# dt-rev-b.net
KiCad netlist of a schematic drawn in EAGLE
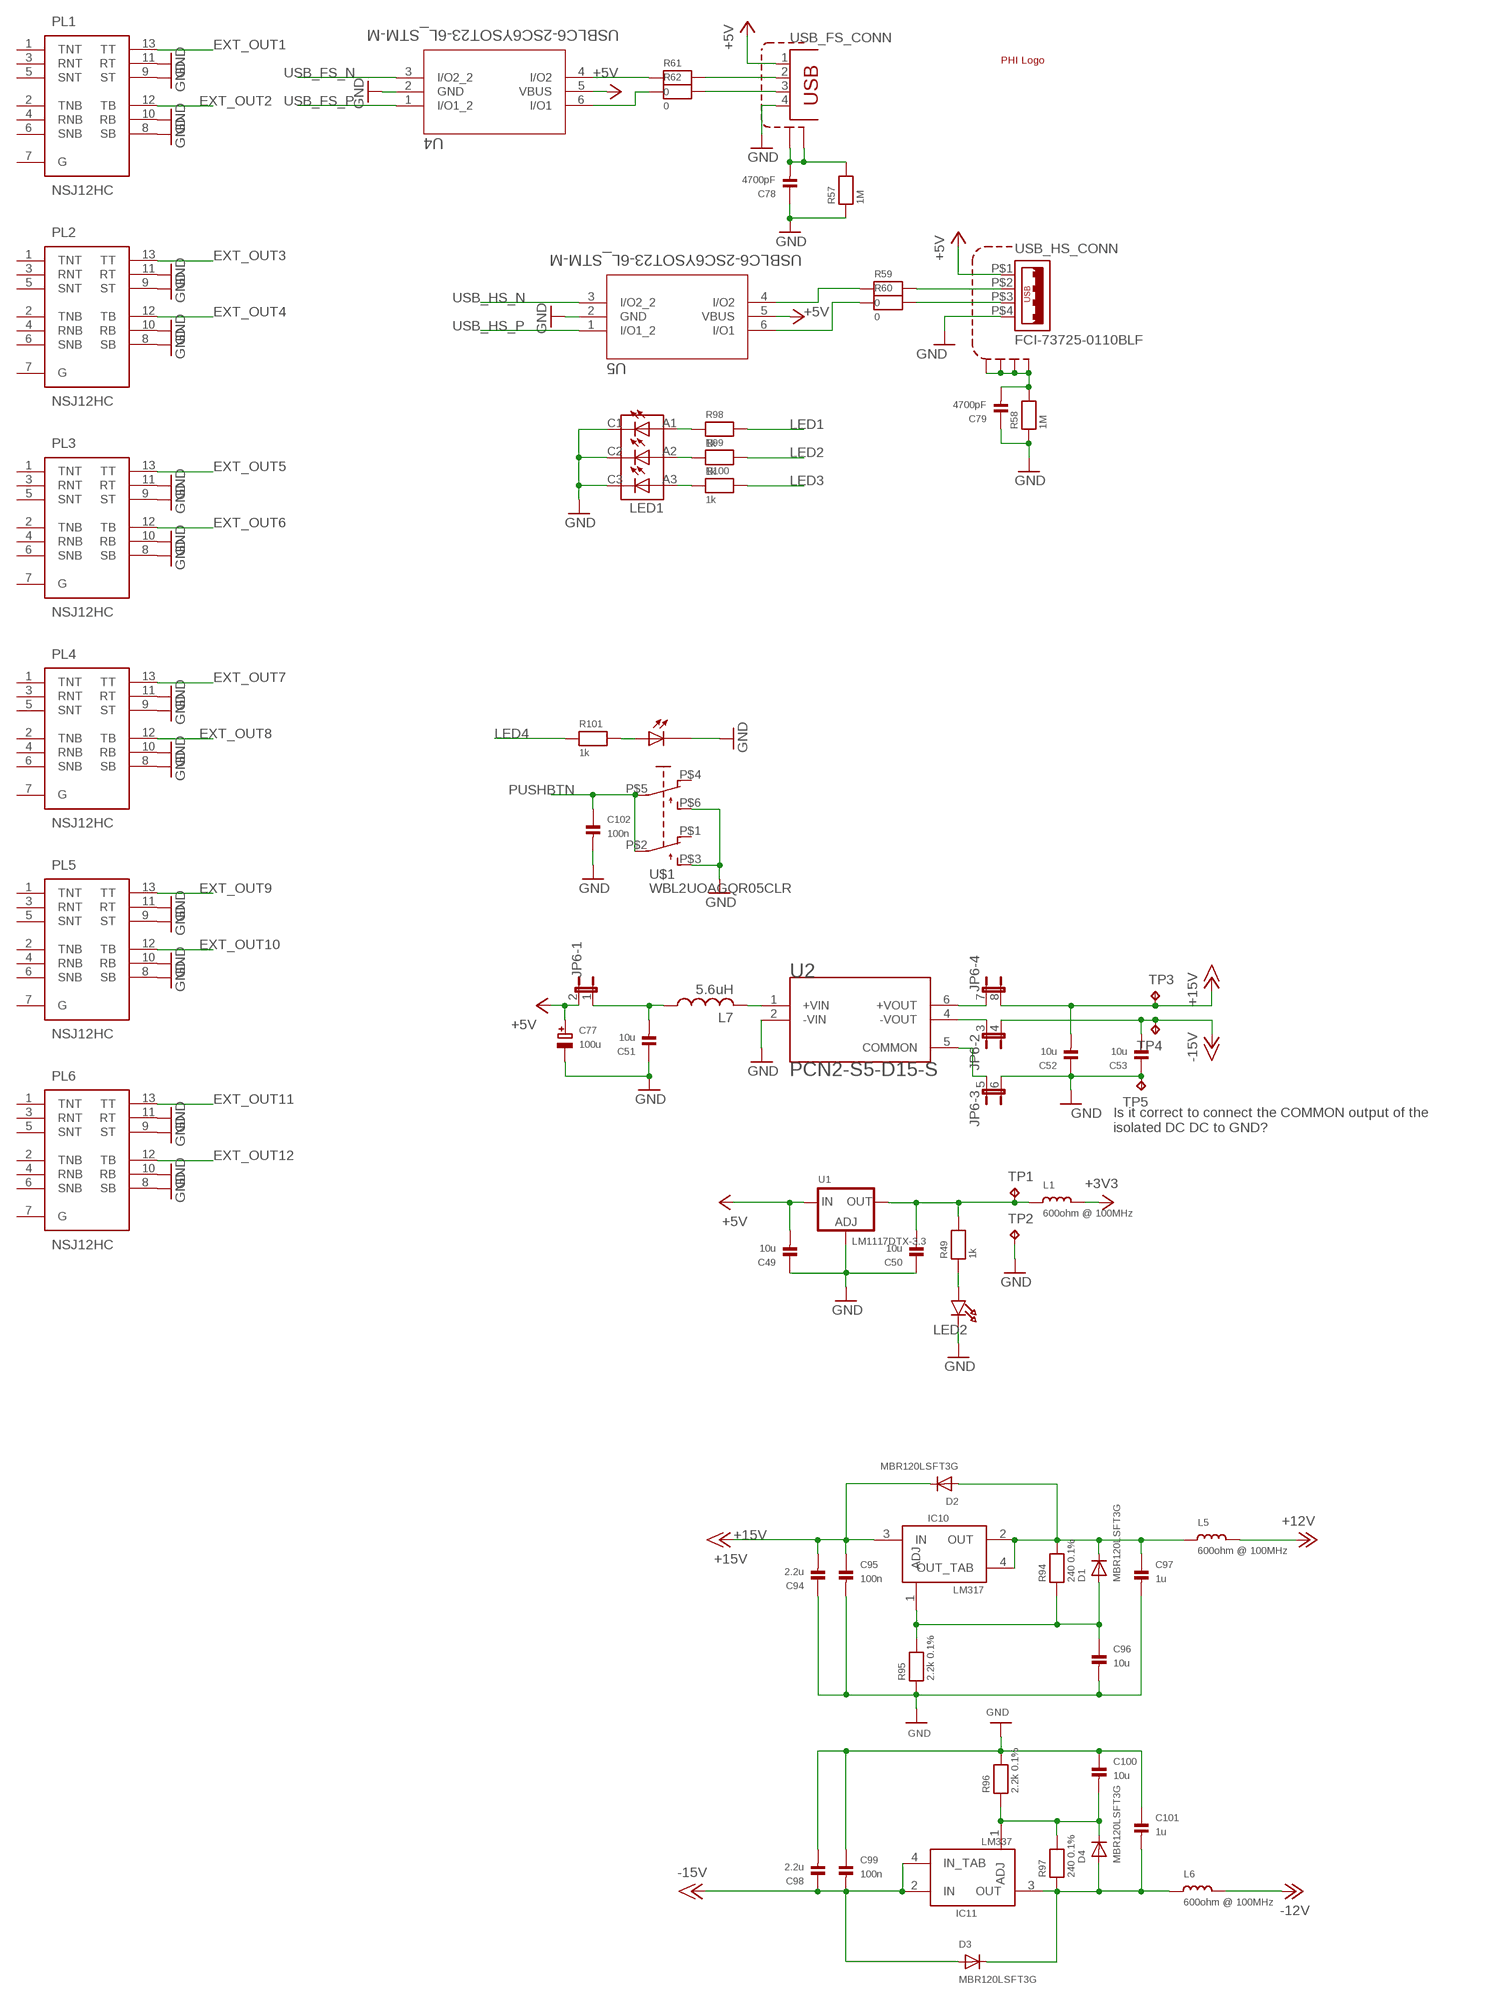
[diagram p0: schematic, sheet 1]
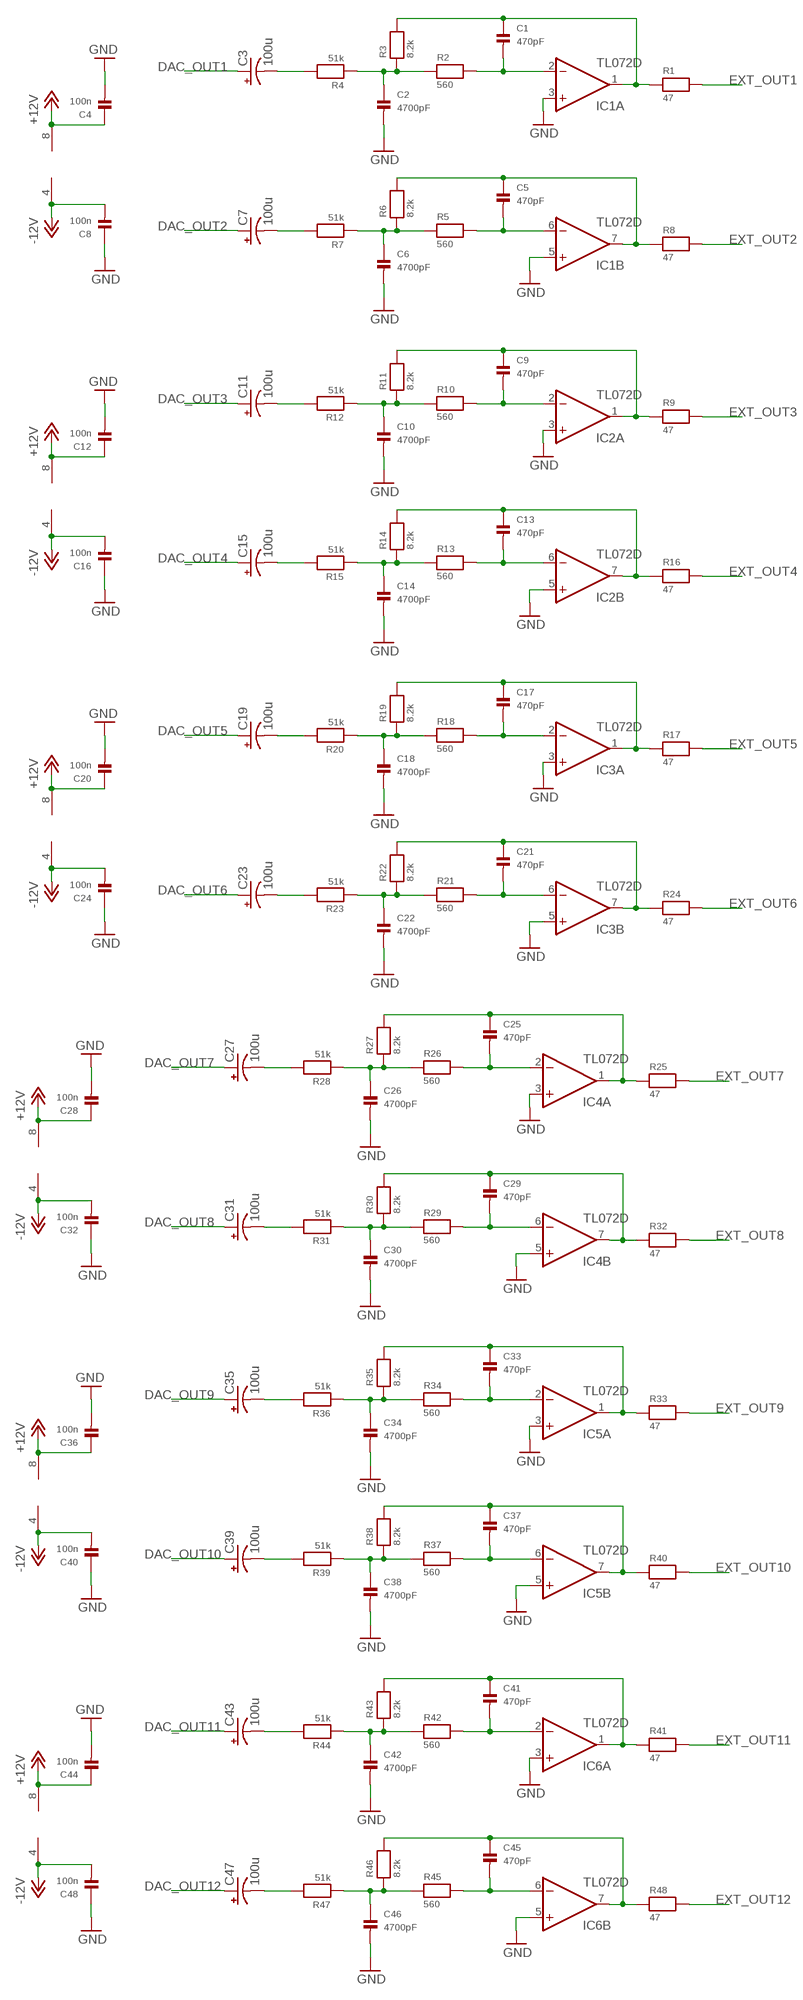
[diagram p1: schematic, sheet 2]
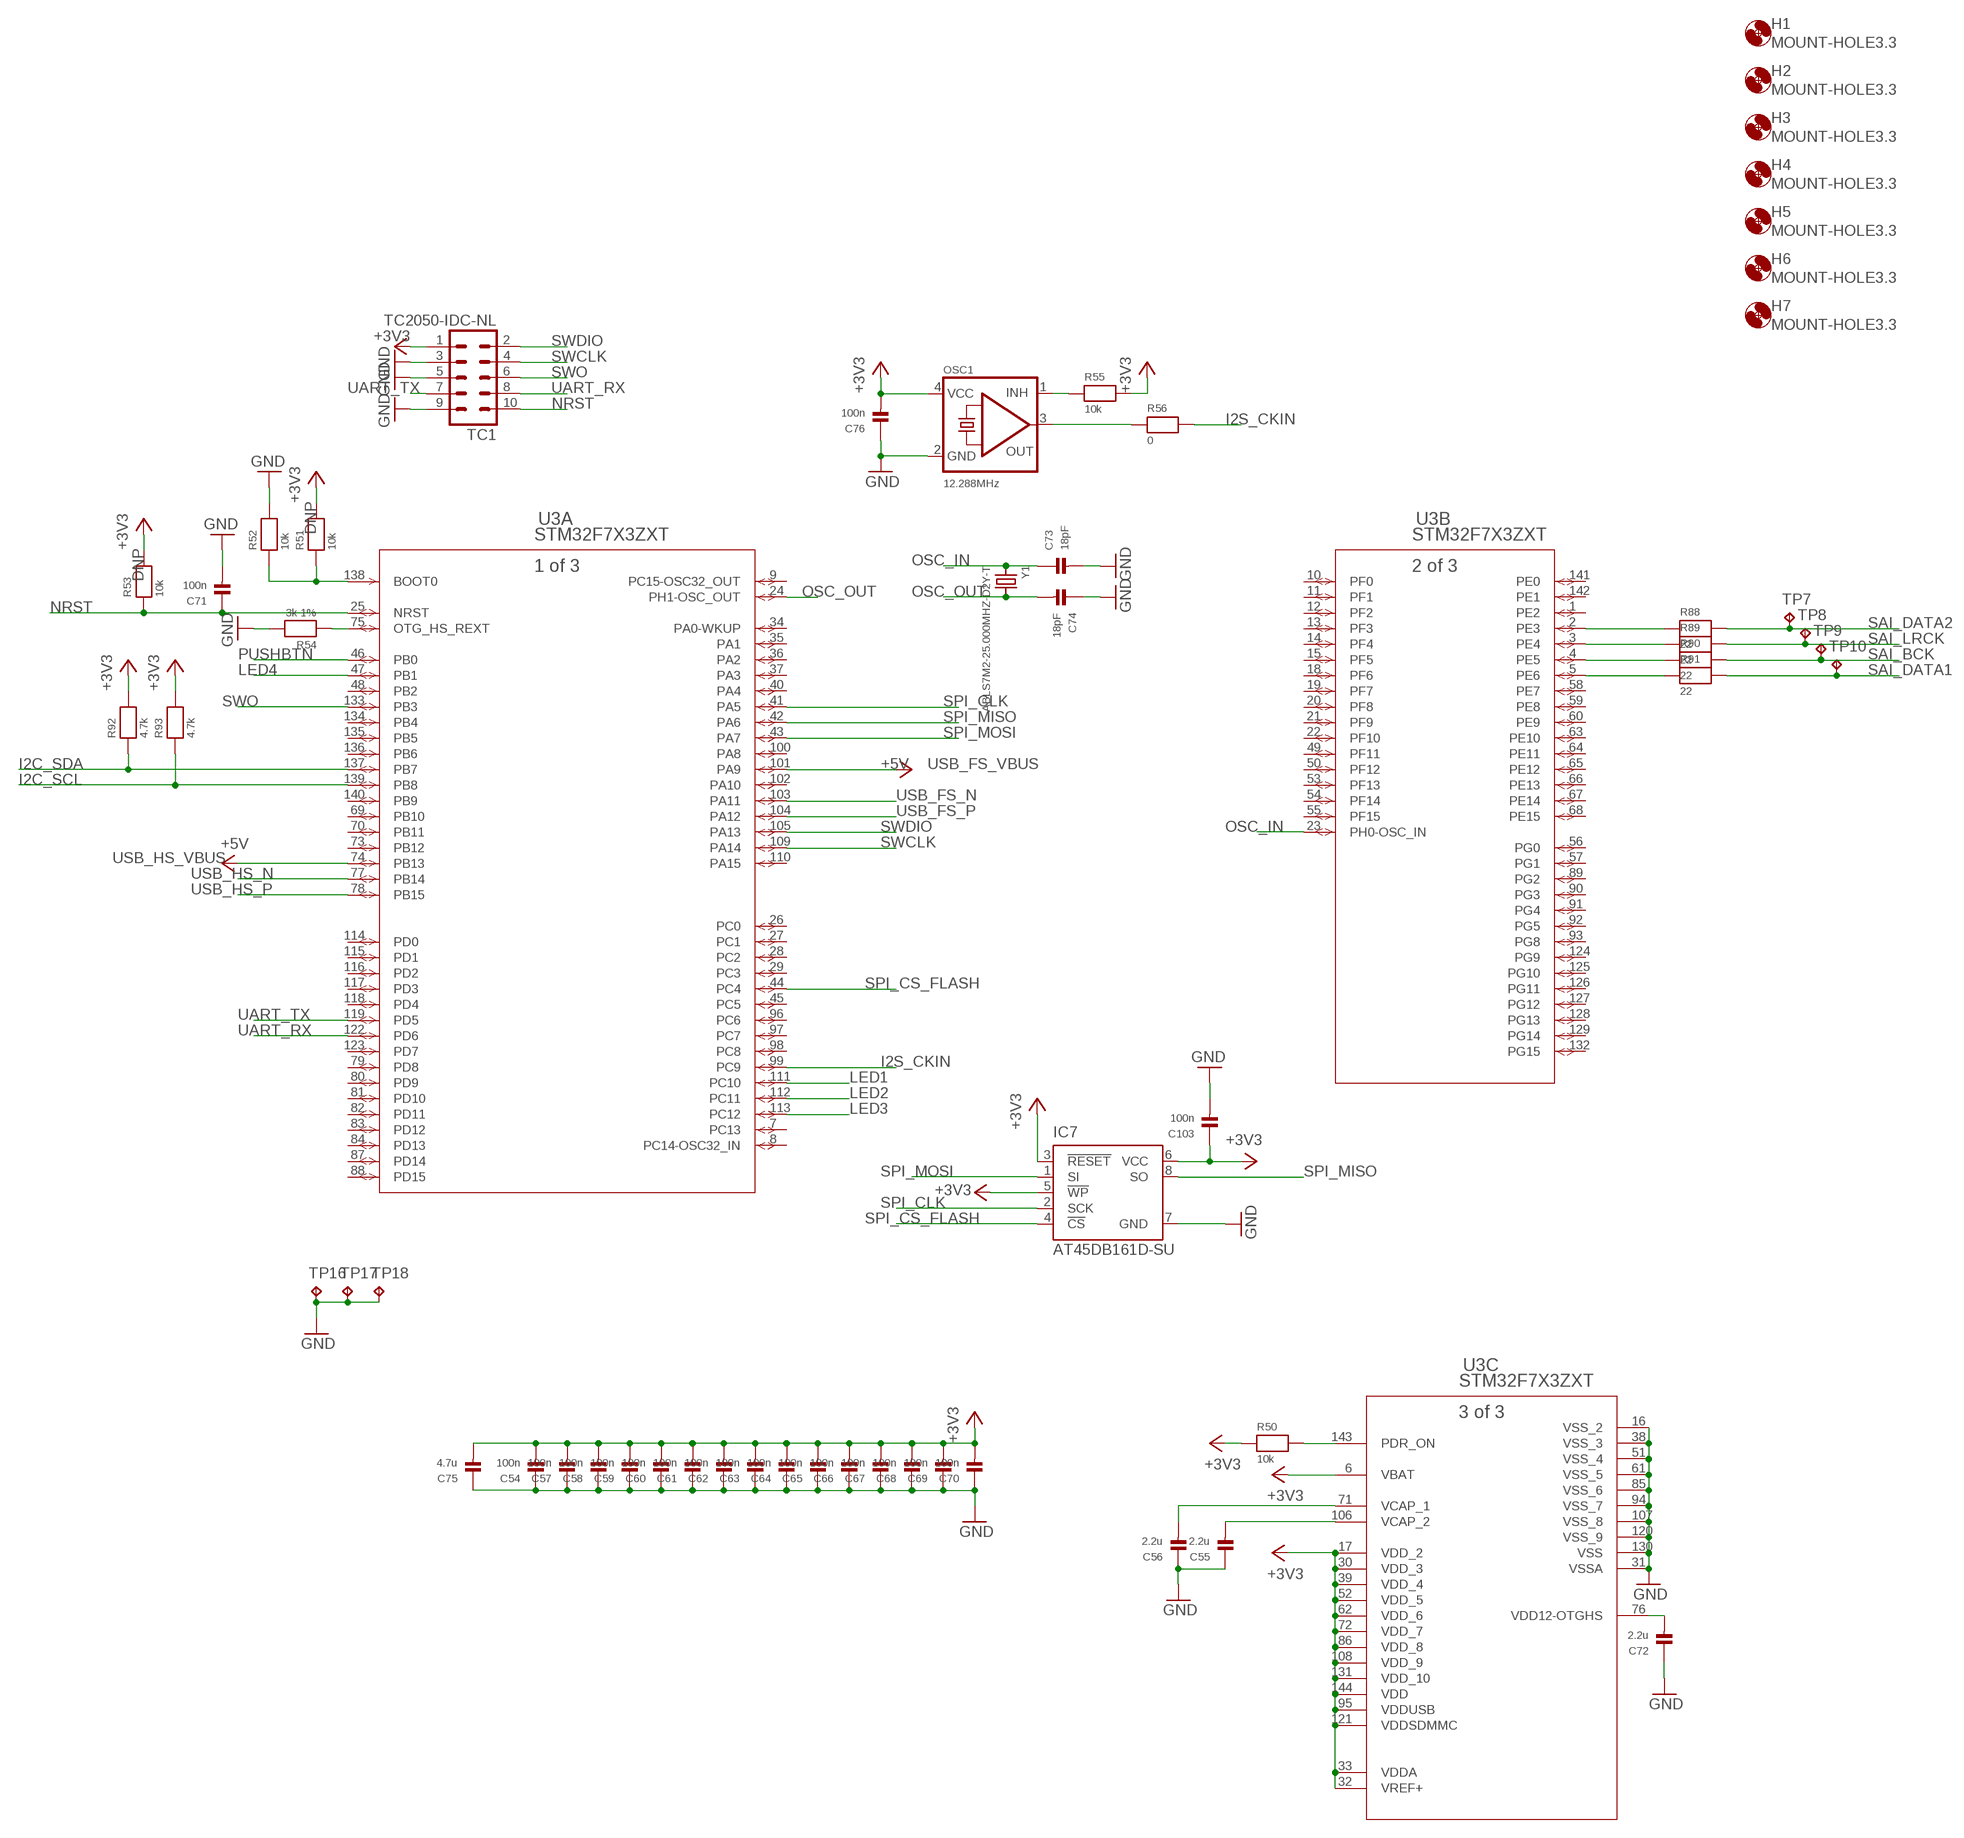
[diagram p2: schematic, sheet 3]
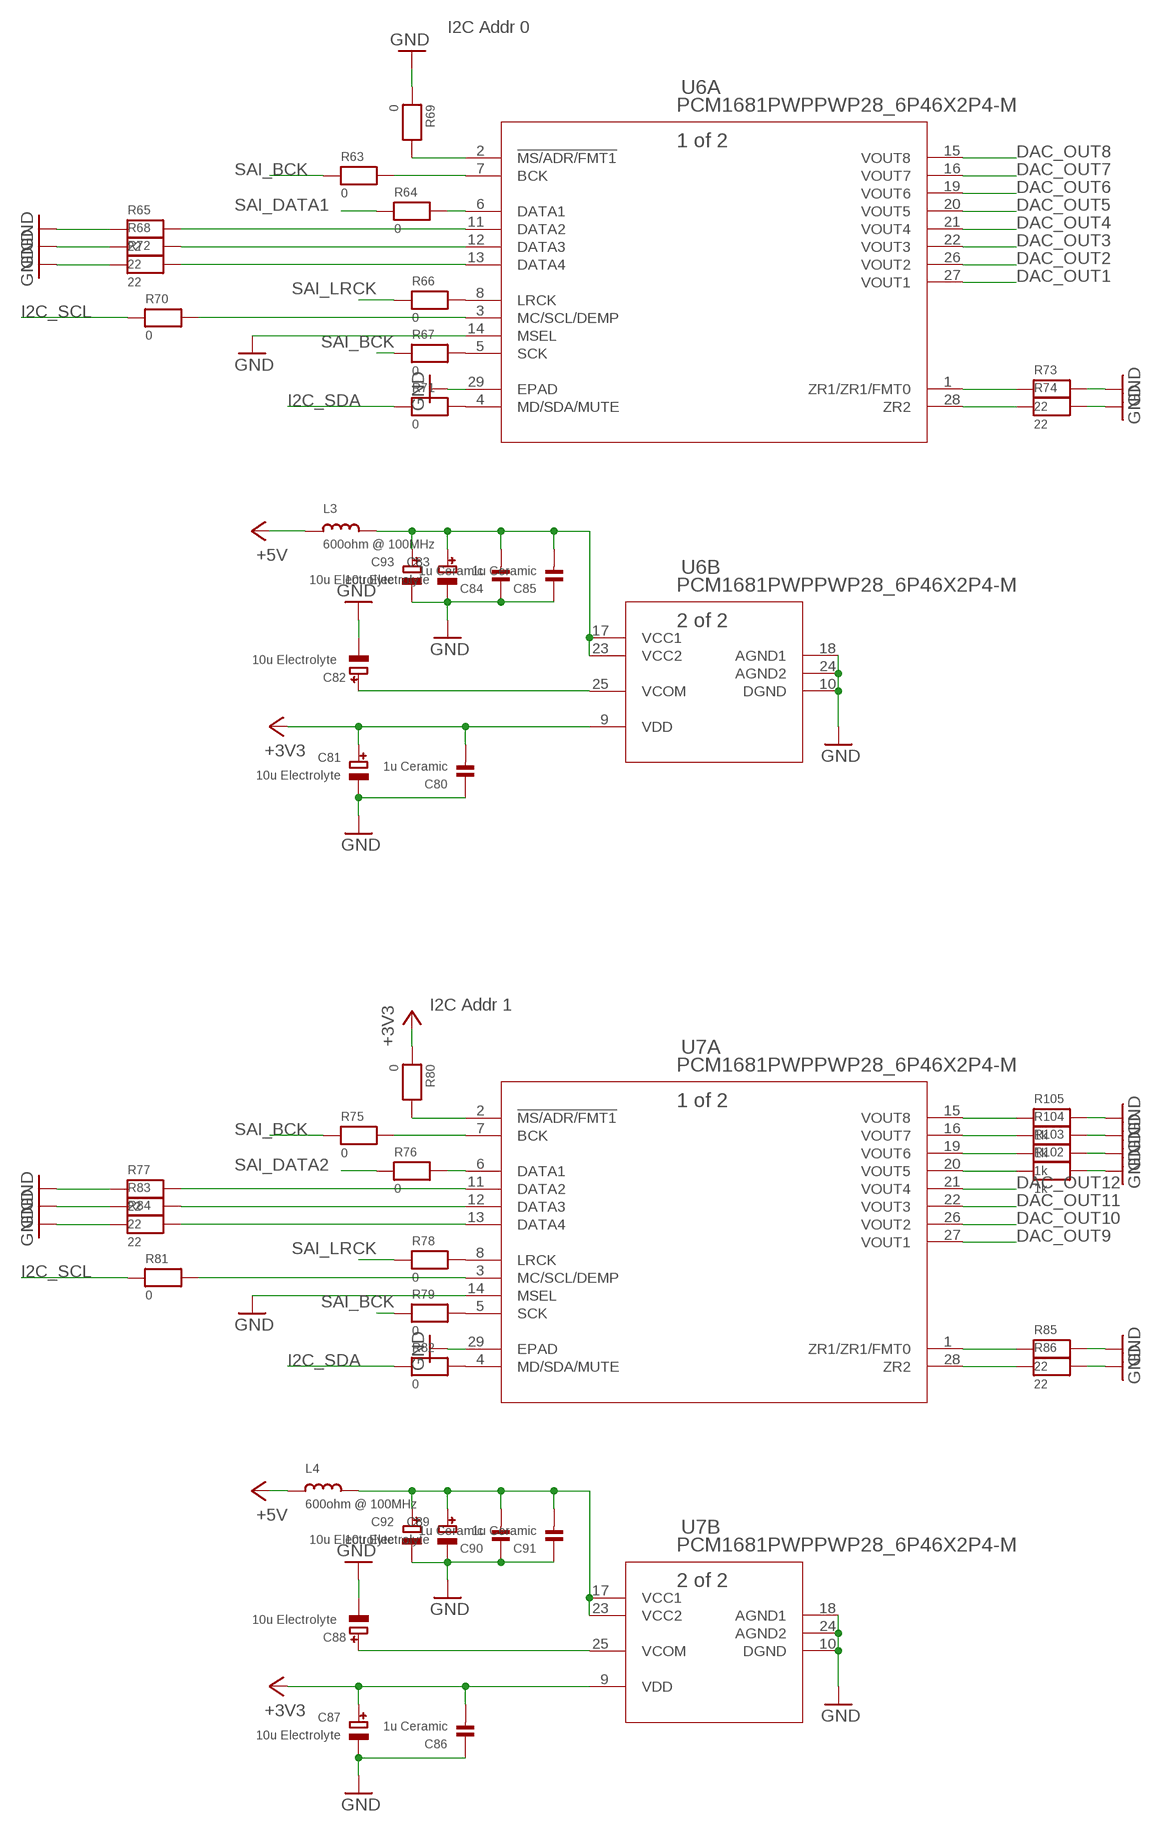
[diagram p3: schematic, sheet 4]

(export (version "E")
  (design (tool "Eeschema 10.0.6"))
  (components
    (comp (ref "C1")
      (value "470pF")
      (footprint "eagle-import:0603")
      (fields (field (name "PARTNO") "C0603C471J5GACTU"))
      (libsource (lib "eagle-import") (part "CAP_CERAMIC0603"))
    )
    (comp (ref "C2")
      (value "4700pF")
      (footprint "eagle-import:0603")
      (fields (field (name "PARTNO") "GRM1885C1H472JA01D"))
      (libsource (lib "eagle-import") (part "CAP_CERAMIC0603"))
    )
    (comp (ref "C3")
      (value "100u")
      (footprint "eagle-import:E2-5")
      (fields (field (name "PARTNO") "ESK107M025AC3AA"))
      (libsource (lib "eagle-import") (part "CPOL-USE2-5"))
    )
    (comp (ref "C4")
      (value "100n")
      (footprint "eagle-import:0603")
      (fields (field (name "PARTNO") "CC0603KRX7R9BB104"))
      (libsource (lib "eagle-import") (part "CAP_CERAMIC0603"))
    )
    (comp (ref "C5")
      (value "470pF")
      (footprint "eagle-import:0603")
      (fields (field (name "PARTNO") "C0603C471J5GACTU"))
      (libsource (lib "eagle-import") (part "CAP_CERAMIC0603"))
    )
    (comp (ref "C6")
      (value "4700pF")
      (footprint "eagle-import:0603")
      (fields (field (name "PARTNO") "GRM1885C1H472JA01D"))
      (libsource (lib "eagle-import") (part "CAP_CERAMIC0603"))
    )
    (comp (ref "C7")
      (value "100u")
      (footprint "eagle-import:E2-5")
      (fields (field (name "PARTNO") "ESK107M025AC3AA"))
      (libsource (lib "eagle-import") (part "CPOL-USE2-5"))
    )
    (comp (ref "C8")
      (value "100n")
      (footprint "eagle-import:0603")
      (fields (field (name "PARTNO") "CC0603KRX7R9BB104"))
      (libsource (lib "eagle-import") (part "CAP_CERAMIC0603"))
    )
    (comp (ref "C9")
      (value "470pF")
      (footprint "eagle-import:0603")
      (fields (field (name "PARTNO") "C0603C471J5GACTU"))
      (libsource (lib "eagle-import") (part "CAP_CERAMIC0603"))
    )
    (comp (ref "C10")
      (value "4700pF")
      (footprint "eagle-import:0603")
      (fields (field (name "PARTNO") "GRM1885C1H472JA01D"))
      (libsource (lib "eagle-import") (part "CAP_CERAMIC0603"))
    )
    (comp (ref "C11")
      (value "100u")
      (footprint "eagle-import:E2-5")
      (fields (field (name "PARTNO") "ESK107M025AC3AA"))
      (libsource (lib "eagle-import") (part "CPOL-USE2-5"))
    )
    (comp (ref "C12")
      (value "100n")
      (footprint "eagle-import:0603")
      (fields (field (name "PARTNO") "CC0603KRX7R9BB104"))
      (libsource (lib "eagle-import") (part "CAP_CERAMIC0603"))
    )
    (comp (ref "C13")
      (value "470pF")
      (footprint "eagle-import:0603")
      (fields (field (name "PARTNO") "C0603C471J5GACTU"))
      (libsource (lib "eagle-import") (part "CAP_CERAMIC0603"))
    )
    (comp (ref "C14")
      (value "4700pF")
      (footprint "eagle-import:0603")
      (fields (field (name "PARTNO") "GRM1885C1H472JA01D"))
      (libsource (lib "eagle-import") (part "CAP_CERAMIC0603"))
    )
    (comp (ref "C15")
      (value "100u")
      (footprint "eagle-import:E2-5")
      (fields (field (name "PARTNO") "ESK107M025AC3AA"))
      (libsource (lib "eagle-import") (part "CPOL-USE2-5"))
    )
    (comp (ref "C16")
      (value "100n")
      (footprint "eagle-import:0603")
      (fields (field (name "PARTNO") "CC0603KRX7R9BB104"))
      (libsource (lib "eagle-import") (part "CAP_CERAMIC0603"))
    )
    (comp (ref "C17")
      (value "470pF")
      (footprint "eagle-import:0603")
      (fields (field (name "PARTNO") "C0603C471J5GACTU"))
      (libsource (lib "eagle-import") (part "CAP_CERAMIC0603"))
    )
    (comp (ref "C18")
      (value "4700pF")
      (footprint "eagle-import:0603")
      (fields (field (name "PARTNO") "GRM1885C1H472JA01D"))
      (libsource (lib "eagle-import") (part "CAP_CERAMIC0603"))
    )
    (comp (ref "C19")
      (value "100u")
      (footprint "eagle-import:E2-5")
      (fields (field (name "PARTNO") "ESK107M025AC3AA"))
      (libsource (lib "eagle-import") (part "CPOL-USE2-5"))
    )
    (comp (ref "C20")
      (value "100n")
      (footprint "eagle-import:0603")
      (fields (field (name "PARTNO") "CC0603KRX7R9BB104"))
      (libsource (lib "eagle-import") (part "CAP_CERAMIC0603"))
    )
    (comp (ref "C21")
      (value "470pF")
      (footprint "eagle-import:0603")
      (fields (field (name "PARTNO") "C0603C471J5GACTU"))
      (libsource (lib "eagle-import") (part "CAP_CERAMIC0603"))
    )
    (comp (ref "C22")
      (value "4700pF")
      (footprint "eagle-import:0603")
      (fields (field (name "PARTNO") "GRM1885C1H472JA01D"))
      (libsource (lib "eagle-import") (part "CAP_CERAMIC0603"))
    )
    (comp (ref "C23")
      (value "100u")
      (footprint "eagle-import:E2-5")
      (fields (field (name "PARTNO") "ESK107M025AC3AA"))
      (libsource (lib "eagle-import") (part "CPOL-USE2-5"))
    )
    (comp (ref "C24")
      (value "100n")
      (footprint "eagle-import:0603")
      (fields (field (name "PARTNO") "CC0603KRX7R9BB104"))
      (libsource (lib "eagle-import") (part "CAP_CERAMIC0603"))
    )
    (comp (ref "C25")
      (value "470pF")
      (footprint "eagle-import:0603")
      (fields (field (name "PARTNO") "C0603C471J5GACTU"))
      (libsource (lib "eagle-import") (part "CAP_CERAMIC0603"))
    )
    (comp (ref "C26")
      (value "4700pF")
      (footprint "eagle-import:0603")
      (fields (field (name "PARTNO") "GRM1885C1H472JA01D"))
      (libsource (lib "eagle-import") (part "CAP_CERAMIC0603"))
    )
    (comp (ref "C27")
      (value "100u")
      (footprint "eagle-import:E2-5")
      (fields (field (name "PARTNO") "ESK107M025AC3AA"))
      (libsource (lib "eagle-import") (part "CPOL-USE2-5"))
    )
    (comp (ref "C28")
      (value "100n")
      (footprint "eagle-import:0603")
      (fields (field (name "PARTNO") "CC0603KRX7R9BB104"))
      (libsource (lib "eagle-import") (part "CAP_CERAMIC0603"))
    )
    (comp (ref "C29")
      (value "470pF")
      (footprint "eagle-import:0603")
      (fields (field (name "PARTNO") "C0603C471J5GACTU"))
      (libsource (lib "eagle-import") (part "CAP_CERAMIC0603"))
    )
    (comp (ref "C30")
      (value "4700pF")
      (footprint "eagle-import:0603")
      (fields (field (name "PARTNO") "GRM1885C1H472JA01D"))
      (libsource (lib "eagle-import") (part "CAP_CERAMIC0603"))
    )
    (comp (ref "C31")
      (value "100u")
      (footprint "eagle-import:E2-5")
      (fields (field (name "PARTNO") "ESK107M025AC3AA"))
      (libsource (lib "eagle-import") (part "CPOL-USE2-5"))
    )
    (comp (ref "C32")
      (value "100n")
      (footprint "eagle-import:0603")
      (fields (field (name "PARTNO") "CC0603KRX7R9BB104"))
      (libsource (lib "eagle-import") (part "CAP_CERAMIC0603"))
    )
    (comp (ref "C33")
      (value "470pF")
      (footprint "eagle-import:0603")
      (fields (field (name "PARTNO") "C0603C471J5GACTU"))
      (libsource (lib "eagle-import") (part "CAP_CERAMIC0603"))
    )
    (comp (ref "C34")
      (value "4700pF")
      (footprint "eagle-import:0603")
      (fields (field (name "PARTNO") "GRM1885C1H472JA01D"))
      (libsource (lib "eagle-import") (part "CAP_CERAMIC0603"))
    )
    (comp (ref "C35")
      (value "100u")
      (footprint "eagle-import:E2-5")
      (fields (field (name "PARTNO") "ESK107M025AC3AA"))
      (libsource (lib "eagle-import") (part "CPOL-USE2-5"))
    )
    (comp (ref "C36")
      (value "100n")
      (footprint "eagle-import:0603")
      (fields (field (name "PARTNO") "CC0603KRX7R9BB104"))
      (libsource (lib "eagle-import") (part "CAP_CERAMIC0603"))
    )
    (comp (ref "C37")
      (value "470pF")
      (footprint "eagle-import:0603")
      (fields (field (name "PARTNO") "C0603C471J5GACTU"))
      (libsource (lib "eagle-import") (part "CAP_CERAMIC0603"))
    )
    (comp (ref "C38")
      (value "4700pF")
      (footprint "eagle-import:0603")
      (fields (field (name "PARTNO") "GRM1885C1H472JA01D"))
      (libsource (lib "eagle-import") (part "CAP_CERAMIC0603"))
    )
    (comp (ref "C39")
      (value "100u")
      (footprint "eagle-import:E2-5")
      (fields (field (name "PARTNO") "ESK107M025AC3AA"))
      (libsource (lib "eagle-import") (part "CPOL-USE2-5"))
    )
    (comp (ref "C40")
      (value "100n")
      (footprint "eagle-import:0603")
      (fields (field (name "PARTNO") "CC0603KRX7R9BB104"))
      (libsource (lib "eagle-import") (part "CAP_CERAMIC0603"))
    )
    (comp (ref "C41")
      (value "470pF")
      (footprint "eagle-import:0603")
      (fields (field (name "PARTNO") "C0603C471J5GACTU"))
      (libsource (lib "eagle-import") (part "CAP_CERAMIC0603"))
    )
    (comp (ref "C42")
      (value "4700pF")
      (footprint "eagle-import:0603")
      (fields (field (name "PARTNO") "GRM1885C1H472JA01D"))
      (libsource (lib "eagle-import") (part "CAP_CERAMIC0603"))
    )
    (comp (ref "C43")
      (value "100u")
      (footprint "eagle-import:E2-5")
      (fields (field (name "PARTNO") "ESK107M025AC3AA"))
      (libsource (lib "eagle-import") (part "CPOL-USE2-5"))
    )
    (comp (ref "C44")
      (value "100n")
      (footprint "eagle-import:0603")
      (fields (field (name "PARTNO") "CC0603KRX7R9BB104"))
      (libsource (lib "eagle-import") (part "CAP_CERAMIC0603"))
    )
    (comp (ref "C45")
      (value "470pF")
      (footprint "eagle-import:0603")
      (fields (field (name "PARTNO") "C0603C471J5GACTU"))
      (libsource (lib "eagle-import") (part "CAP_CERAMIC0603"))
    )
    (comp (ref "C46")
      (value "4700pF")
      (footprint "eagle-import:0603")
      (fields (field (name "PARTNO") "GRM1885C1H472JA01D"))
      (libsource (lib "eagle-import") (part "CAP_CERAMIC0603"))
    )
    (comp (ref "C47")
      (value "100u")
      (footprint "eagle-import:E2-5")
      (fields (field (name "PARTNO") "ESK107M025AC3AA"))
      (libsource (lib "eagle-import") (part "CPOL-USE2-5"))
    )
    (comp (ref "C48")
      (value "100n")
      (footprint "eagle-import:0603")
      (fields (field (name "PARTNO") "CC0603KRX7R9BB104"))
      (libsource (lib "eagle-import") (part "CAP_CERAMIC0603"))
    )
    (comp (ref "IC1")
      (value "TL072D")
      (footprint "eagle-import:SO08")
      (fields (field (name "PARTNO") "TL072SG-13"))
      (libsource (lib "eagle-import") (part "TL072D"))
    )
    (comp (ref "IC2")
      (value "TL072D")
      (footprint "eagle-import:SO08")
      (fields (field (name "PARTNO") "TL072SG-13"))
      (libsource (lib "eagle-import") (part "TL072D"))
    )
    (comp (ref "IC3")
      (value "TL072D")
      (footprint "eagle-import:SO08")
      (fields (field (name "PARTNO") "TL072SG-13"))
      (libsource (lib "eagle-import") (part "TL072D"))
    )
    (comp (ref "IC4")
      (value "TL072D")
      (footprint "eagle-import:SO08")
      (fields (field (name "PARTNO") "TL072SG-13"))
      (libsource (lib "eagle-import") (part "TL072D"))
    )
    (comp (ref "IC5")
      (value "TL072D")
      (footprint "eagle-import:SO08")
      (fields (field (name "PARTNO") "TL072SG-13"))
      (libsource (lib "eagle-import") (part "TL072D"))
    )
    (comp (ref "IC6")
      (value "TL072D")
      (footprint "eagle-import:SO08")
      (fields (field (name "PARTNO") "TL072SG-13"))
      (libsource (lib "eagle-import") (part "TL072D"))
    )
    (comp (ref "R1")
      (value "47")
      (footprint "eagle-import:0603")
      (fields (field (name "PARTNO") "CRCW060347R0FKEAC"))
      (libsource (lib "eagle-import") (part "RESISTOR0603"))
    )
    (comp (ref "R2")
      (value "560")
      (footprint "eagle-import:0603")
      (fields (field (name "PARTNO") "RC0603FR-07560RL"))
      (libsource (lib "eagle-import") (part "RESISTOR0603"))
    )
    (comp (ref "R3")
      (value "8.2k")
      (footprint "eagle-import:0603")
      (fields (field (name "PARTNO") "ERJ-3EKF8201V"))
      (libsource (lib "eagle-import") (part "RESISTOR0603"))
    )
    (comp (ref "R4")
      (value "51k")
      (footprint "eagle-import:0603")
      (fields (field (name "PARTNO") "RC0603FR-0751KL"))
      (libsource (lib "eagle-import") (part "RESISTOR0603"))
    )
    (comp (ref "R5")
      (value "560")
      (footprint "eagle-import:0603")
      (fields (field (name "PARTNO") "RC0603FR-07560RL"))
      (libsource (lib "eagle-import") (part "RESISTOR0603"))
    )
    (comp (ref "R6")
      (value "8.2k")
      (footprint "eagle-import:0603")
      (fields (field (name "PARTNO") "ERJ-3EKF8201V"))
      (libsource (lib "eagle-import") (part "RESISTOR0603"))
    )
    (comp (ref "R7")
      (value "51k")
      (footprint "eagle-import:0603")
      (fields (field (name "PARTNO") "RC0603FR-0751KL"))
      (libsource (lib "eagle-import") (part "RESISTOR0603"))
    )
    (comp (ref "R8")
      (value "47")
      (footprint "eagle-import:0603")
      (fields (field (name "PARTNO") "CRCW060347R0FKEAC"))
      (libsource (lib "eagle-import") (part "RESISTOR0603"))
    )
    (comp (ref "R9")
      (value "47")
      (footprint "eagle-import:0603")
      (fields (field (name "PARTNO") "CRCW060347R0FKEAC"))
      (libsource (lib "eagle-import") (part "RESISTOR0603"))
    )
    (comp (ref "R10")
      (value "560")
      (footprint "eagle-import:0603")
      (fields (field (name "PARTNO") "RC0603FR-07560RL"))
      (libsource (lib "eagle-import") (part "RESISTOR0603"))
    )
    (comp (ref "R11")
      (value "8.2k")
      (footprint "eagle-import:0603")
      (fields (field (name "PARTNO") "ERJ-3EKF8201V"))
      (libsource (lib "eagle-import") (part "RESISTOR0603"))
    )
    (comp (ref "R12")
      (value "51k")
      (footprint "eagle-import:0603")
      (fields (field (name "PARTNO") "RC0603FR-0751KL"))
      (libsource (lib "eagle-import") (part "RESISTOR0603"))
    )
    (comp (ref "R13")
      (value "560")
      (footprint "eagle-import:0603")
      (fields (field (name "PARTNO") "RC0603FR-07560RL"))
      (libsource (lib "eagle-import") (part "RESISTOR0603"))
    )
    (comp (ref "R14")
      (value "8.2k")
      (footprint "eagle-import:0603")
      (fields (field (name "PARTNO") "ERJ-3EKF8201V"))
      (libsource (lib "eagle-import") (part "RESISTOR0603"))
    )
    (comp (ref "R15")
      (value "51k")
      (footprint "eagle-import:0603")
      (fields (field (name "PARTNO") "RC0603FR-0751KL"))
      (libsource (lib "eagle-import") (part "RESISTOR0603"))
    )
    (comp (ref "R16")
      (value "47")
      (footprint "eagle-import:0603")
      (fields (field (name "PARTNO") "CRCW060347R0FKEAC"))
      (libsource (lib "eagle-import") (part "RESISTOR0603"))
    )
    (comp (ref "R17")
      (value "47")
      (footprint "eagle-import:0603")
      (fields (field (name "PARTNO") "CRCW060347R0FKEAC"))
      (libsource (lib "eagle-import") (part "RESISTOR0603"))
    )
    (comp (ref "R18")
      (value "560")
      (footprint "eagle-import:0603")
      (fields (field (name "PARTNO") "RC0603FR-07560RL"))
      (libsource (lib "eagle-import") (part "RESISTOR0603"))
    )
    (comp (ref "R19")
      (value "8.2k")
      (footprint "eagle-import:0603")
      (fields (field (name "PARTNO") "ERJ-3EKF8201V"))
      (libsource (lib "eagle-import") (part "RESISTOR0603"))
    )
    (comp (ref "R20")
      (value "51k")
      (footprint "eagle-import:0603")
      (fields (field (name "PARTNO") "RC0603FR-0751KL"))
      (libsource (lib "eagle-import") (part "RESISTOR0603"))
    )
    (comp (ref "R21")
      (value "560")
      (footprint "eagle-import:0603")
      (fields (field (name "PARTNO") "RC0603FR-07560RL"))
      (libsource (lib "eagle-import") (part "RESISTOR0603"))
    )
    (comp (ref "R22")
      (value "8.2k")
      (footprint "eagle-import:0603")
      (fields (field (name "PARTNO") "ERJ-3EKF8201V"))
      (libsource (lib "eagle-import") (part "RESISTOR0603"))
    )
    (comp (ref "R23")
      (value "51k")
      (footprint "eagle-import:0603")
      (fields (field (name "PARTNO") "RC0603FR-0751KL"))
      (libsource (lib "eagle-import") (part "RESISTOR0603"))
    )
    (comp (ref "R24")
      (value "47")
      (footprint "eagle-import:0603")
      (fields (field (name "PARTNO") "CRCW060347R0FKEAC"))
      (libsource (lib "eagle-import") (part "RESISTOR0603"))
    )
    (comp (ref "R25")
      (value "47")
      (footprint "eagle-import:0603")
      (fields (field (name "PARTNO") "CRCW060347R0FKEAC"))
      (libsource (lib "eagle-import") (part "RESISTOR0603"))
    )
    (comp (ref "R26")
      (value "560")
      (footprint "eagle-import:0603")
      (fields (field (name "PARTNO") "RC0603FR-07560RL"))
      (libsource (lib "eagle-import") (part "RESISTOR0603"))
    )
    (comp (ref "R27")
      (value "8.2k")
      (footprint "eagle-import:0603")
      (fields (field (name "PARTNO") "ERJ-3EKF8201V"))
      (libsource (lib "eagle-import") (part "RESISTOR0603"))
    )
    (comp (ref "R28")
      (value "51k")
      (footprint "eagle-import:0603")
      (fields (field (name "PARTNO") "RC0603FR-0751KL"))
      (libsource (lib "eagle-import") (part "RESISTOR0603"))
    )
    (comp (ref "R29")
      (value "560")
      (footprint "eagle-import:0603")
      (fields (field (name "PARTNO") "RC0603FR-07560RL"))
      (libsource (lib "eagle-import") (part "RESISTOR0603"))
    )
    (comp (ref "R30")
      (value "8.2k")
      (footprint "eagle-import:0603")
      (fields (field (name "PARTNO") "ERJ-3EKF8201V"))
      (libsource (lib "eagle-import") (part "RESISTOR0603"))
    )
    (comp (ref "R31")
      (value "51k")
      (footprint "eagle-import:0603")
      (fields (field (name "PARTNO") "RC0603FR-0751KL"))
      (libsource (lib "eagle-import") (part "RESISTOR0603"))
    )
    (comp (ref "R32")
      (value "47")
      (footprint "eagle-import:0603")
      (fields (field (name "PARTNO") "CRCW060347R0FKEAC"))
      (libsource (lib "eagle-import") (part "RESISTOR0603"))
    )
    (comp (ref "R33")
      (value "47")
      (footprint "eagle-import:0603")
      (fields (field (name "PARTNO") "CRCW060347R0FKEAC"))
      (libsource (lib "eagle-import") (part "RESISTOR0603"))
    )
    (comp (ref "R34")
      (value "560")
      (footprint "eagle-import:0603")
      (fields (field (name "PARTNO") "RC0603FR-07560RL"))
      (libsource (lib "eagle-import") (part "RESISTOR0603"))
    )
    (comp (ref "R35")
      (value "8.2k")
      (footprint "eagle-import:0603")
      (fields (field (name "PARTNO") "ERJ-3EKF8201V"))
      (libsource (lib "eagle-import") (part "RESISTOR0603"))
    )
    (comp (ref "R36")
      (value "51k")
      (footprint "eagle-import:0603")
      (fields (field (name "PARTNO") "RC0603FR-0751KL"))
      (libsource (lib "eagle-import") (part "RESISTOR0603"))
    )
    (comp (ref "R37")
      (value "560")
      (footprint "eagle-import:0603")
      (fields (field (name "PARTNO") "RC0603FR-07560RL"))
      (libsource (lib "eagle-import") (part "RESISTOR0603"))
    )
    (comp (ref "R38")
      (value "8.2k")
      (footprint "eagle-import:0603")
      (fields (field (name "PARTNO") "ERJ-3EKF8201V"))
      (libsource (lib "eagle-import") (part "RESISTOR0603"))
    )
    (comp (ref "R39")
      (value "51k")
      (footprint "eagle-import:0603")
      (fields (field (name "PARTNO") "RC0603FR-0751KL"))
      (libsource (lib "eagle-import") (part "RESISTOR0603"))
    )
    (comp (ref "R40")
      (value "47")
      (footprint "eagle-import:0603")
      (fields (field (name "PARTNO") "CRCW060347R0FKEAC"))
      (libsource (lib "eagle-import") (part "RESISTOR0603"))
    )
    (comp (ref "R41")
      (value "47")
      (footprint "eagle-import:0603")
      (fields (field (name "PARTNO") "CRCW060347R0FKEAC"))
      (libsource (lib "eagle-import") (part "RESISTOR0603"))
    )
    (comp (ref "R42")
      (value "560")
      (footprint "eagle-import:0603")
      (fields (field (name "PARTNO") "RC0603FR-07560RL"))
      (libsource (lib "eagle-import") (part "RESISTOR0603"))
    )
    (comp (ref "R43")
      (value "8.2k")
      (footprint "eagle-import:0603")
      (fields (field (name "PARTNO") "ERJ-3EKF8201V"))
      (libsource (lib "eagle-import") (part "RESISTOR0603"))
    )
    (comp (ref "R44")
      (value "51k")
      (footprint "eagle-import:0603")
      (fields (field (name "PARTNO") "RC0603FR-0751KL"))
      (libsource (lib "eagle-import") (part "RESISTOR0603"))
    )
    (comp (ref "R45")
      (value "560")
      (footprint "eagle-import:0603")
      (fields (field (name "PARTNO") "RC0603FR-07560RL"))
      (libsource (lib "eagle-import") (part "RESISTOR0603"))
    )
    (comp (ref "R46")
      (value "8.2k")
      (footprint "eagle-import:0603")
      (fields (field (name "PARTNO") "ERJ-3EKF8201V"))
      (libsource (lib "eagle-import") (part "RESISTOR0603"))
    )
    (comp (ref "R47")
      (value "51k")
      (footprint "eagle-import:0603")
      (fields (field (name "PARTNO") "RC0603FR-0751KL"))
      (libsource (lib "eagle-import") (part "RESISTOR0603"))
    )
    (comp (ref "R48")
      (value "47")
      (footprint "eagle-import:0603")
      (fields (field (name "PARTNO") "CRCW060347R0FKEAC"))
      (libsource (lib "eagle-import") (part "RESISTOR0603"))
    )
    (comp (ref "C80")
      (value "1u Ceramic")
      (footprint "eagle-import:0603")
      (fields (field (name "PARTNO") "GMK107AB7105KAHT"))
      (libsource (lib "eagle-import") (part "CAP_CERAMIC0603"))
    )
    (comp (ref "C81")
      (value "10u Electrolyte")
      (footprint "eagle-import:PANASONIC_C")
      (fields (field (name "PARTNO") "EEE-HA1V100R"))
      (libsource (lib "eagle-import") (part "CAP_ELECTROLYTICPANASONIC_C"))
    )
    (comp (ref "C82")
      (value "10u Electrolyte")
      (footprint "eagle-import:PANASONIC_C")
      (fields (field (name "PARTNO") "EEE-HA1V100R"))
      (libsource (lib "eagle-import") (part "CAP_ELECTROLYTICPANASONIC_C"))
    )
    (comp (ref "C83")
      (value "10u Electrolyte")
      (footprint "eagle-import:PANASONIC_C")
      (fields (field (name "PARTNO") "EEE-HA1V100R"))
      (libsource (lib "eagle-import") (part "CAP_ELECTROLYTICPANASONIC_C"))
    )
    (comp (ref "C84")
      (value "1u Ceramic")
      (footprint "eagle-import:0603")
      (fields (field (name "PARTNO") "GMK107AB7105KAHT"))
      (libsource (lib "eagle-import") (part "CAP_CERAMIC0603"))
    )
    (comp (ref "C85")
      (value "1u Ceramic")
      (footprint "eagle-import:0603")
      (fields (field (name "PARTNO") "GMK107AB7105KAHT"))
      (libsource (lib "eagle-import") (part "CAP_CERAMIC0603"))
    )
    (comp (ref "C86")
      (value "1u Ceramic")
      (footprint "eagle-import:0603")
      (fields (field (name "PARTNO") "GMK107AB7105KAHT"))
      (libsource (lib "eagle-import") (part "CAP_CERAMIC0603"))
    )
    (comp (ref "C87")
      (value "10u Electrolyte")
      (footprint "eagle-import:PANASONIC_C")
      (fields (field (name "PARTNO") "EEE-HA1V100R"))
      (libsource (lib "eagle-import") (part "CAP_ELECTROLYTICPANASONIC_C"))
    )
    (comp (ref "C88")
      (value "10u Electrolyte")
      (footprint "eagle-import:PANASONIC_C")
      (fields (field (name "PARTNO") "EEE-HA1V100R"))
      (libsource (lib "eagle-import") (part "CAP_ELECTROLYTICPANASONIC_C"))
    )
    (comp (ref "C89")
      (value "10u Electrolyte")
      (footprint "eagle-import:PANASONIC_C")
      (fields (field (name "PARTNO") "EEE-HA1V100R"))
      (libsource (lib "eagle-import") (part "CAP_ELECTROLYTICPANASONIC_C"))
    )
    (comp (ref "C90")
      (value "1u Ceramic")
      (footprint "eagle-import:0603")
      (fields (field (name "PARTNO") "GMK107AB7105KAHT"))
      (libsource (lib "eagle-import") (part "CAP_CERAMIC0603"))
    )
    (comp (ref "C91")
      (value "1u Ceramic")
      (footprint "eagle-import:0603")
      (fields (field (name "PARTNO") "GMK107AB7105KAHT"))
      (libsource (lib "eagle-import") (part "CAP_CERAMIC0603"))
    )
    (comp (ref "C92")
      (value "10u Electrolyte")
      (footprint "eagle-import:PANASONIC_C")
      (fields (field (name "PARTNO") "EEE-HA1V100R"))
      (libsource (lib "eagle-import") (part "CAP_ELECTROLYTICPANASONIC_C"))
    )
    (comp (ref "C93")
      (value "10u Electrolyte")
      (footprint "eagle-import:PANASONIC_C")
      (fields (field (name "PARTNO") "EEE-HA1V100R"))
      (libsource (lib "eagle-import") (part "CAP_ELECTROLYTICPANASONIC_C"))
    )
    (comp (ref "L3")
      (value "600ohm @ 100MHz")
      (footprint "eagle-import:0603")
      (fields (field (name "PARTNO") "BLM18KG601SN1D"))
      (libsource (lib "eagle-import") (part "INDUCTOR0603"))
    )
    (comp (ref "L4")
      (value "600ohm @ 100MHz")
      (footprint "eagle-import:0603")
      (fields (field (name "PARTNO") "BLM18KG601SN1D"))
      (libsource (lib "eagle-import") (part "INDUCTOR0603"))
    )
    (comp (ref "R63")
      (value "0")
      (footprint "eagle-import:0603")
      (fields (field (name "PARTNO") "CRCW06030000Z0EBC"))
      (libsource (lib "eagle-import") (part "RESISTOR0603"))
    )
    (comp (ref "R64")
      (value "0")
      (footprint "eagle-import:0603")
      (fields (field (name "PARTNO") "CRCW06030000Z0EBC"))
      (libsource (lib "eagle-import") (part "RESISTOR0603"))
    )
    (comp (ref "R65")
      (value "22")
      (footprint "eagle-import:0603")
      (fields (field (name "PARTNO") "CRCW060322R0FKEAC"))
      (libsource (lib "eagle-import") (part "RESISTOR0603"))
    )
    (comp (ref "R66")
      (value "0")
      (footprint "eagle-import:0603")
      (fields (field (name "PARTNO") "CRCW06030000Z0EBC"))
      (libsource (lib "eagle-import") (part "RESISTOR0603"))
    )
    (comp (ref "R67")
      (value "0")
      (footprint "eagle-import:0603")
      (fields (field (name "PARTNO") "CRCW06030000Z0EBC"))
      (libsource (lib "eagle-import") (part "RESISTOR0603"))
    )
    (comp (ref "R68")
      (value "22")
      (footprint "eagle-import:0603")
      (fields (field (name "PARTNO") "CRCW060322R0FKEAC"))
      (libsource (lib "eagle-import") (part "RESISTOR0603"))
    )
    (comp (ref "R69")
      (value "0")
      (footprint "eagle-import:0603")
      (fields (field (name "PARTNO") "CRCW06030000Z0EBC"))
      (libsource (lib "eagle-import") (part "RESISTOR0603"))
    )
    (comp (ref "R70")
      (value "0")
      (footprint "eagle-import:0603")
      (fields (field (name "PARTNO") "CRCW06030000Z0EBC"))
      (libsource (lib "eagle-import") (part "RESISTOR0603"))
    )
    (comp (ref "R71")
      (value "0")
      (footprint "eagle-import:0603")
      (fields (field (name "PARTNO") "CRCW06030000Z0EBC"))
      (libsource (lib "eagle-import") (part "RESISTOR0603"))
    )
    (comp (ref "R72")
      (value "22")
      (footprint "eagle-import:0603")
      (fields (field (name "PARTNO") "CRCW060322R0FKEAC"))
      (libsource (lib "eagle-import") (part "RESISTOR0603"))
    )
    (comp (ref "R73")
      (value "22")
      (footprint "eagle-import:0603")
      (fields (field (name "PARTNO") "CRCW060322R0FKEAC"))
      (libsource (lib "eagle-import") (part "RESISTOR0603"))
    )
    (comp (ref "R74")
      (value "22")
      (footprint "eagle-import:0603")
      (fields (field (name "PARTNO") "CRCW060322R0FKEAC"))
      (libsource (lib "eagle-import") (part "RESISTOR0603"))
    )
    (comp (ref "R75")
      (value "0")
      (footprint "eagle-import:0603")
      (fields (field (name "PARTNO") "CRCW06030000Z0EBC"))
      (libsource (lib "eagle-import") (part "RESISTOR0603"))
    )
    (comp (ref "R76")
      (value "0")
      (footprint "eagle-import:0603")
      (fields (field (name "PARTNO") "CRCW06030000Z0EBC"))
      (libsource (lib "eagle-import") (part "RESISTOR0603"))
    )
    (comp (ref "R77")
      (value "22")
      (footprint "eagle-import:0603")
      (fields (field (name "PARTNO") "CRCW060322R0FKEAC"))
      (libsource (lib "eagle-import") (part "RESISTOR0603"))
    )
    (comp (ref "R78")
      (value "0")
      (footprint "eagle-import:0603")
      (fields (field (name "PARTNO") "CRCW06030000Z0EBC"))
      (libsource (lib "eagle-import") (part "RESISTOR0603"))
    )
    (comp (ref "R79")
      (value "0")
      (footprint "eagle-import:0603")
      (fields (field (name "PARTNO") "CRCW06030000Z0EBC"))
      (libsource (lib "eagle-import") (part "RESISTOR0603"))
    )
    (comp (ref "R80")
      (value "0")
      (footprint "eagle-import:0603")
      (fields (field (name "PARTNO") "CRCW06030000Z0EBC"))
      (libsource (lib "eagle-import") (part "RESISTOR0603"))
    )
    (comp (ref "R81")
      (value "0")
      (footprint "eagle-import:0603")
      (fields (field (name "PARTNO") "CRCW06030000Z0EBC"))
      (libsource (lib "eagle-import") (part "RESISTOR0603"))
    )
    (comp (ref "R82")
      (value "0")
      (footprint "eagle-import:0603")
      (fields (field (name "PARTNO") "CRCW06030000Z0EBC"))
      (libsource (lib "eagle-import") (part "RESISTOR0603"))
    )
    (comp (ref "R83")
      (value "22")
      (footprint "eagle-import:0603")
      (fields (field (name "PARTNO") "CRCW060322R0FKEAC"))
      (libsource (lib "eagle-import") (part "RESISTOR0603"))
    )
    (comp (ref "R84")
      (value "22")
      (footprint "eagle-import:0603")
      (fields (field (name "PARTNO") "CRCW060322R0FKEAC"))
      (libsource (lib "eagle-import") (part "RESISTOR0603"))
    )
    (comp (ref "R85")
      (value "22")
      (footprint "eagle-import:0603")
      (fields (field (name "PARTNO") "CRCW060322R0FKEAC"))
      (libsource (lib "eagle-import") (part "RESISTOR0603"))
    )
    (comp (ref "R86")
      (value "22")
      (footprint "eagle-import:0603")
      (fields (field (name "PARTNO") "CRCW060322R0FKEAC"))
      (libsource (lib "eagle-import") (part "RESISTOR0603"))
    )
    (comp (ref "R102")
      (value "1k")
      (footprint "eagle-import:0603")
      (fields (field (name "PARTNO") "CRCW06031K00FKEAC"))
      (libsource (lib "eagle-import") (part "RESISTOR0603"))
    )
    (comp (ref "R103")
      (value "1k")
      (footprint "eagle-import:0603")
      (fields (field (name "PARTNO") "CRCW06031K00FKEAC"))
      (libsource (lib "eagle-import") (part "RESISTOR0603"))
    )
    (comp (ref "R104")
      (value "1k")
      (footprint "eagle-import:0603")
      (fields (field (name "PARTNO") "CRCW06031K00FKEAC"))
      (libsource (lib "eagle-import") (part "RESISTOR0603"))
    )
    (comp (ref "R105")
      (value "1k")
      (footprint "eagle-import:0603")
      (fields (field (name "PARTNO") "CRCW06031K00FKEAC"))
      (libsource (lib "eagle-import") (part "RESISTOR0603"))
    )
    (comp (ref "U6")
      (value "PCM1681PWPPWP28_6P46X2P4-M")
      (footprint "eagle-import:PWP28_6P46X2P4-M")
      (fields
        (field (name "GENERIC_PART_NUMBER") "PCM1681")
        (field (name "MANUFACTURER") "Texas Instruments")
        (field (name "MANUFACTURER_PART_NUMBER") "PCM1681PWP")
        (field (name "PARTNO") "PCM1681PWP")
      )
      (libsource (lib "eagle-import") (part "PCM1681PWPPWP28_6P46X2P4-M"))
    )
    (comp (ref "U7")
      (value "PCM1681PWPPWP28_6P46X2P4-M")
      (footprint "eagle-import:PWP28_6P46X2P4-M")
      (fields
        (field (name "GENERIC_PART_NUMBER") "PCM1681")
        (field (name "MANUFACTURER") "Texas Instruments")
        (field (name "MANUFACTURER_PART_NUMBER") "PCM1681PWP")
        (field (name "PARTNO") "PCM1681PWP")
      )
      (libsource (lib "eagle-import") (part "PCM1681PWPPWP28_6P46X2P4-M"))
    )
    (comp (ref "C49")
      (value "10u")
      (footprint "eagle-import:0805")
      (fields (field (name "PARTNO") "CL21A106KAYNNNE"))
      (libsource (lib "eagle-import") (part "CAP_CERAMIC0805"))
    )
    (comp (ref "C50")
      (value "10u")
      (footprint "eagle-import:0805")
      (fields (field (name "PARTNO") "CL21A106KAYNNNE"))
      (libsource (lib "eagle-import") (part "CAP_CERAMIC0805"))
    )
    (comp (ref "C51")
      (value "10u")
      (footprint "eagle-import:0805")
      (fields (field (name "PARTNO") "CL21A106KAYNNNE"))
      (libsource (lib "eagle-import") (part "CAP_CERAMIC0805"))
    )
    (comp (ref "C52")
      (value "10u")
      (footprint "eagle-import:0805")
      (fields (field (name "PARTNO") "CL21A106KAYNNNE"))
      (libsource (lib "eagle-import") (part "CAP_CERAMIC0805"))
    )
    (comp (ref "C53")
      (value "10u")
      (footprint "eagle-import:0805")
      (fields (field (name "PARTNO") "CL21A106KAYNNNE"))
      (libsource (lib "eagle-import") (part "CAP_CERAMIC0805"))
    )
    (comp (ref "C77")
      (value "100u")
      (footprint "eagle-import:PANASONIC_D")
      (fields (field (name "PARTNO") "EEE-HAV101XAP"))
      (libsource (lib "eagle-import") (part "CAP_ELECTROLYTICPANASONIC_D"))
    )
    (comp (ref "C78")
      (value "4700pF")
      (footprint "eagle-import:0603")
      (fields (field (name "PARTNO") "GRM1885C1H472JA01D"))
      (libsource (lib "eagle-import") (part "CAP_CERAMIC0603"))
    )
    (comp (ref "C79")
      (value "4700pF")
      (footprint "eagle-import:0603")
      (fields (field (name "PARTNO") "GRM1885C1H472JA01D"))
      (libsource (lib "eagle-import") (part "CAP_CERAMIC0603"))
    )
    (comp (ref "C94")
      (value "2.2u")
      (footprint "eagle-import:0805")
      (fields (field (name "PARTNO") "UMK212BB7225KG-T"))
      (libsource (lib "eagle-import") (part "CAP_CERAMIC0805"))
    )
    (comp (ref "C95")
      (value "100n")
      (footprint "eagle-import:0603")
      (fields (field (name "PARTNO") "CC0603KRX7R9BB104"))
      (libsource (lib "eagle-import") (part "CAP_CERAMIC0603"))
    )
    (comp (ref "C96")
      (value "10u")
      (footprint "eagle-import:0805")
      (fields (field (name "PARTNO") "CL21A106KAYNNNE"))
      (libsource (lib "eagle-import") (part "CAP_CERAMIC0805"))
    )
    (comp (ref "C97")
      (value "1u")
      (footprint "eagle-import:1206")
      (fields (field (name "PARTNO") "12065C105M4Z2A"))
      (libsource (lib "eagle-import") (part "CAP_CERAMIC1206"))
    )
    (comp (ref "C98")
      (value "2.2u")
      (footprint "eagle-import:0805")
      (fields (field (name "PARTNO") "UMK212BB7225KG-T"))
      (libsource (lib "eagle-import") (part "CAP_CERAMIC0805"))
    )
    (comp (ref "C99")
      (value "100n")
      (footprint "eagle-import:0603")
      (fields (field (name "PARTNO") "CC0603KRX7R9BB104"))
      (libsource (lib "eagle-import") (part "CAP_CERAMIC0603"))
    )
    (comp (ref "C100")
      (value "10u")
      (footprint "eagle-import:0805")
      (fields (field (name "PARTNO") "CL21A106KAYNNNE"))
      (libsource (lib "eagle-import") (part "CAP_CERAMIC0805"))
    )
    (comp (ref "C101")
      (value "1u")
      (footprint "eagle-import:1206")
      (fields (field (name "PARTNO") "12065C105M4Z2A"))
      (libsource (lib "eagle-import") (part "CAP_CERAMIC1206"))
    )
    (comp (ref "C102")
      (value "100n")
      (footprint "eagle-import:0603")
      (fields (field (name "PARTNO") "CC0603KRX7R9BB104"))
      (libsource (lib "eagle-import") (part "CAP_CERAMIC0603"))
    )
    (comp (ref "D1")
      (value "MBR120LSFT3G")
      (footprint "eagle-import:SOD-123")
      (libsource (lib "eagle-import") (part "DIODESOD-123"))
    )
    (comp (ref "D2")
      (value "MBR120LSFT3G")
      (footprint "eagle-import:SOD-123")
      (libsource (lib "eagle-import") (part "DIODESOD-123"))
    )
    (comp (ref "D3")
      (value "MBR120LSFT3G")
      (footprint "eagle-import:SOD-123")
      (libsource (lib "eagle-import") (part "DIODESOD-123"))
    )
    (comp (ref "D4")
      (value "MBR120LSFT3G")
      (footprint "eagle-import:SOD-123")
      (libsource (lib "eagle-import") (part "DIODESOD-123"))
    )
    (comp (ref "IC10")
      (value "LM317")
      (footprint "eagle-import:SOT223")
      (fields (field (name "PARTNO") "LM317MBSTT3G"))
      (libsource (lib "eagle-import") (part "LM317"))
    )
    (comp (ref "IC11")
      (value "LM337")
      (footprint "eagle-import:SOT223")
      (fields (field (name "PARTNO") "LM337IMPX/NOPB"))
      (libsource (lib "eagle-import") (part "LM337"))
    )
    (comp (ref "JP6")
      (value "JP4QE")
      (footprint "eagle-import:JP4Q")
      (fields (field (name "PARTNO") "M20-9760446"))
      (libsource (lib "eagle-import") (part "JP4QE"))
    )
    (comp (ref "L1")
      (value "600ohm @ 100MHz")
      (footprint "eagle-import:0603")
      (fields (field (name "PARTNO") "BLM18KG601SN1D"))
      (libsource (lib "eagle-import") (part "INDUCTOR0603"))
    )
    (comp (ref "L5")
      (value "600ohm @ 100MHz")
      (footprint "eagle-import:0603")
      (fields (field (name "PARTNO") "BLM18KG601SN1D"))
      (libsource (lib "eagle-import") (part "INDUCTOR0603"))
    )
    (comp (ref "L6")
      (value "600ohm @ 100MHz")
      (footprint "eagle-import:0603")
      (fields (field (name "PARTNO") "BLM18KG601SN1D"))
      (libsource (lib "eagle-import") (part "INDUCTOR0603"))
    )
    (comp (ref "L7")
      (value "5.6uH")
      (footprint "eagle-import:L1812")
      (fields (field (name "PARTNO") "PM1812-5R6J-RC"))
      (libsource (lib "eagle-import") (part "L-USL1812"))
    )
    (comp (ref "LED1")
      (value "WP934SA_LILYLGDLED")
      (footprint "eagle-import:WP934SALILYLGD")
      (fields (field (name "PARTNO") "WP934SA/LILYLGD"))
      (libsource (lib "eagle-import") (part "WP934SA_LILYLGDLED"))
    )
    (comp (ref "LED2")
      (value "LED0805")
      (footprint "eagle-import:CHIPLED_0805")
      (fields (field (name "PARTNO") "AP2012HD"))
      (libsource (lib "eagle-import") (part "LED0805"))
    )
    (comp (ref "PL1")
      (value "NSJ12HC")
      (footprint "eagle-import:NSJ12HF1")
      (fields
        (field (name "MANUFACTURER_PART_NUMBER") "NSJ12HF-1")
        (field (name "MOUSER_PART_NUMBER") "568-NSJ12HF-1")
      )
      (libsource (lib "eagle-import") (part "NSJ12HF-1"))
    )
    (comp (ref "PL2")
      (value "NSJ12HC")
      (footprint "eagle-import:NSJ12HF1")
      (fields
        (field (name "MANUFACTURER_PART_NUMBER") "NSJ12HF-1")
        (field (name "MOUSER_PART_NUMBER") "568-NSJ12HF-1")
      )
      (libsource (lib "eagle-import") (part "NSJ12HF-1"))
    )
    (comp (ref "PL3")
      (value "NSJ12HC")
      (footprint "eagle-import:NSJ12HF1")
      (fields
        (field (name "MANUFACTURER_PART_NUMBER") "NSJ12HF-1")
        (field (name "MOUSER_PART_NUMBER") "568-NSJ12HF-1")
      )
      (libsource (lib "eagle-import") (part "NSJ12HF-1"))
    )
    (comp (ref "PL4")
      (value "NSJ12HC")
      (footprint "eagle-import:NSJ12HF1")
      (fields
        (field (name "MANUFACTURER_PART_NUMBER") "NSJ12HF-1")
        (field (name "MOUSER_PART_NUMBER") "568-NSJ12HF-1")
      )
      (libsource (lib "eagle-import") (part "NSJ12HF-1"))
    )
    (comp (ref "PL5")
      (value "NSJ12HC")
      (footprint "eagle-import:NSJ12HF1")
      (fields
        (field (name "MANUFACTURER_PART_NUMBER") "NSJ12HF-1")
        (field (name "MOUSER_PART_NUMBER") "568-NSJ12HF-1")
      )
      (libsource (lib "eagle-import") (part "NSJ12HF-1"))
    )
    (comp (ref "PL6")
      (value "NSJ12HC")
      (footprint "eagle-import:NSJ12HF1")
      (fields
        (field (name "MANUFACTURER_PART_NUMBER") "NSJ12HF-1")
        (field (name "MOUSER_PART_NUMBER") "568-NSJ12HF-1")
      )
      (libsource (lib "eagle-import") (part "NSJ12HF-1"))
    )
    (comp (ref "R49")
      (value "1k")
      (footprint "eagle-import:0603")
      (fields (field (name "PARTNO") "CRCW06031K00FKEAC"))
      (libsource (lib "eagle-import") (part "RESISTOR0603"))
    )
    (comp (ref "R57")
      (value "1M")
      (footprint "eagle-import:0603")
      (fields (field (name "PARTNO") "AC0603FR-131ML"))
      (libsource (lib "eagle-import") (part "RESISTOR0603"))
    )
    (comp (ref "R58")
      (value "1M")
      (footprint "eagle-import:0603")
      (fields (field (name "PARTNO") "AC0603FR-131ML"))
      (libsource (lib "eagle-import") (part "RESISTOR0603"))
    )
    (comp (ref "R59")
      (value "0")
      (footprint "eagle-import:0603")
      (fields (field (name "PARTNO") "CRCW06030000Z0EBC"))
      (libsource (lib "eagle-import") (part "RESISTOR0603"))
    )
    (comp (ref "R60")
      (value "0")
      (footprint "eagle-import:0603")
      (fields (field (name "PARTNO") "CRCW06030000Z0EBC"))
      (libsource (lib "eagle-import") (part "RESISTOR0603"))
    )
    (comp (ref "R61")
      (value "0")
      (footprint "eagle-import:0603")
      (fields (field (name "PARTNO") "CRCW06030000Z0EBC"))
      (libsource (lib "eagle-import") (part "RESISTOR0603"))
    )
    (comp (ref "R62")
      (value "0")
      (footprint "eagle-import:0603")
      (fields (field (name "PARTNO") "CRCW06030000Z0EBC"))
      (libsource (lib "eagle-import") (part "RESISTOR0603"))
    )
    (comp (ref "R94")
      (value "240 0.1%")
      (footprint "eagle-import:0603")
      (fields (field (name "PARTNO") "ERA-3AEB241V"))
      (libsource (lib "eagle-import") (part "RESISTOR0603"))
    )
    (comp (ref "R95")
      (value "2.2k 0.1%")
      (footprint "eagle-import:0603")
      (fields (field (name "PARTNO") "ERA-3VEB2201V"))
      (libsource (lib "eagle-import") (part "RESISTOR0603"))
    )
    (comp (ref "R96")
      (value "2.2k 0.1%")
      (footprint "eagle-import:0603")
      (fields (field (name "PARTNO") "ERA-3VEB2201V"))
      (libsource (lib "eagle-import") (part "RESISTOR0603"))
    )
    (comp (ref "R97")
      (value "240 0.1%")
      (footprint "eagle-import:0603")
      (fields (field (name "PARTNO") "ERA-3AEB241V"))
      (libsource (lib "eagle-import") (part "RESISTOR0603"))
    )
    (comp (ref "R98")
      (value "1k")
      (footprint "eagle-import:0603")
      (fields (field (name "PARTNO") "CRCW06031K00FKEAC"))
      (libsource (lib "eagle-import") (part "RESISTOR0603"))
    )
    (comp (ref "R99")
      (value "1k")
      (footprint "eagle-import:0603")
      (fields (field (name "PARTNO") "CRCW06031K00FKEAC"))
      (libsource (lib "eagle-import") (part "RESISTOR0603"))
    )
    (comp (ref "R100")
      (value "1k")
      (footprint "eagle-import:0603")
      (fields (field (name "PARTNO") "CRCW06031K00FKEAC"))
      (libsource (lib "eagle-import") (part "RESISTOR0603"))
    )
    (comp (ref "R101")
      (value "1k")
      (footprint "eagle-import:0603")
      (fields (field (name "PARTNO") "CRCW06031K00FKEAC"))
      (libsource (lib "eagle-import") (part "RESISTOR0603"))
    )
    (comp (ref "TP1")
      (value "TPPAD1-13")
      (footprint "eagle-import:P1-13")
      (fields (field (name "PARTNO") "5001"))
      (libsource (lib "eagle-import") (part "TPPAD1-13"))
    )
    (comp (ref "TP2")
      (value "TPPAD1-13")
      (footprint "eagle-import:P1-13")
      (fields (field (name "PARTNO") "5001"))
      (libsource (lib "eagle-import") (part "TPPAD1-13"))
    )
    (comp (ref "TP3")
      (value "TPPAD1-13")
      (footprint "eagle-import:P1-13")
      (fields (field (name "PARTNO") "5001"))
      (libsource (lib "eagle-import") (part "TPPAD1-13"))
    )
    (comp (ref "TP4")
      (value "TPPAD1-13")
      (footprint "eagle-import:P1-13")
      (fields (field (name "PARTNO") "5001"))
      (libsource (lib "eagle-import") (part "TPPAD1-13"))
    )
    (comp (ref "TP5")
      (value "TPPAD1-13")
      (footprint "eagle-import:P1-13")
      (fields (field (name "PARTNO") "5001"))
      (libsource (lib "eagle-import") (part "TPPAD1-13"))
    )
    (comp (ref "U$1")
      (value "WBL2UOAGQR05CLR")
      (footprint "eagle-import:WBL2UOAGQ")
      (libsource (lib "eagle-import") (part "WBL2UOAGQR05CLR"))
    )
    (comp (ref "U$2")
      (value "PHI-LOGO")
      (footprint "eagle-import:PHI-LOGO")
      (libsource (lib "eagle-import") (part "PHI-LOGO"))
    )
    (comp (ref "U1")
      (value "LM1117DTX-3.3")
      (footprint "eagle-import:TO252")
      (fields (field (name "PARTNO") "LM1117DTX-3.3/NOPB"))
      (libsource (lib "eagle-import") (part "LM1117TO252"))
    )
    (comp (ref "U2")
      (value "PCN2-S5-D15-S")
      (footprint "eagle-import:CONV_PCN2-S5-D12-S")
      (fields (field (name "MANUFACTURER") "CUI INC"))
      (libsource (lib "eagle-import") (part "PCN2-S5-D12-S"))
    )
    (comp (ref "U4")
      (value "USBLC6-2SC6YSOT23-6L_STM-M")
      (footprint "eagle-import:SOT23-6L_STM-M")
      (fields (field (name "MANUFACTURER_PART_NUMBER") "USBLC6-2SC6Y"))
      (libsource (lib "eagle-import") (part "USBLC6-2SC6YSOT23-6L_STM-M"))
    )
    (comp (ref "U5")
      (value "USBLC6-2SC6YSOT23-6L_STM-M")
      (footprint "eagle-import:SOT23-6L_STM-M")
      (fields (field (name "MANUFACTURER_PART_NUMBER") "USBLC6-2SC6Y"))
      (libsource (lib "eagle-import") (part "USBLC6-2SC6YSOT23-6L_STM-M"))
    )
    (comp (ref "USB_FS")
      (value "TE-292304-1")
      (footprint "eagle-import:TE-292304-1")
      (fields (field (name "MPN") "292304-1 ") (field (name "PARTNO") "292304-1"))
      (libsource (lib "eagle-import") (part "TE-292304-1"))
    )
    (comp (ref "USB_HS")
      (value "FCI-73725-0110BLF")
      (footprint "eagle-import:FCI-73725-0110BLF")
      (fields (field (name "PARTNO") "73725-0110BLF"))
      (libsource (lib "eagle-import") (part "FCI-73725-0110BLF"))
    )
    (comp (ref "C54")
      (value "100n")
      (footprint "eagle-import:0603")
      (fields (field (name "PARTNO") "CC0603KRX7R9BB104"))
      (libsource (lib "eagle-import") (part "CAP_CERAMIC0603"))
    )
    (comp (ref "C55")
      (value "2.2u")
      (footprint "eagle-import:1206")
      (fields (field (name "PARTNO") "CL31B225KBHNNNE"))
      (libsource (lib "eagle-import") (part "CAP_CERAMIC1206"))
    )
    (comp (ref "C56")
      (value "2.2u")
      (footprint "eagle-import:1206")
      (fields (field (name "PARTNO") "CL31B225KBHNNNE"))
      (libsource (lib "eagle-import") (part "CAP_CERAMIC1206"))
    )
    (comp (ref "C57")
      (value "100n")
      (footprint "eagle-import:0603")
      (fields (field (name "PARTNO") "CC0603KRX7R9BB104"))
      (libsource (lib "eagle-import") (part "CAP_CERAMIC0603"))
    )
    (comp (ref "C58")
      (value "100n")
      (footprint "eagle-import:0603")
      (fields (field (name "PARTNO") "CC0603KRX7R9BB104"))
      (libsource (lib "eagle-import") (part "CAP_CERAMIC0603"))
    )
    (comp (ref "C59")
      (value "100n")
      (footprint "eagle-import:0603")
      (fields (field (name "PARTNO") "CC0603KRX7R9BB104"))
      (libsource (lib "eagle-import") (part "CAP_CERAMIC0603"))
    )
    (comp (ref "C60")
      (value "100n")
      (footprint "eagle-import:0603")
      (fields (field (name "PARTNO") "CC0603KRX7R9BB104"))
      (libsource (lib "eagle-import") (part "CAP_CERAMIC0603"))
    )
    (comp (ref "C61")
      (value "100n")
      (footprint "eagle-import:0603")
      (fields (field (name "PARTNO") "CC0603KRX7R9BB104"))
      (libsource (lib "eagle-import") (part "CAP_CERAMIC0603"))
    )
    (comp (ref "C62")
      (value "100n")
      (footprint "eagle-import:0603")
      (fields (field (name "PARTNO") "CC0603KRX7R9BB104"))
      (libsource (lib "eagle-import") (part "CAP_CERAMIC0603"))
    )
    (comp (ref "C63")
      (value "100n")
      (footprint "eagle-import:0603")
      (fields (field (name "PARTNO") "CC0603KRX7R9BB104"))
      (libsource (lib "eagle-import") (part "CAP_CERAMIC0603"))
    )
    (comp (ref "C64")
      (value "100n")
      (footprint "eagle-import:0603")
      (fields (field (name "PARTNO") "CC0603KRX7R9BB104"))
      (libsource (lib "eagle-import") (part "CAP_CERAMIC0603"))
    )
    (comp (ref "C65")
      (value "100n")
      (footprint "eagle-import:0603")
      (fields (field (name "PARTNO") "CC0603KRX7R9BB104"))
      (libsource (lib "eagle-import") (part "CAP_CERAMIC0603"))
    )
    (comp (ref "C66")
      (value "100n")
      (footprint "eagle-import:0603")
      (fields (field (name "PARTNO") "CC0603KRX7R9BB104"))
      (libsource (lib "eagle-import") (part "CAP_CERAMIC0603"))
    )
    (comp (ref "C67")
      (value "100n")
      (footprint "eagle-import:0603")
      (fields (field (name "PARTNO") "CC0603KRX7R9BB104"))
      (libsource (lib "eagle-import") (part "CAP_CERAMIC0603"))
    )
    (comp (ref "C68")
      (value "100n")
      (footprint "eagle-import:0603")
      (fields (field (name "PARTNO") "CC0603KRX7R9BB104"))
      (libsource (lib "eagle-import") (part "CAP_CERAMIC0603"))
    )
    (comp (ref "C69")
      (value "100n")
      (footprint "eagle-import:0603")
      (fields (field (name "PARTNO") "CC0603KRX7R9BB104"))
      (libsource (lib "eagle-import") (part "CAP_CERAMIC0603"))
    )
    (comp (ref "C70")
      (value "100n")
      (footprint "eagle-import:0603")
      (fields (field (name "PARTNO") "CC0603KRX7R9BB104"))
      (libsource (lib "eagle-import") (part "CAP_CERAMIC0603"))
    )
    (comp (ref "C71")
      (value "100n")
      (footprint "eagle-import:0603")
      (fields (field (name "PARTNO") "CC0603KRX7R9BB104"))
      (libsource (lib "eagle-import") (part "CAP_CERAMIC0603"))
    )
    (comp (ref "C72")
      (value "2.2u")
      (footprint "eagle-import:1206")
      (fields (field (name "PARTNO") "CL31B225KBHNNNE"))
      (libsource (lib "eagle-import") (part "CAP_CERAMIC1206"))
    )
    (comp (ref "C73")
      (value "18pF")
      (footprint "eagle-import:0603")
      (fields (field (name "PARTNO") "06035A180JAT2A"))
      (libsource (lib "eagle-import") (part "CAP_CERAMIC0603"))
    )
    (comp (ref "C74")
      (value "18pF")
      (footprint "eagle-import:0603")
      (fields (field (name "PARTNO") "06035A180JAT2A"))
      (libsource (lib "eagle-import") (part "CAP_CERAMIC0603"))
    )
    (comp (ref "C75")
      (value "4.7u")
      (footprint "eagle-import:0603")
      (fields (field (name "PARTNO") "GRM188Z71A475ME15D"))
      (libsource (lib "eagle-import") (part "CAP_CERAMIC0603"))
    )
    (comp (ref "C76")
      (value "100n")
      (footprint "eagle-import:0603")
      (fields (field (name "PARTNO") "CC0603KRX7R9BB104"))
      (libsource (lib "eagle-import") (part "CAP_CERAMIC0603"))
    )
    (comp (ref "C103")
      (value "100n")
      (footprint "eagle-import:0603")
      (fields (field (name "PARTNO") "CC0603KRX7R9BB104"))
      (libsource (lib "eagle-import") (part "CAP_CERAMIC0603"))
    )
    (comp (ref "H1")
      (value "MOUNT-HOLE3.3")
      (footprint "eagle-import:3,3")
      (libsource (lib "eagle-import") (part "MOUNT-HOLE3.3"))
    )
    (comp (ref "H2")
      (value "MOUNT-HOLE3.3")
      (footprint "eagle-import:3,3")
      (libsource (lib "eagle-import") (part "MOUNT-HOLE3.3"))
    )
    (comp (ref "H3")
      (value "MOUNT-HOLE3.3")
      (footprint "eagle-import:3,3")
      (libsource (lib "eagle-import") (part "MOUNT-HOLE3.3"))
    )
    (comp (ref "H4")
      (value "MOUNT-HOLE3.3")
      (footprint "eagle-import:3,3")
      (libsource (lib "eagle-import") (part "MOUNT-HOLE3.3"))
    )
    (comp (ref "H5")
      (value "MOUNT-HOLE3.3")
      (footprint "eagle-import:3,3")
      (libsource (lib "eagle-import") (part "MOUNT-HOLE3.3"))
    )
    (comp (ref "H6")
      (value "MOUNT-HOLE3.3")
      (footprint "eagle-import:3,3")
      (libsource (lib "eagle-import") (part "MOUNT-HOLE3.3"))
    )
    (comp (ref "H7")
      (value "MOUNT-HOLE3.3")
      (footprint "eagle-import:3,3")
      (libsource (lib "eagle-import") (part "MOUNT-HOLE3.3"))
    )
    (comp (ref "IC7")
      (value "AT45DB161D-SU")
      (footprint "eagle-import:SOIC8")
      (fields (field (name "MF") "ATMEL"))
      (libsource (lib "eagle-import") (part "AT45DB161D-SU"))
    )
    (comp (ref "OSC1")
      (value "12.288MHz")
      (footprint "eagle-import:OSC_7X5MM")
      (fields (field (name "PARTNO") "C3391-12.288"))
      (libsource (lib "eagle-import") (part "OSCILLATOR"))
    )
    (comp (ref "R50")
      (value "10k")
      (footprint "eagle-import:0603")
      (fields (field (name "PARTNO") "CRCW060310K0JNEBC"))
      (libsource (lib "eagle-import") (part "RESISTOR0603"))
    )
    (comp (ref "R51")
      (value "10k")
      (footprint "eagle-import:0603")
      (fields (field (name "PARTNO") "CRCW060310K0JNEBC"))
      (libsource (lib "eagle-import") (part "RESISTOR0603"))
    )
    (comp (ref "R52")
      (value "10k")
      (footprint "eagle-import:0603")
      (fields (field (name "PARTNO") "CRCW060310K0JNEBC"))
      (libsource (lib "eagle-import") (part "RESISTOR0603"))
    )
    (comp (ref "R53")
      (value "10k")
      (footprint "eagle-import:0603")
      (fields (field (name "PARTNO") "CRCW060310K0JNEBC"))
      (libsource (lib "eagle-import") (part "RESISTOR0603"))
    )
    (comp (ref "R54")
      (value "3k 1%")
      (footprint "eagle-import:0603")
      (fields (field (name "PARTNO") "AF0603FR-073KL"))
      (libsource (lib "eagle-import") (part "RESISTOR0603"))
    )
    (comp (ref "R55")
      (value "10k")
      (footprint "eagle-import:0603")
      (fields (field (name "PARTNO") "CRCW060310K0JNEBC"))
      (libsource (lib "eagle-import") (part "RESISTOR0603"))
    )
    (comp (ref "R56")
      (value "0")
      (footprint "eagle-import:0603")
      (fields (field (name "PARTNO") "CRCW06030000Z0EBC"))
      (libsource (lib "eagle-import") (part "RESISTOR0603"))
    )
    (comp (ref "R88")
      (value "22")
      (footprint "eagle-import:0603")
      (fields (field (name "PARTNO") "CRCW060322R0FKEAC"))
      (libsource (lib "eagle-import") (part "RESISTOR0603"))
    )
    (comp (ref "R89")
      (value "22")
      (footprint "eagle-import:0603")
      (fields (field (name "PARTNO") "CRCW060322R0FKEAC"))
      (libsource (lib "eagle-import") (part "RESISTOR0603"))
    )
    (comp (ref "R90")
      (value "22")
      (footprint "eagle-import:0603")
      (fields (field (name "PARTNO") "CRCW060322R0FKEAC"))
      (libsource (lib "eagle-import") (part "RESISTOR0603"))
    )
    (comp (ref "R91")
      (value "22")
      (footprint "eagle-import:0603")
      (fields (field (name "PARTNO") "CRCW060322R0FKEAC"))
      (libsource (lib "eagle-import") (part "RESISTOR0603"))
    )
    (comp (ref "R92")
      (value "4.7k")
      (footprint "eagle-import:0603")
      (fields (field (name "PARTNO") "CRCW06034K70FKEA"))
      (libsource (lib "eagle-import") (part "RESISTOR0603"))
    )
    (comp (ref "R93")
      (value "4.7k")
      (footprint "eagle-import:0603")
      (fields (field (name "PARTNO") "CRCW06034K70FKEA"))
      (libsource (lib "eagle-import") (part "RESISTOR0603"))
    )
    (comp (ref "TC1")
      (value "TC2050-IDC-NL")
      (footprint "eagle-import:TC2050-IDC-NL")
      (libsource (lib "eagle-import") (part "TC2050-IDC-NL"))
    )
    (comp (ref "TP7")
      (value "TPPAD1-13")
      (footprint "eagle-import:P1-13")
      (fields (field (name "PARTNO") "5001"))
      (libsource (lib "eagle-import") (part "TPPAD1-13"))
    )
    (comp (ref "TP8")
      (value "TPPAD1-13")
      (footprint "eagle-import:P1-13")
      (fields (field (name "PARTNO") "5001"))
      (libsource (lib "eagle-import") (part "TPPAD1-13"))
    )
    (comp (ref "TP9")
      (value "TPPAD1-13")
      (footprint "eagle-import:P1-13")
      (fields (field (name "PARTNO") "5001"))
      (libsource (lib "eagle-import") (part "TPPAD1-13"))
    )
    (comp (ref "TP10")
      (value "TPPAD1-13")
      (footprint "eagle-import:P1-13")
      (fields (field (name "PARTNO") "5001"))
      (libsource (lib "eagle-import") (part "TPPAD1-13"))
    )
    (comp (ref "TP16")
      (value "TPPAD1-13")
      (footprint "eagle-import:P1-13")
      (fields (field (name "PARTNO") "5001"))
      (libsource (lib "eagle-import") (part "TPPAD1-13"))
    )
    (comp (ref "TP17")
      (value "TPPAD1-13")
      (footprint "eagle-import:P1-13")
      (fields (field (name "PARTNO") "5001"))
      (libsource (lib "eagle-import") (part "TPPAD1-13"))
    )
    (comp (ref "TP18")
      (value "TPPAD1-13")
      (footprint "eagle-import:P1-13")
      (fields (field (name "PARTNO") "5001"))
      (libsource (lib "eagle-import") (part "TPPAD1-13"))
    )
    (comp (ref "U3")
      (value "STM32F7X3ZXT")
      (footprint "eagle-import:LQFP144-20X20MM")
      (fields
        (field (name "PARTNO") "STM32F733ZET6")
        (field (name "COPYRIGHT") "Copyright (C) 2016 Accelerated Designs. All rights reserved")
      )
      (libsource (lib "eagle-import") (part "STM32F7X3ZXT"))
    )
    (comp (ref "Y1")
      (value "ABLS7M2-25.000MHZ-D2Y-T")
      (footprint "eagle-import:ABLS7M225000MHZD2YT")
      (libsource (lib "eagle-import") (part "CRYSTALABLS7M2"))
    )
  )
  (nets
    (net (code "1") (name "+3V3") (class "Default")
      (node (ref "C103") (pin "1") (pinfunction "P$1_1") (pintype "passive"))
      (node (ref "C54") (pin "2") (pinfunction "P$2_2") (pintype "passive"))
      (node (ref "C57") (pin "2") (pinfunction "P$2_2") (pintype "passive"))
      (node (ref "C58") (pin "2") (pinfunction "P$2_2") (pintype "passive"))
      (node (ref "C59") (pin "2") (pinfunction "P$2_2") (pintype "passive"))
      (node (ref "C60") (pin "2") (pinfunction "P$2_2") (pintype "passive"))
      (node (ref "C61") (pin "2") (pinfunction "P$2_2") (pintype "passive"))
      (node (ref "C62") (pin "2") (pinfunction "P$2_2") (pintype "passive"))
      (node (ref "C63") (pin "2") (pinfunction "P$2_2") (pintype "passive"))
      (node (ref "C64") (pin "2") (pinfunction "P$2_2") (pintype "passive"))
      (node (ref "C65") (pin "2") (pinfunction "P$2_2") (pintype "passive"))
      (node (ref "C66") (pin "2") (pinfunction "P$2_2") (pintype "passive"))
      (node (ref "C67") (pin "2") (pinfunction "P$2_2") (pintype "passive"))
      (node (ref "C68") (pin "2") (pinfunction "P$2_2") (pintype "passive"))
      (node (ref "C69") (pin "2") (pinfunction "P$2_2") (pintype "passive"))
      (node (ref "C70") (pin "2") (pinfunction "P$2_2") (pintype "passive"))
      (node (ref "C75") (pin "2") (pinfunction "P$2_2") (pintype "passive"))
      (node (ref "C76") (pin "2") (pinfunction "P$2_2") (pintype "passive"))
      (node (ref "C80") (pin "2") (pinfunction "P$2_2") (pintype "passive"))
      (node (ref "C81") (pin "+") (pinfunction "+_+") (pintype "passive"))
      (node (ref "C86") (pin "2") (pinfunction "P$2_2") (pintype "passive"))
      (node (ref "C87") (pin "+") (pinfunction "+_+") (pintype "passive"))
      (node (ref "IC7") (pin "3") (pinfunction "~{RESET}_3") (pintype "input"))
      (node (ref "IC7") (pin "5") (pinfunction "~{WP}_5") (pintype "input"))
      (node (ref "IC7") (pin "6") (pinfunction "VCC_6") (pintype "power_in"))
      (node (ref "L1") (pin "2") (pinfunction "2_2") (pintype "passive"))
      (node (ref "OSC1") (pin "4") (pinfunction "VCC_4") (pintype "power_in"))
      (node (ref "R50") (pin "1") (pinfunction "1_1") (pintype "passive"))
      (node (ref "R51") (pin "2") (pinfunction "2_2") (pintype "passive"))
      (node (ref "R53") (pin "2") (pinfunction "2_2") (pintype "passive"))
      (node (ref "R55") (pin "2") (pinfunction "2_2") (pintype "passive"))
      (node (ref "R80") (pin "1") (pinfunction "1_1") (pintype "passive"))
      (node (ref "R92") (pin "2") (pinfunction "2_2") (pintype "passive"))
      (node (ref "R93") (pin "2") (pinfunction "2_2") (pintype "passive"))
      (node (ref "TC1") (pin "1") (pinfunction "1_1") (pintype "passive"))
      (node (ref "U3") (pin "108") (pinfunction "VDD_9_108") (pintype "power_in"))
      (node (ref "U3") (pin "121") (pinfunction "VDDSDMMC_121") (pintype "power_in"))
      (node (ref "U3") (pin "131") (pinfunction "VDD_10_131") (pintype "power_in"))
      (node (ref "U3") (pin "144") (pinfunction "VDD_144") (pintype "power_in"))
      (node (ref "U3") (pin "17") (pinfunction "VDD_2_17") (pintype "power_in"))
      (node (ref "U3") (pin "30") (pinfunction "VDD_3_30") (pintype "power_in"))
      (node (ref "U3") (pin "32") (pinfunction "VREF+_32") (pintype "power_in"))
      (node (ref "U3") (pin "33") (pinfunction "VDDA_33") (pintype "power_in"))
      (node (ref "U3") (pin "39") (pinfunction "VDD_4_39") (pintype "power_in"))
      (node (ref "U3") (pin "52") (pinfunction "VDD_5_52") (pintype "bidirectional"))
      (node (ref "U3") (pin "6") (pinfunction "VBAT_6") (pintype "power_in"))
      (node (ref "U3") (pin "62") (pinfunction "VDD_6_62") (pintype "power_in"))
      (node (ref "U3") (pin "72") (pinfunction "VDD_7_72") (pintype "power_in"))
      (node (ref "U3") (pin "86") (pinfunction "VDD_8_86") (pintype "power_in"))
      (node (ref "U3") (pin "95") (pinfunction "VDDUSB_95") (pintype "power_in"))
      (node (ref "U6") (pin "9") (pinfunction "VDD_9") (pintype "power_in"))
      (node (ref "U7") (pin "9") (pinfunction "VDD_9") (pintype "power_in"))
    )
    (net (code "2") (name "+5V") (class "Default")
      (node (ref "C49") (pin "2") (pinfunction "P$2_2") (pintype "passive"))
      (node (ref "C77") (pin "+") (pinfunction "+_+") (pintype "passive"))
      (node (ref "JP6") (pin "2") (pinfunction "2_2") (pintype "passive"))
      (node (ref "L3") (pin "1") (pinfunction "1_1") (pintype "passive"))
      (node (ref "L4") (pin "1") (pinfunction "1_1") (pintype "passive"))
      (node (ref "U1") (pin "2") (pinfunction "IN_2") (pintype "input"))
      (node (ref "U3") (pin "101") (pinfunction "PA9_101") (pintype "bidirectional"))
      (node (ref "U3") (pin "74") (pinfunction "PB13_74") (pintype "bidirectional"))
      (node (ref "U4") (pin "5") (pinfunction "VBUS_5") (pintype "power_in"))
      (node (ref "U5") (pin "5") (pinfunction "VBUS_5") (pintype "power_in"))
      (node (ref "USB_FS") (pin "1") (pinfunction "1_1") (pintype "bidirectional"))
      (node (ref "USB_HS") (pin "P$1") (pinfunction "1_P$1") (pintype "passive"))
    )
    (net (code "3") (name "+12V") (class "Default")
      (node (ref "C12") (pin "1") (pinfunction "P$1_1") (pintype "passive"))
      (node (ref "C20") (pin "1") (pinfunction "P$1_1") (pintype "passive"))
      (node (ref "C28") (pin "1") (pinfunction "P$1_1") (pintype "passive"))
      (node (ref "C36") (pin "1") (pinfunction "P$1_1") (pintype "passive"))
      (node (ref "C4") (pin "1") (pinfunction "P$1_1") (pintype "passive"))
      (node (ref "C44") (pin "1") (pinfunction "P$1_1") (pintype "passive"))
      (node (ref "IC1") (pin "8") (pinfunction "V+_8") (pintype "power_in"))
      (node (ref "IC2") (pin "8") (pinfunction "V+_8") (pintype "power_in"))
      (node (ref "IC3") (pin "8") (pinfunction "V+_8") (pintype "power_in"))
      (node (ref "IC4") (pin "8") (pinfunction "V+_8") (pintype "power_in"))
      (node (ref "IC5") (pin "8") (pinfunction "V+_8") (pintype "power_in"))
      (node (ref "IC6") (pin "8") (pinfunction "V+_8") (pintype "power_in"))
      (node (ref "L5") (pin "2") (pinfunction "2_2") (pintype "passive"))
    )
    (net (code "4") (name "+15V") (class "Default")
      (node (ref "C52") (pin "2") (pinfunction "P$2_2") (pintype "passive"))
      (node (ref "C94") (pin "2") (pinfunction "P$2_2") (pintype "passive"))
      (node (ref "C95") (pin "1") (pinfunction "P$1_1") (pintype "passive"))
      (node (ref "D2") (pin "C") (pinfunction "C_C") (pintype "passive"))
      (node (ref "IC10") (pin "3") (pinfunction "IN_3") (pintype "bidirectional"))
      (node (ref "JP6") (pin "8") (pinfunction "2_8") (pintype "passive"))
      (node (ref "TP3") (pin "TP") (pinfunction "TP_TP") (pintype "input"))
    )
    (net (code "5") (name "-12V") (class "Default")
      (node (ref "C16") (pin "2") (pinfunction "P$2_2") (pintype "passive"))
      (node (ref "C24") (pin "2") (pinfunction "P$2_2") (pintype "passive"))
      (node (ref "C32") (pin "2") (pinfunction "P$2_2") (pintype "passive"))
      (node (ref "C40") (pin "2") (pinfunction "P$2_2") (pintype "passive"))
      (node (ref "C48") (pin "2") (pinfunction "P$2_2") (pintype "passive"))
      (node (ref "C8") (pin "2") (pinfunction "P$2_2") (pintype "passive"))
      (node (ref "IC1") (pin "4") (pinfunction "V-_4") (pintype "power_in"))
      (node (ref "IC2") (pin "4") (pinfunction "V-_4") (pintype "power_in"))
      (node (ref "IC3") (pin "4") (pinfunction "V-_4") (pintype "power_in"))
      (node (ref "IC4") (pin "4") (pinfunction "V-_4") (pintype "power_in"))
      (node (ref "IC5") (pin "4") (pinfunction "V-_4") (pintype "power_in"))
      (node (ref "IC6") (pin "4") (pinfunction "V-_4") (pintype "power_in"))
      (node (ref "L6") (pin "2") (pinfunction "2_2") (pintype "passive"))
    )
    (net (code "6") (name "-15V") (class "Default")
      (node (ref "C53") (pin "2") (pinfunction "P$2_2") (pintype "passive"))
      (node (ref "C98") (pin "1") (pinfunction "P$1_1") (pintype "passive"))
      (node (ref "C99") (pin "2") (pinfunction "P$2_2") (pintype "passive"))
      (node (ref "D3") (pin "A") (pinfunction "A_A") (pintype "passive"))
      (node (ref "IC11") (pin "2") (pinfunction "IN_2") (pintype "bidirectional"))
      (node (ref "IC11") (pin "4") (pinfunction "IN_TAB_4") (pintype "bidirectional"))
      (node (ref "JP6") (pin "4") (pinfunction "2_4") (pintype "passive"))
      (node (ref "TP4") (pin "TP") (pinfunction "TP_TP") (pintype "input"))
    )
    (net (code "7") (name "DAC_OUT1") (class "Default")
      (node (ref "C3") (pin "+") (pinfunction "+_+") (pintype "passive"))
      (node (ref "U6") (pin "27") (pinfunction "VOUT1_27") (pintype "output"))
    )
    (net (code "8") (name "DAC_OUT2") (class "Default")
      (node (ref "C7") (pin "+") (pinfunction "+_+") (pintype "passive"))
      (node (ref "U6") (pin "26") (pinfunction "VOUT2_26") (pintype "output"))
    )
    (net (code "9") (name "DAC_OUT3") (class "Default")
      (node (ref "C11") (pin "+") (pinfunction "+_+") (pintype "passive"))
      (node (ref "U6") (pin "22") (pinfunction "VOUT3_22") (pintype "output"))
    )
    (net (code "10") (name "DAC_OUT4") (class "Default")
      (node (ref "C15") (pin "+") (pinfunction "+_+") (pintype "passive"))
      (node (ref "U6") (pin "21") (pinfunction "VOUT4_21") (pintype "output"))
    )
    (net (code "11") (name "DAC_OUT5") (class "Default")
      (node (ref "C19") (pin "+") (pinfunction "+_+") (pintype "passive"))
      (node (ref "U6") (pin "20") (pinfunction "VOUT5_20") (pintype "output"))
    )
    (net (code "12") (name "DAC_OUT6") (class "Default")
      (node (ref "C23") (pin "+") (pinfunction "+_+") (pintype "passive"))
      (node (ref "U6") (pin "19") (pinfunction "VOUT6_19") (pintype "output"))
    )
    (net (code "13") (name "DAC_OUT7") (class "Default")
      (node (ref "C27") (pin "+") (pinfunction "+_+") (pintype "passive"))
      (node (ref "U6") (pin "16") (pinfunction "VOUT7_16") (pintype "output"))
    )
    (net (code "14") (name "DAC_OUT8") (class "Default")
      (node (ref "C31") (pin "+") (pinfunction "+_+") (pintype "passive"))
      (node (ref "U6") (pin "15") (pinfunction "VOUT8_15") (pintype "output"))
    )
    (net (code "15") (name "DAC_OUT9") (class "Default")
      (node (ref "C35") (pin "+") (pinfunction "+_+") (pintype "passive"))
      (node (ref "U7") (pin "27") (pinfunction "VOUT1_27") (pintype "output"))
    )
    (net (code "16") (name "DAC_OUT10") (class "Default")
      (node (ref "C39") (pin "+") (pinfunction "+_+") (pintype "passive"))
      (node (ref "U7") (pin "26") (pinfunction "VOUT2_26") (pintype "output"))
    )
    (net (code "17") (name "DAC_OUT11") (class "Default")
      (node (ref "C43") (pin "+") (pinfunction "+_+") (pintype "passive"))
      (node (ref "U7") (pin "22") (pinfunction "VOUT3_22") (pintype "output"))
    )
    (net (code "18") (name "DAC_OUT12") (class "Default")
      (node (ref "C47") (pin "+") (pinfunction "+_+") (pintype "passive"))
      (node (ref "U7") (pin "21") (pinfunction "VOUT4_21") (pintype "output"))
    )
    (net (code "19") (name "EXT_OUT1") (class "Default")
      (node (ref "PL1") (pin "13") (pinfunction "TT_13") (pintype "bidirectional"))
      (node (ref "R1") (pin "2") (pinfunction "2_2") (pintype "passive"))
    )
    (net (code "20") (name "EXT_OUT2") (class "Default")
      (node (ref "PL1") (pin "12") (pinfunction "TB_12") (pintype "bidirectional"))
      (node (ref "R8") (pin "2") (pinfunction "2_2") (pintype "passive"))
    )
    (net (code "21") (name "EXT_OUT3") (class "Default")
      (node (ref "PL2") (pin "13") (pinfunction "TT_13") (pintype "bidirectional"))
      (node (ref "R9") (pin "2") (pinfunction "2_2") (pintype "passive"))
    )
    (net (code "22") (name "EXT_OUT4") (class "Default")
      (node (ref "PL2") (pin "12") (pinfunction "TB_12") (pintype "bidirectional"))
      (node (ref "R16") (pin "2") (pinfunction "2_2") (pintype "passive"))
    )
    (net (code "23") (name "EXT_OUT5") (class "Default")
      (node (ref "PL3") (pin "13") (pinfunction "TT_13") (pintype "bidirectional"))
      (node (ref "R17") (pin "2") (pinfunction "2_2") (pintype "passive"))
    )
    (net (code "24") (name "EXT_OUT6") (class "Default")
      (node (ref "PL3") (pin "12") (pinfunction "TB_12") (pintype "bidirectional"))
      (node (ref "R24") (pin "2") (pinfunction "2_2") (pintype "passive"))
    )
    (net (code "25") (name "EXT_OUT7") (class "Default")
      (node (ref "PL4") (pin "13") (pinfunction "TT_13") (pintype "bidirectional"))
      (node (ref "R25") (pin "2") (pinfunction "2_2") (pintype "passive"))
    )
    (net (code "26") (name "EXT_OUT8") (class "Default")
      (node (ref "PL4") (pin "12") (pinfunction "TB_12") (pintype "bidirectional"))
      (node (ref "R32") (pin "2") (pinfunction "2_2") (pintype "passive"))
    )
    (net (code "27") (name "EXT_OUT9") (class "Default")
      (node (ref "PL5") (pin "13") (pinfunction "TT_13") (pintype "bidirectional"))
      (node (ref "R33") (pin "2") (pinfunction "2_2") (pintype "passive"))
    )
    (net (code "28") (name "EXT_OUT10") (class "Default")
      (node (ref "PL5") (pin "12") (pinfunction "TB_12") (pintype "bidirectional"))
      (node (ref "R40") (pin "2") (pinfunction "2_2") (pintype "passive"))
    )
    (net (code "29") (name "EXT_OUT11") (class "Default")
      (node (ref "PL6") (pin "13") (pinfunction "TT_13") (pintype "bidirectional"))
      (node (ref "R41") (pin "2") (pinfunction "2_2") (pintype "passive"))
    )
    (net (code "30") (name "EXT_OUT12") (class "Default")
      (node (ref "PL6") (pin "12") (pinfunction "TB_12") (pintype "bidirectional"))
      (node (ref "R48") (pin "2") (pinfunction "2_2") (pintype "passive"))
    )
    (net (code "31") (name "GND") (class "Default")
      (node (ref "C10") (pin "2") (pinfunction "P$2_2") (pintype "passive"))
      (node (ref "C100") (pin "1") (pinfunction "P$1_1") (pintype "passive"))
      (node (ref "C101") (pin "1") (pinfunction "P$1_1") (pintype "passive"))
      (node (ref "C102") (pin "2") (pinfunction "P$2_2") (pintype "passive"))
      (node (ref "C103") (pin "2") (pinfunction "P$2_2") (pintype "passive"))
      (node (ref "C12") (pin "2") (pinfunction "P$2_2") (pintype "passive"))
      (node (ref "C14") (pin "2") (pinfunction "P$2_2") (pintype "passive"))
      (node (ref "C16") (pin "1") (pinfunction "P$1_1") (pintype "passive"))
      (node (ref "C18") (pin "2") (pinfunction "P$2_2") (pintype "passive"))
      (node (ref "C2") (pin "2") (pinfunction "P$2_2") (pintype "passive"))
      (node (ref "C20") (pin "2") (pinfunction "P$2_2") (pintype "passive"))
      (node (ref "C22") (pin "2") (pinfunction "P$2_2") (pintype "passive"))
      (node (ref "C24") (pin "1") (pinfunction "P$1_1") (pintype "passive"))
      (node (ref "C26") (pin "2") (pinfunction "P$2_2") (pintype "passive"))
      (node (ref "C28") (pin "2") (pinfunction "P$2_2") (pintype "passive"))
      (node (ref "C30") (pin "2") (pinfunction "P$2_2") (pintype "passive"))
      (node (ref "C32") (pin "1") (pinfunction "P$1_1") (pintype "passive"))
      (node (ref "C34") (pin "2") (pinfunction "P$2_2") (pintype "passive"))
      (node (ref "C36") (pin "2") (pinfunction "P$2_2") (pintype "passive"))
      (node (ref "C38") (pin "2") (pinfunction "P$2_2") (pintype "passive"))
      (node (ref "C4") (pin "2") (pinfunction "P$2_2") (pintype "passive"))
      (node (ref "C40") (pin "1") (pinfunction "P$1_1") (pintype "passive"))
      (node (ref "C42") (pin "2") (pinfunction "P$2_2") (pintype "passive"))
      (node (ref "C44") (pin "2") (pinfunction "P$2_2") (pintype "passive"))
      (node (ref "C46") (pin "2") (pinfunction "P$2_2") (pintype "passive"))
      (node (ref "C48") (pin "1") (pinfunction "P$1_1") (pintype "passive"))
      (node (ref "C49") (pin "1") (pinfunction "P$1_1") (pintype "passive"))
      (node (ref "C50") (pin "1") (pinfunction "P$1_1") (pintype "passive"))
      (node (ref "C51") (pin "1") (pinfunction "P$1_1") (pintype "passive"))
      (node (ref "C52") (pin "1") (pinfunction "P$1_1") (pintype "passive"))
      (node (ref "C53") (pin "1") (pinfunction "P$1_1") (pintype "passive"))
      (node (ref "C54") (pin "1") (pinfunction "P$1_1") (pintype "passive"))
      (node (ref "C55") (pin "1") (pinfunction "P$1_1") (pintype "passive"))
      (node (ref "C56") (pin "1") (pinfunction "P$1_1") (pintype "passive"))
      (node (ref "C57") (pin "1") (pinfunction "P$1_1") (pintype "passive"))
      (node (ref "C58") (pin "1") (pinfunction "P$1_1") (pintype "passive"))
      (node (ref "C59") (pin "1") (pinfunction "P$1_1") (pintype "passive"))
      (node (ref "C6") (pin "2") (pinfunction "P$2_2") (pintype "passive"))
      (node (ref "C60") (pin "1") (pinfunction "P$1_1") (pintype "passive"))
      (node (ref "C61") (pin "1") (pinfunction "P$1_1") (pintype "passive"))
      (node (ref "C62") (pin "1") (pinfunction "P$1_1") (pintype "passive"))
      (node (ref "C63") (pin "1") (pinfunction "P$1_1") (pintype "passive"))
      (node (ref "C64") (pin "1") (pinfunction "P$1_1") (pintype "passive"))
      (node (ref "C65") (pin "1") (pinfunction "P$1_1") (pintype "passive"))
      (node (ref "C66") (pin "1") (pinfunction "P$1_1") (pintype "passive"))
      (node (ref "C67") (pin "1") (pinfunction "P$1_1") (pintype "passive"))
      (node (ref "C68") (pin "1") (pinfunction "P$1_1") (pintype "passive"))
      (node (ref "C69") (pin "1") (pinfunction "P$1_1") (pintype "passive"))
      (node (ref "C70") (pin "1") (pinfunction "P$1_1") (pintype "passive"))
      (node (ref "C71") (pin "2") (pinfunction "P$2_2") (pintype "passive"))
      (node (ref "C72") (pin "1") (pinfunction "P$1_1") (pintype "passive"))
      (node (ref "C73") (pin "2") (pinfunction "P$2_2") (pintype "passive"))
      (node (ref "C74") (pin "1") (pinfunction "P$1_1") (pintype "passive"))
      (node (ref "C75") (pin "1") (pinfunction "P$1_1") (pintype "passive"))
      (node (ref "C76") (pin "1") (pinfunction "P$1_1") (pintype "passive"))
      (node (ref "C77") (pin "-") (pinfunction "-_-") (pintype "passive"))
      (node (ref "C78") (pin "1") (pinfunction "P$1_1") (pintype "passive"))
      (node (ref "C79") (pin "1") (pinfunction "P$1_1") (pintype "passive"))
      (node (ref "C8") (pin "1") (pinfunction "P$1_1") (pintype "passive"))
      (node (ref "C80") (pin "1") (pinfunction "P$1_1") (pintype "passive"))
      (node (ref "C81") (pin "-") (pinfunction "-_-") (pintype "passive"))
      (node (ref "C82") (pin "-") (pinfunction "-_-") (pintype "passive"))
      (node (ref "C83") (pin "-") (pinfunction "-_-") (pintype "passive"))
      (node (ref "C84") (pin "1") (pinfunction "P$1_1") (pintype "passive"))
      (node (ref "C85") (pin "1") (pinfunction "P$1_1") (pintype "passive"))
      (node (ref "C86") (pin "1") (pinfunction "P$1_1") (pintype "passive"))
      (node (ref "C87") (pin "-") (pinfunction "-_-") (pintype "passive"))
      (node (ref "C88") (pin "-") (pinfunction "-_-") (pintype "passive"))
      (node (ref "C89") (pin "-") (pinfunction "-_-") (pintype "passive"))
      (node (ref "C90") (pin "1") (pinfunction "P$1_1") (pintype "passive"))
      (node (ref "C91") (pin "1") (pinfunction "P$1_1") (pintype "passive"))
      (node (ref "C92") (pin "-") (pinfunction "-_-") (pintype "passive"))
      (node (ref "C93") (pin "-") (pinfunction "-_-") (pintype "passive"))
      (node (ref "C94") (pin "1") (pinfunction "P$1_1") (pintype "passive"))
      (node (ref "C95") (pin "2") (pinfunction "P$2_2") (pintype "passive"))
      (node (ref "C96") (pin "2") (pinfunction "P$2_2") (pintype "passive"))
      (node (ref "C97") (pin "2") (pinfunction "P$2_2") (pintype "passive"))
      (node (ref "C98") (pin "2") (pinfunction "P$2_2") (pintype "passive"))
      (node (ref "C99") (pin "1") (pinfunction "P$1_1") (pintype "passive"))
      (node (ref "IC1") (pin "3") (pinfunction "+IN_3") (pintype "input"))
      (node (ref "IC1") (pin "5") (pinfunction "+IN_5") (pintype "input"))
      (node (ref "IC2") (pin "3") (pinfunction "+IN_3") (pintype "input"))
      (node (ref "IC2") (pin "5") (pinfunction "+IN_5") (pintype "input"))
      (node (ref "IC3") (pin "3") (pinfunction "+IN_3") (pintype "input"))
      (node (ref "IC3") (pin "5") (pinfunction "+IN_5") (pintype "input"))
      (node (ref "IC4") (pin "3") (pinfunction "+IN_3") (pintype "input"))
      (node (ref "IC4") (pin "5") (pinfunction "+IN_5") (pintype "input"))
      (node (ref "IC5") (pin "3") (pinfunction "+IN_3") (pintype "input"))
      (node (ref "IC5") (pin "5") (pinfunction "+IN_5") (pintype "input"))
      (node (ref "IC6") (pin "3") (pinfunction "+IN_3") (pintype "input"))
      (node (ref "IC6") (pin "5") (pinfunction "+IN_5") (pintype "input"))
      (node (ref "IC7") (pin "7") (pinfunction "GND_7") (pintype "power_in"))
      (node (ref "JP6") (pin "6") (pinfunction "2_6") (pintype "passive"))
      (node (ref "LED1") (pin "C1") (pinfunction "K_1_C1") (pintype "bidirectional"))
      (node (ref "LED1") (pin "C2") (pinfunction "K_2_C2") (pintype "bidirectional"))
      (node (ref "LED1") (pin "C3") (pinfunction "K_3_C3") (pintype "bidirectional"))
      (node (ref "LED2") (pin "C") (pinfunction "C_C") (pintype "passive"))
      (node (ref "OSC1") (pin "2") (pinfunction "GND_2") (pintype "power_in"))
      (node (ref "PL1") (pin "10") (pinfunction "RB_10") (pintype "bidirectional"))
      (node (ref "PL1") (pin "11") (pinfunction "RT_11") (pintype "bidirectional"))
      (node (ref "PL1") (pin "8") (pinfunction "SB_8") (pintype "bidirectional"))
      (node (ref "PL1") (pin "9") (pinfunction "ST_9") (pintype "bidirectional"))
      (node (ref "PL2") (pin "10") (pinfunction "RB_10") (pintype "bidirectional"))
      (node (ref "PL2") (pin "11") (pinfunction "RT_11") (pintype "bidirectional"))
      (node (ref "PL2") (pin "8") (pinfunction "SB_8") (pintype "bidirectional"))
      (node (ref "PL2") (pin "9") (pinfunction "ST_9") (pintype "bidirectional"))
      (node (ref "PL3") (pin "10") (pinfunction "RB_10") (pintype "bidirectional"))
      (node (ref "PL3") (pin "11") (pinfunction "RT_11") (pintype "bidirectional"))
      (node (ref "PL3") (pin "8") (pinfunction "SB_8") (pintype "bidirectional"))
      (node (ref "PL3") (pin "9") (pinfunction "ST_9") (pintype "bidirectional"))
      (node (ref "PL4") (pin "10") (pinfunction "RB_10") (pintype "bidirectional"))
      (node (ref "PL4") (pin "11") (pinfunction "RT_11") (pintype "bidirectional"))
      (node (ref "PL4") (pin "8") (pinfunction "SB_8") (pintype "bidirectional"))
      (node (ref "PL4") (pin "9") (pinfunction "ST_9") (pintype "bidirectional"))
      (node (ref "PL5") (pin "10") (pinfunction "RB_10") (pintype "bidirectional"))
      (node (ref "PL5") (pin "11") (pinfunction "RT_11") (pintype "bidirectional"))
      (node (ref "PL5") (pin "8") (pinfunction "SB_8") (pintype "bidirectional"))
      (node (ref "PL5") (pin "9") (pinfunction "ST_9") (pintype "bidirectional"))
      (node (ref "PL6") (pin "10") (pinfunction "RB_10") (pintype "bidirectional"))
      (node (ref "PL6") (pin "11") (pinfunction "RT_11") (pintype "bidirectional"))
      (node (ref "PL6") (pin "8") (pinfunction "SB_8") (pintype "bidirectional"))
      (node (ref "PL6") (pin "9") (pinfunction "ST_9") (pintype "bidirectional"))
      (node (ref "R102") (pin "2") (pinfunction "2_2") (pintype "passive"))
      (node (ref "R103") (pin "2") (pinfunction "2_2") (pintype "passive"))
      (node (ref "R104") (pin "2") (pinfunction "2_2") (pintype "passive"))
      (node (ref "R105") (pin "2") (pinfunction "2_2") (pintype "passive"))
      (node (ref "R52") (pin "2") (pinfunction "2_2") (pintype "passive"))
      (node (ref "R54") (pin "2") (pinfunction "2_2") (pintype "passive"))
      (node (ref "R57") (pin "1") (pinfunction "1_1") (pintype "passive"))
      (node (ref "R58") (pin "1") (pinfunction "1_1") (pintype "passive"))
      (node (ref "R65") (pin "1") (pinfunction "1_1") (pintype "passive"))
      (node (ref "R68") (pin "1") (pinfunction "1_1") (pintype "passive"))
      (node (ref "R69") (pin "1") (pinfunction "1_1") (pintype "passive"))
      (node (ref "R72") (pin "1") (pinfunction "1_1") (pintype "passive"))
      (node (ref "R73") (pin "2") (pinfunction "2_2") (pintype "passive"))
      (node (ref "R74") (pin "2") (pinfunction "2_2") (pintype "passive"))
      (node (ref "R77") (pin "1") (pinfunction "1_1") (pintype "passive"))
      (node (ref "R83") (pin "1") (pinfunction "1_1") (pintype "passive"))
      (node (ref "R84") (pin "1") (pinfunction "1_1") (pintype "passive"))
      (node (ref "R85") (pin "2") (pinfunction "2_2") (pintype "passive"))
      (node (ref "R86") (pin "2") (pinfunction "2_2") (pintype "passive"))
      (node (ref "R95") (pin "1") (pinfunction "1_1") (pintype "passive"))
      (node (ref "R96") (pin "2") (pinfunction "2_2") (pintype "passive"))
      (node (ref "TC1") (pin "3") (pinfunction "3_3") (pintype "passive"))
      (node (ref "TC1") (pin "5") (pinfunction "5_5") (pintype "passive"))
      (node (ref "TC1") (pin "9") (pinfunction "9_9") (pintype "passive"))
      (node (ref "TP16") (pin "TP") (pinfunction "TP_TP") (pintype "input"))
      (node (ref "TP17") (pin "TP") (pinfunction "TP_TP") (pintype "input"))
      (node (ref "TP18") (pin "TP") (pinfunction "TP_TP") (pintype "input"))
      (node (ref "TP2") (pin "TP") (pinfunction "TP_TP") (pintype "input"))
      (node (ref "TP5") (pin "TP") (pinfunction "TP_TP") (pintype "input"))
      (node (ref "U$1") (pin "LED-") (pinfunction "LED-_LED-") (pintype "passive"))
      (node (ref "U$1") (pin "P$3") (pinfunction "OUT1_NO_P$3") (pintype "passive"))
      (node (ref "U$1") (pin "P$6") (pinfunction "OUT2_NO_P$6") (pintype "passive"))
      (node (ref "U1") (pin "1") (pinfunction "ADJ_1") (pintype "input"))
      (node (ref "U2") (pin "2") (pinfunction "-VIN_2") (pintype "input"))
      (node (ref "U3") (pin "107") (pinfunction "VSS_8_107") (pintype "power_in"))
      (node (ref "U3") (pin "120") (pinfunction "VSS_9_120") (pintype "power_in"))
      (node (ref "U3") (pin "130") (pinfunction "VSS_130") (pintype "power_in"))
      (node (ref "U3") (pin "16") (pinfunction "VSS_2_16") (pintype "power_in"))
      (node (ref "U3") (pin "31") (pinfunction "VSSA_31") (pintype "power_in"))
      (node (ref "U3") (pin "38") (pinfunction "VSS_3_38") (pintype "power_in"))
      (node (ref "U3") (pin "51") (pinfunction "VSS_4_51") (pintype "power_in"))
      (node (ref "U3") (pin "61") (pinfunction "VSS_5_61") (pintype "power_in"))
      (node (ref "U3") (pin "85") (pinfunction "VSS_6_85") (pintype "power_in"))
      (node (ref "U3") (pin "94") (pinfunction "VSS_7_94") (pintype "power_in"))
      (node (ref "U4") (pin "2") (pinfunction "GND_2") (pintype "power_in"))
      (node (ref "U5") (pin "2") (pinfunction "GND_2") (pintype "power_in"))
      (node (ref "U6") (pin "10") (pinfunction "DGND_10") (pintype "power_in"))
      (node (ref "U6") (pin "14") (pinfunction "MSEL_14") (pintype "input"))
      (node (ref "U6") (pin "18") (pinfunction "AGND1_18") (pintype "power_in"))
      (node (ref "U6") (pin "24") (pinfunction "AGND2_24") (pintype "power_in"))
      (node (ref "U6") (pin "29") (pinfunction "EPAD_29") (pintype "passive"))
      (node (ref "U7") (pin "10") (pinfunction "DGND_10") (pintype "power_in"))
      (node (ref "U7") (pin "14") (pinfunction "MSEL_14") (pintype "input"))
      (node (ref "U7") (pin "18") (pinfunction "AGND1_18") (pintype "power_in"))
      (node (ref "U7") (pin "24") (pinfunction "AGND2_24") (pintype "power_in"))
      (node (ref "U7") (pin "29") (pinfunction "EPAD_29") (pintype "passive"))
      (node (ref "USB_FS") (pin "4") (pinfunction "4_4") (pintype "bidirectional"))
      (node (ref "USB_HS") (pin "P$4") (pinfunction "4_P$4") (pintype "passive"))
    )
    (net (code "32") (name "I2C_SCL") (class "Default")
      (node (ref "R70") (pin "1") (pinfunction "1_1") (pintype "passive"))
      (node (ref "R81") (pin "1") (pinfunction "1_1") (pintype "passive"))
      (node (ref "R93") (pin "1") (pinfunction "1_1") (pintype "passive"))
      (node (ref "U3") (pin "139") (pinfunction "PB8_139") (pintype "bidirectional"))
    )
    (net (code "33") (name "I2C_SDA") (class "Default")
      (node (ref "R71") (pin "1") (pinfunction "1_1") (pintype "passive"))
      (node (ref "R82") (pin "1") (pinfunction "1_1") (pintype "passive"))
      (node (ref "R92") (pin "1") (pinfunction "1_1") (pintype "passive"))
      (node (ref "U3") (pin "137") (pinfunction "PB7_137") (pintype "bidirectional"))
    )
    (net (code "34") (name "I2S_CKIN") (class "Default")
      (node (ref "R56") (pin "2") (pinfunction "2_2") (pintype "passive"))
      (node (ref "U3") (pin "99") (pinfunction "PC9_99") (pintype "bidirectional"))
    )
    (net (code "35") (name "LED1") (class "Default")
      (node (ref "R98") (pin "2") (pinfunction "2_2") (pintype "passive"))
      (node (ref "U3") (pin "111") (pinfunction "PC10_111") (pintype "bidirectional"))
    )
    (net (code "36") (name "LED2") (class "Default")
      (node (ref "R99") (pin "2") (pinfunction "2_2") (pintype "passive"))
      (node (ref "U3") (pin "112") (pinfunction "PC11_112") (pintype "bidirectional"))
    )
    (net (code "37") (name "LED3") (class "Default")
      (node (ref "R100") (pin "2") (pinfunction "2_2") (pintype "passive"))
      (node (ref "U3") (pin "113") (pinfunction "PC12_113") (pintype "bidirectional"))
    )
    (net (code "38") (name "LED4") (class "Default")
      (node (ref "R101") (pin "1") (pinfunction "1_1") (pintype "passive"))
      (node (ref "U3") (pin "47") (pinfunction "PB1_47") (pintype "bidirectional"))
    )
    (net (code "39") (name "NRST") (class "Default")
      (node (ref "C71") (pin "1") (pinfunction "P$1_1") (pintype "passive"))
      (node (ref "R53") (pin "1") (pinfunction "1_1") (pintype "passive"))
      (node (ref "TC1") (pin "10") (pinfunction "10_10") (pintype "passive"))
      (node (ref "U3") (pin "25") (pinfunction "NRST_25") (pintype "bidirectional"))
    )
    (net (code "40") (name "Net-(C1-P$1)") (class "Default")
      (node (ref "C1") (pin "1") (pinfunction "P$1_1") (pintype "passive"))
      (node (ref "IC1") (pin "1") (pinfunction "OUT_1") (pintype "output"))
      (node (ref "R1") (pin "1") (pinfunction "1_1") (pintype "passive"))
      (node (ref "R3") (pin "2") (pinfunction "2_2") (pintype "passive"))
    )
    (net (code "41") (name "Net-(C1-P$2)") (class "Default")
      (node (ref "C1") (pin "2") (pinfunction "P$2_2") (pintype "passive"))
      (node (ref "IC1") (pin "2") (pinfunction "-IN_2") (pintype "input"))
      (node (ref "R2") (pin "2") (pinfunction "2_2") (pintype "passive"))
    )
    (net (code "42") (name "Net-(C2-P$1)") (class "Default")
      (node (ref "C2") (pin "1") (pinfunction "P$1_1") (pintype "passive"))
      (node (ref "R2") (pin "1") (pinfunction "1_1") (pintype "passive"))
      (node (ref "R3") (pin "1") (pinfunction "1_1") (pintype "passive"))
      (node (ref "R4") (pin "1") (pinfunction "1_1") (pintype "passive"))
    )
    (net (code "43") (name "Net-(C3-Pad-)") (class "Default")
      (node (ref "C3") (pin "-") (pinfunction "-_-") (pintype "passive"))
      (node (ref "R4") (pin "2") (pinfunction "2_2") (pintype "passive"))
    )
    (net (code "44") (name "Net-(C5-P$1)") (class "Default")
      (node (ref "C5") (pin "1") (pinfunction "P$1_1") (pintype "passive"))
      (node (ref "IC1") (pin "7") (pinfunction "OUT_7") (pintype "output"))
      (node (ref "R6") (pin "2") (pinfunction "2_2") (pintype "passive"))
      (node (ref "R8") (pin "1") (pinfunction "1_1") (pintype "passive"))
    )
    (net (code "45") (name "Net-(C5-P$2)") (class "Default")
      (node (ref "C5") (pin "2") (pinfunction "P$2_2") (pintype "passive"))
      (node (ref "IC1") (pin "6") (pinfunction "-IN_6") (pintype "input"))
      (node (ref "R5") (pin "2") (pinfunction "2_2") (pintype "passive"))
    )
    (net (code "46") (name "Net-(C6-P$1)") (class "Default")
      (node (ref "C6") (pin "1") (pinfunction "P$1_1") (pintype "passive"))
      (node (ref "R5") (pin "1") (pinfunction "1_1") (pintype "passive"))
      (node (ref "R6") (pin "1") (pinfunction "1_1") (pintype "passive"))
      (node (ref "R7") (pin "1") (pinfunction "1_1") (pintype "passive"))
    )
    (net (code "47") (name "Net-(C7-Pad-)") (class "Default")
      (node (ref "C7") (pin "-") (pinfunction "-_-") (pintype "passive"))
      (node (ref "R7") (pin "2") (pinfunction "2_2") (pintype "passive"))
    )
    (net (code "48") (name "Net-(C9-P$1)") (class "Default")
      (node (ref "C9") (pin "1") (pinfunction "P$1_1") (pintype "passive"))
      (node (ref "IC2") (pin "1") (pinfunction "OUT_1") (pintype "output"))
      (node (ref "R11") (pin "2") (pinfunction "2_2") (pintype "passive"))
      (node (ref "R9") (pin "1") (pinfunction "1_1") (pintype "passive"))
    )
    (net (code "49") (name "Net-(C9-P$2)") (class "Default")
      (node (ref "C9") (pin "2") (pinfunction "P$2_2") (pintype "passive"))
      (node (ref "IC2") (pin "2") (pinfunction "-IN_2") (pintype "input"))
      (node (ref "R10") (pin "2") (pinfunction "2_2") (pintype "passive"))
    )
    (net (code "50") (name "Net-(C10-P$1)") (class "Default")
      (node (ref "C10") (pin "1") (pinfunction "P$1_1") (pintype "passive"))
      (node (ref "R10") (pin "1") (pinfunction "1_1") (pintype "passive"))
      (node (ref "R11") (pin "1") (pinfunction "1_1") (pintype "passive"))
      (node (ref "R12") (pin "1") (pinfunction "1_1") (pintype "passive"))
    )
    (net (code "51") (name "Net-(C11-Pad-)") (class "Default")
      (node (ref "C11") (pin "-") (pinfunction "-_-") (pintype "passive"))
      (node (ref "R12") (pin "2") (pinfunction "2_2") (pintype "passive"))
    )
    (net (code "52") (name "Net-(C13-P$1)") (class "Default")
      (node (ref "C13") (pin "1") (pinfunction "P$1_1") (pintype "passive"))
      (node (ref "IC2") (pin "7") (pinfunction "OUT_7") (pintype "output"))
      (node (ref "R14") (pin "2") (pinfunction "2_2") (pintype "passive"))
      (node (ref "R16") (pin "1") (pinfunction "1_1") (pintype "passive"))
    )
    (net (code "53") (name "Net-(C13-P$2)") (class "Default")
      (node (ref "C13") (pin "2") (pinfunction "P$2_2") (pintype "passive"))
      (node (ref "IC2") (pin "6") (pinfunction "-IN_6") (pintype "input"))
      (node (ref "R13") (pin "2") (pinfunction "2_2") (pintype "passive"))
    )
    (net (code "54") (name "Net-(C14-P$1)") (class "Default")
      (node (ref "C14") (pin "1") (pinfunction "P$1_1") (pintype "passive"))
      (node (ref "R13") (pin "1") (pinfunction "1_1") (pintype "passive"))
      (node (ref "R14") (pin "1") (pinfunction "1_1") (pintype "passive"))
      (node (ref "R15") (pin "1") (pinfunction "1_1") (pintype "passive"))
    )
    (net (code "55") (name "Net-(C15-Pad-)") (class "Default")
      (node (ref "C15") (pin "-") (pinfunction "-_-") (pintype "passive"))
      (node (ref "R15") (pin "2") (pinfunction "2_2") (pintype "passive"))
    )
    (net (code "56") (name "Net-(C17-P$1)") (class "Default")
      (node (ref "C17") (pin "1") (pinfunction "P$1_1") (pintype "passive"))
      (node (ref "IC3") (pin "1") (pinfunction "OUT_1") (pintype "output"))
      (node (ref "R17") (pin "1") (pinfunction "1_1") (pintype "passive"))
      (node (ref "R19") (pin "2") (pinfunction "2_2") (pintype "passive"))
    )
    (net (code "57") (name "Net-(C17-P$2)") (class "Default")
      (node (ref "C17") (pin "2") (pinfunction "P$2_2") (pintype "passive"))
      (node (ref "IC3") (pin "2") (pinfunction "-IN_2") (pintype "input"))
      (node (ref "R18") (pin "2") (pinfunction "2_2") (pintype "passive"))
    )
    (net (code "58") (name "Net-(C18-P$1)") (class "Default")
      (node (ref "C18") (pin "1") (pinfunction "P$1_1") (pintype "passive"))
      (node (ref "R18") (pin "1") (pinfunction "1_1") (pintype "passive"))
      (node (ref "R19") (pin "1") (pinfunction "1_1") (pintype "passive"))
      (node (ref "R20") (pin "1") (pinfunction "1_1") (pintype "passive"))
    )
    (net (code "59") (name "Net-(C19-Pad-)") (class "Default")
      (node (ref "C19") (pin "-") (pinfunction "-_-") (pintype "passive"))
      (node (ref "R20") (pin "2") (pinfunction "2_2") (pintype "passive"))
    )
    (net (code "60") (name "Net-(C21-P$1)") (class "Default")
      (node (ref "C21") (pin "1") (pinfunction "P$1_1") (pintype "passive"))
      (node (ref "IC3") (pin "7") (pinfunction "OUT_7") (pintype "output"))
      (node (ref "R22") (pin "2") (pinfunction "2_2") (pintype "passive"))
      (node (ref "R24") (pin "1") (pinfunction "1_1") (pintype "passive"))
    )
    (net (code "61") (name "Net-(C21-P$2)") (class "Default")
      (node (ref "C21") (pin "2") (pinfunction "P$2_2") (pintype "passive"))
      (node (ref "IC3") (pin "6") (pinfunction "-IN_6") (pintype "input"))
      (node (ref "R21") (pin "2") (pinfunction "2_2") (pintype "passive"))
    )
    (net (code "62") (name "Net-(C22-P$1)") (class "Default")
      (node (ref "C22") (pin "1") (pinfunction "P$1_1") (pintype "passive"))
      (node (ref "R21") (pin "1") (pinfunction "1_1") (pintype "passive"))
      (node (ref "R22") (pin "1") (pinfunction "1_1") (pintype "passive"))
      (node (ref "R23") (pin "1") (pinfunction "1_1") (pintype "passive"))
    )
    (net (code "63") (name "Net-(C23-Pad-)") (class "Default")
      (node (ref "C23") (pin "-") (pinfunction "-_-") (pintype "passive"))
      (node (ref "R23") (pin "2") (pinfunction "2_2") (pintype "passive"))
    )
    (net (code "64") (name "Net-(C25-P$1)") (class "Default")
      (node (ref "C25") (pin "1") (pinfunction "P$1_1") (pintype "passive"))
      (node (ref "IC4") (pin "1") (pinfunction "OUT_1") (pintype "output"))
      (node (ref "R25") (pin "1") (pinfunction "1_1") (pintype "passive"))
      (node (ref "R27") (pin "2") (pinfunction "2_2") (pintype "passive"))
    )
    (net (code "65") (name "Net-(C25-P$2)") (class "Default")
      (node (ref "C25") (pin "2") (pinfunction "P$2_2") (pintype "passive"))
      (node (ref "IC4") (pin "2") (pinfunction "-IN_2") (pintype "input"))
      (node (ref "R26") (pin "2") (pinfunction "2_2") (pintype "passive"))
    )
    (net (code "66") (name "Net-(C26-P$1)") (class "Default")
      (node (ref "C26") (pin "1") (pinfunction "P$1_1") (pintype "passive"))
      (node (ref "R26") (pin "1") (pinfunction "1_1") (pintype "passive"))
      (node (ref "R27") (pin "1") (pinfunction "1_1") (pintype "passive"))
      (node (ref "R28") (pin "1") (pinfunction "1_1") (pintype "passive"))
    )
    (net (code "67") (name "Net-(C27-Pad-)") (class "Default")
      (node (ref "C27") (pin "-") (pinfunction "-_-") (pintype "passive"))
      (node (ref "R28") (pin "2") (pinfunction "2_2") (pintype "passive"))
    )
    (net (code "68") (name "Net-(C29-P$1)") (class "Default")
      (node (ref "C29") (pin "1") (pinfunction "P$1_1") (pintype "passive"))
      (node (ref "IC4") (pin "7") (pinfunction "OUT_7") (pintype "output"))
      (node (ref "R30") (pin "2") (pinfunction "2_2") (pintype "passive"))
      (node (ref "R32") (pin "1") (pinfunction "1_1") (pintype "passive"))
    )
    (net (code "69") (name "Net-(C29-P$2)") (class "Default")
      (node (ref "C29") (pin "2") (pinfunction "P$2_2") (pintype "passive"))
      (node (ref "IC4") (pin "6") (pinfunction "-IN_6") (pintype "input"))
      (node (ref "R29") (pin "2") (pinfunction "2_2") (pintype "passive"))
    )
    (net (code "70") (name "Net-(C30-P$1)") (class "Default")
      (node (ref "C30") (pin "1") (pinfunction "P$1_1") (pintype "passive"))
      (node (ref "R29") (pin "1") (pinfunction "1_1") (pintype "passive"))
      (node (ref "R30") (pin "1") (pinfunction "1_1") (pintype "passive"))
      (node (ref "R31") (pin "1") (pinfunction "1_1") (pintype "passive"))
    )
    (net (code "71") (name "Net-(C31-Pad-)") (class "Default")
      (node (ref "C31") (pin "-") (pinfunction "-_-") (pintype "passive"))
      (node (ref "R31") (pin "2") (pinfunction "2_2") (pintype "passive"))
    )
    (net (code "72") (name "Net-(C33-P$1)") (class "Default")
      (node (ref "C33") (pin "1") (pinfunction "P$1_1") (pintype "passive"))
      (node (ref "IC5") (pin "1") (pinfunction "OUT_1") (pintype "output"))
      (node (ref "R33") (pin "1") (pinfunction "1_1") (pintype "passive"))
      (node (ref "R35") (pin "2") (pinfunction "2_2") (pintype "passive"))
    )
    (net (code "73") (name "Net-(C33-P$2)") (class "Default")
      (node (ref "C33") (pin "2") (pinfunction "P$2_2") (pintype "passive"))
      (node (ref "IC5") (pin "2") (pinfunction "-IN_2") (pintype "input"))
      (node (ref "R34") (pin "2") (pinfunction "2_2") (pintype "passive"))
    )
    (net (code "74") (name "Net-(C34-P$1)") (class "Default")
      (node (ref "C34") (pin "1") (pinfunction "P$1_1") (pintype "passive"))
      (node (ref "R34") (pin "1") (pinfunction "1_1") (pintype "passive"))
      (node (ref "R35") (pin "1") (pinfunction "1_1") (pintype "passive"))
      (node (ref "R36") (pin "1") (pinfunction "1_1") (pintype "passive"))
    )
    (net (code "75") (name "Net-(C35-Pad-)") (class "Default")
      (node (ref "C35") (pin "-") (pinfunction "-_-") (pintype "passive"))
      (node (ref "R36") (pin "2") (pinfunction "2_2") (pintype "passive"))
    )
    (net (code "76") (name "Net-(C37-P$1)") (class "Default")
      (node (ref "C37") (pin "1") (pinfunction "P$1_1") (pintype "passive"))
      (node (ref "IC5") (pin "7") (pinfunction "OUT_7") (pintype "output"))
      (node (ref "R38") (pin "2") (pinfunction "2_2") (pintype "passive"))
      (node (ref "R40") (pin "1") (pinfunction "1_1") (pintype "passive"))
    )
    (net (code "77") (name "Net-(C37-P$2)") (class "Default")
      (node (ref "C37") (pin "2") (pinfunction "P$2_2") (pintype "passive"))
      (node (ref "IC5") (pin "6") (pinfunction "-IN_6") (pintype "input"))
      (node (ref "R37") (pin "2") (pinfunction "2_2") (pintype "passive"))
    )
    (net (code "78") (name "Net-(C38-P$1)") (class "Default")
      (node (ref "C38") (pin "1") (pinfunction "P$1_1") (pintype "passive"))
      (node (ref "R37") (pin "1") (pinfunction "1_1") (pintype "passive"))
      (node (ref "R38") (pin "1") (pinfunction "1_1") (pintype "passive"))
      (node (ref "R39") (pin "1") (pinfunction "1_1") (pintype "passive"))
    )
    (net (code "79") (name "Net-(C39-Pad-)") (class "Default")
      (node (ref "C39") (pin "-") (pinfunction "-_-") (pintype "passive"))
      (node (ref "R39") (pin "2") (pinfunction "2_2") (pintype "passive"))
    )
    (net (code "80") (name "Net-(C41-P$1)") (class "Default")
      (node (ref "C41") (pin "1") (pinfunction "P$1_1") (pintype "passive"))
      (node (ref "IC6") (pin "1") (pinfunction "OUT_1") (pintype "output"))
      (node (ref "R41") (pin "1") (pinfunction "1_1") (pintype "passive"))
      (node (ref "R43") (pin "2") (pinfunction "2_2") (pintype "passive"))
    )
    (net (code "81") (name "Net-(C41-P$2)") (class "Default")
      (node (ref "C41") (pin "2") (pinfunction "P$2_2") (pintype "passive"))
      (node (ref "IC6") (pin "2") (pinfunction "-IN_2") (pintype "input"))
      (node (ref "R42") (pin "2") (pinfunction "2_2") (pintype "passive"))
    )
    (net (code "82") (name "Net-(C42-P$1)") (class "Default")
      (node (ref "C42") (pin "1") (pinfunction "P$1_1") (pintype "passive"))
      (node (ref "R42") (pin "1") (pinfunction "1_1") (pintype "passive"))
      (node (ref "R43") (pin "1") (pinfunction "1_1") (pintype "passive"))
      (node (ref "R44") (pin "1") (pinfunction "1_1") (pintype "passive"))
    )
    (net (code "83") (name "Net-(C43-Pad-)") (class "Default")
      (node (ref "C43") (pin "-") (pinfunction "-_-") (pintype "passive"))
      (node (ref "R44") (pin "2") (pinfunction "2_2") (pintype "passive"))
    )
    (net (code "84") (name "Net-(C45-P$1)") (class "Default")
      (node (ref "C45") (pin "1") (pinfunction "P$1_1") (pintype "passive"))
      (node (ref "IC6") (pin "7") (pinfunction "OUT_7") (pintype "output"))
      (node (ref "R46") (pin "2") (pinfunction "2_2") (pintype "passive"))
      (node (ref "R48") (pin "1") (pinfunction "1_1") (pintype "passive"))
    )
    (net (code "85") (name "Net-(C45-P$2)") (class "Default")
      (node (ref "C45") (pin "2") (pinfunction "P$2_2") (pintype "passive"))
      (node (ref "IC6") (pin "6") (pinfunction "-IN_6") (pintype "input"))
      (node (ref "R45") (pin "2") (pinfunction "2_2") (pintype "passive"))
    )
    (net (code "86") (name "Net-(C46-P$1)") (class "Default")
      (node (ref "C46") (pin "1") (pinfunction "P$1_1") (pintype "passive"))
      (node (ref "R45") (pin "1") (pinfunction "1_1") (pintype "passive"))
      (node (ref "R46") (pin "1") (pinfunction "1_1") (pintype "passive"))
      (node (ref "R47") (pin "1") (pinfunction "1_1") (pintype "passive"))
    )
    (net (code "87") (name "Net-(C47-Pad-)") (class "Default")
      (node (ref "C47") (pin "-") (pinfunction "-_-") (pintype "passive"))
      (node (ref "R47") (pin "2") (pinfunction "2_2") (pintype "passive"))
    )
    (net (code "88") (name "Net-(C50-P$2)") (class "Default")
      (node (ref "C50") (pin "2") (pinfunction "P$2_2") (pintype "passive"))
      (node (ref "L1") (pin "1") (pinfunction "1_1") (pintype "passive"))
      (node (ref "R49") (pin "2") (pinfunction "2_2") (pintype "passive"))
      (node (ref "TP1") (pin "TP") (pinfunction "TP_TP") (pintype "input"))
      (node (ref "U1") (pin "3") (pinfunction "OUT_3") (pintype "passive"))
    )
    (net (code "89") (name "Net-(C51-P$2)") (class "Default")
      (node (ref "C51") (pin "2") (pinfunction "P$2_2") (pintype "passive"))
      (node (ref "JP6") (pin "1") (pinfunction "1_1") (pintype "passive"))
      (node (ref "L7") (pin "1") (pinfunction "1_1") (pintype "passive"))
    )
    (net (code "90") (name "Net-(C55-P$2)") (class "Default")
      (node (ref "C55") (pin "2") (pinfunction "P$2_2") (pintype "passive"))
      (node (ref "U3") (pin "106") (pinfunction "VCAP_2_106") (pintype "power_in"))
    )
    (net (code "91") (name "Net-(C56-P$2)") (class "Default")
      (node (ref "C56") (pin "2") (pinfunction "P$2_2") (pintype "passive"))
      (node (ref "U3") (pin "71") (pinfunction "VCAP_1_71") (pintype "power_in"))
    )
    (net (code "92") (name "Net-(C72-P$2)") (class "Default")
      (node (ref "C72") (pin "2") (pinfunction "P$2_2") (pintype "passive"))
      (node (ref "U3") (pin "76") (pinfunction "VDD12-OTGHS_76") (pintype "power_in"))
    )
    (net (code "93") (name "Net-(C78-P$2)") (class "Default")
      (node (ref "C78") (pin "2") (pinfunction "P$2_2") (pintype "passive"))
      (node (ref "R57") (pin "2") (pinfunction "2_2") (pintype "passive"))
      (node (ref "USB_FS") (pin "P$1") (pinfunction "S1_P$1") (pintype "passive"))
      (node (ref "USB_FS") (pin "P$2") (pinfunction "S2_P$2") (pintype "passive"))
    )
    (net (code "94") (name "Net-(C79-P$2)") (class "Default")
      (node (ref "C79") (pin "2") (pinfunction "P$2_2") (pintype "passive"))
      (node (ref "R58") (pin "2") (pinfunction "2_2") (pintype "passive"))
      (node (ref "USB_HS") (pin "M1") (pinfunction "S1_M1") (pintype "passive"))
      (node (ref "USB_HS") (pin "M2") (pinfunction "S2_M2") (pintype "passive"))
      (node (ref "USB_HS") (pin "M3") (pinfunction "S3_M3") (pintype "passive"))
      (node (ref "USB_HS") (pin "M4") (pinfunction "S4_M4") (pintype "passive"))
    )
    (net (code "95") (name "Net-(C84-P$2)") (class "Default")
      (node (ref "C83") (pin "+") (pinfunction "+_+") (pintype "passive"))
      (node (ref "C84") (pin "2") (pinfunction "P$2_2") (pintype "passive"))
      (node (ref "C85") (pin "2") (pinfunction "P$2_2") (pintype "passive"))
      (node (ref "C93") (pin "+") (pinfunction "+_+") (pintype "passive"))
      (node (ref "L3") (pin "2") (pinfunction "2_2") (pintype "passive"))
      (node (ref "U6") (pin "17") (pinfunction "VCC1_17") (pintype "power_in"))
      (node (ref "U6") (pin "23") (pinfunction "VCC2_23") (pintype "power_in"))
    )
    (net (code "96") (name "Net-(C90-P$2)") (class "Default")
      (node (ref "C89") (pin "+") (pinfunction "+_+") (pintype "passive"))
      (node (ref "C90") (pin "2") (pinfunction "P$2_2") (pintype "passive"))
      (node (ref "C91") (pin "2") (pinfunction "P$2_2") (pintype "passive"))
      (node (ref "C92") (pin "+") (pinfunction "+_+") (pintype "passive"))
      (node (ref "L4") (pin "2") (pinfunction "2_2") (pintype "passive"))
      (node (ref "U7") (pin "17") (pinfunction "VCC1_17") (pintype "power_in"))
      (node (ref "U7") (pin "23") (pinfunction "VCC2_23") (pintype "power_in"))
    )
    (net (code "97") (name "Net-(C96-P$1)") (class "Default")
      (node (ref "C96") (pin "1") (pinfunction "P$1_1") (pintype "passive"))
      (node (ref "D1") (pin "A") (pinfunction "A_A") (pintype "passive"))
      (node (ref "IC10") (pin "1") (pinfunction "ADJ_1") (pintype "bidirectional"))
      (node (ref "R94") (pin "1") (pinfunction "1_1") (pintype "passive"))
      (node (ref "R95") (pin "2") (pinfunction "2_2") (pintype "passive"))
    )
    (net (code "98") (name "Net-(C97-P$1)") (class "Default")
      (node (ref "C97") (pin "1") (pinfunction "P$1_1") (pintype "passive"))
      (node (ref "D1") (pin "C") (pinfunction "C_C") (pintype "passive"))
      (node (ref "D2") (pin "A") (pinfunction "A_A") (pintype "passive"))
      (node (ref "IC10") (pin "2") (pinfunction "OUT_2") (pintype "bidirectional"))
      (node (ref "IC10") (pin "4") (pinfunction "OUT_TAB_4") (pintype "bidirectional"))
      (node (ref "L5") (pin "1") (pinfunction "1_1") (pintype "passive"))
      (node (ref "R94") (pin "2") (pinfunction "2_2") (pintype "passive"))
    )
    (net (code "99") (name "Net-(C100-P$2)") (class "Default")
      (node (ref "C100") (pin "2") (pinfunction "P$2_2") (pintype "passive"))
      (node (ref "D4") (pin "C") (pinfunction "C_C") (pintype "passive"))
      (node (ref "IC11") (pin "1") (pinfunction "ADJ_1") (pintype "bidirectional"))
      (node (ref "R96") (pin "1") (pinfunction "1_1") (pintype "passive"))
      (node (ref "R97") (pin "2") (pinfunction "2_2") (pintype "passive"))
    )
    (net (code "100") (name "Net-(C101-P$2)") (class "Default")
      (node (ref "C101") (pin "2") (pinfunction "P$2_2") (pintype "passive"))
      (node (ref "D3") (pin "C") (pinfunction "C_C") (pintype "passive"))
      (node (ref "D4") (pin "A") (pinfunction "A_A") (pintype "passive"))
      (node (ref "IC11") (pin "3") (pinfunction "OUT_3") (pintype "bidirectional"))
      (node (ref "L6") (pin "1") (pinfunction "1_1") (pintype "passive"))
      (node (ref "R97") (pin "1") (pinfunction "1_1") (pintype "passive"))
    )
    (net (code "101") (name "Net-(JP6B-1)") (class "Default")
      (node (ref "JP6") (pin "3") (pinfunction "1_3") (pintype "passive"))
      (node (ref "U2") (pin "4") (pinfunction "-VOUT_4") (pintype "output"))
    )
    (net (code "102") (name "Net-(JP6C-1)") (class "Default")
      (node (ref "JP6") (pin "5") (pinfunction "1_5") (pintype "passive"))
      (node (ref "U2") (pin "5") (pinfunction "COMMON_5") (pintype "power_in"))
    )
    (net (code "103") (name "Net-(JP6D-1)") (class "Default")
      (node (ref "JP6") (pin "7") (pinfunction "1_7") (pintype "passive"))
      (node (ref "U2") (pin "6") (pinfunction "+VOUT_6") (pintype "output"))
    )
    (net (code "104") (name "Net-(LED1-A_1)") (class "Default")
      (node (ref "LED1") (pin "A1") (pinfunction "A_1_A1") (pintype "bidirectional"))
      (node (ref "R98") (pin "1") (pinfunction "1_1") (pintype "passive"))
    )
    (net (code "105") (name "Net-(LED1-A_2)") (class "Default")
      (node (ref "LED1") (pin "A2") (pinfunction "A_2_A2") (pintype "bidirectional"))
      (node (ref "R99") (pin "1") (pinfunction "1_1") (pintype "passive"))
    )
    (net (code "106") (name "Net-(LED1-A_3)") (class "Default")
      (node (ref "LED1") (pin "A3") (pinfunction "A_3_A3") (pintype "bidirectional"))
      (node (ref "R100") (pin "1") (pinfunction "1_1") (pintype "passive"))
    )
    (net (code "107") (name "Net-(LED2-PadA)") (class "Default")
      (node (ref "LED2") (pin "A") (pinfunction "A_A") (pintype "passive"))
      (node (ref "R49") (pin "1") (pinfunction "1_1") (pintype "passive"))
    )
    (net (code "108") (name "Net-(OSC1-INH)") (class "Default")
      (node (ref "OSC1") (pin "1") (pinfunction "INH_1") (pintype "bidirectional"))
      (node (ref "R55") (pin "1") (pinfunction "1_1") (pintype "passive"))
    )
    (net (code "109") (name "Net-(OSC1-OUT)") (class "Default")
      (node (ref "OSC1") (pin "3") (pinfunction "OUT_3") (pintype "output"))
      (node (ref "R56") (pin "1") (pinfunction "1_1") (pintype "passive"))
    )
    (net (code "110") (name "Net-(R61-Pad2)") (class "Default")
      (node (ref "R61") (pin "2") (pinfunction "2_2") (pintype "passive"))
      (node (ref "USB_FS") (pin "2") (pinfunction "2_2") (pintype "bidirectional"))
    )
    (net (code "111") (name "Net-(R62-Pad2)") (class "Default")
      (node (ref "R62") (pin "2") (pinfunction "2_2") (pintype "passive"))
      (node (ref "USB_FS") (pin "3") (pinfunction "3_3") (pintype "bidirectional"))
    )
    (net (code "112") (name "Net-(R101-Pad2)") (class "Default")
      (node (ref "R101") (pin "2") (pinfunction "2_2") (pintype "passive"))
      (node (ref "U$1") (pin "LED+") (pinfunction "LED+_LED+") (pintype "passive"))
    )
    (net (code "113") (name "Net-(U2-+VIN)") (class "Default")
      (node (ref "L7") (pin "2") (pinfunction "2_2") (pintype "passive"))
      (node (ref "U2") (pin "1") (pinfunction "+VIN_1") (pintype "input"))
    )
    (net (code "114") (name "Net-(U3A-BOOT0)") (class "Default")
      (node (ref "R51") (pin "1") (pinfunction "1_1") (pintype "passive"))
      (node (ref "R52") (pin "1") (pinfunction "1_1") (pintype "passive"))
      (node (ref "U3") (pin "138") (pinfunction "BOOT0_138") (pintype "input"))
    )
    (net (code "115") (name "Net-(U3A-OTG_HS_REXT)") (class "Default")
      (node (ref "R54") (pin "1") (pinfunction "1_1") (pintype "passive"))
      (node (ref "U3") (pin "75") (pinfunction "OTG_HS_REXT_75") (pintype "bidirectional"))
    )
    (net (code "116") (name "Net-(U3B-PE3)") (class "Default")
      (node (ref "R88") (pin "1") (pinfunction "1_1") (pintype "passive"))
      (node (ref "U3") (pin "2") (pinfunction "PE3_2") (pintype "bidirectional"))
    )
    (net (code "117") (name "Net-(U3B-PE4)") (class "Default")
      (node (ref "R89") (pin "1") (pinfunction "1_1") (pintype "passive"))
      (node (ref "U3") (pin "3") (pinfunction "PE4_3") (pintype "bidirectional"))
    )
    (net (code "118") (name "Net-(U3B-PE5)") (class "Default")
      (node (ref "R90") (pin "1") (pinfunction "1_1") (pintype "passive"))
      (node (ref "U3") (pin "4") (pinfunction "PE5_4") (pintype "bidirectional"))
    )
    (net (code "119") (name "Net-(U3B-PE6)") (class "Default")
      (node (ref "R91") (pin "1") (pinfunction "1_1") (pintype "passive"))
      (node (ref "U3") (pin "5") (pinfunction "PE6_5") (pintype "bidirectional"))
    )
    (net (code "120") (name "Net-(U3C-PDR_ON)") (class "Default")
      (node (ref "R50") (pin "2") (pinfunction "2_2") (pintype "passive"))
      (node (ref "U3") (pin "143") (pinfunction "PDR_ON_143") (pintype "power_in"))
    )
    (net (code "121") (name "Net-(U4-I{slash}O1)") (class "Default")
      (node (ref "R62") (pin "1") (pinfunction "1_1") (pintype "passive"))
      (node (ref "U4") (pin "6") (pinfunction "I/O1_6") (pintype "bidirectional"))
    )
    (net (code "122") (name "Net-(U4-I{slash}O2)") (class "Default")
      (node (ref "R61") (pin "1") (pinfunction "1_1") (pintype "passive"))
      (node (ref "U4") (pin "4") (pinfunction "I/O2_4") (pintype "bidirectional"))
    )
    (net (code "123") (name "Net-(U5-I{slash}O1)") (class "Default")
      (node (ref "R60") (pin "1") (pinfunction "1_1") (pintype "passive"))
      (node (ref "U5") (pin "6") (pinfunction "I/O1_6") (pintype "bidirectional"))
    )
    (net (code "124") (name "Net-(U5-I{slash}O2)") (class "Default")
      (node (ref "R59") (pin "1") (pinfunction "1_1") (pintype "passive"))
      (node (ref "U5") (pin "4") (pinfunction "I/O2_4") (pintype "bidirectional"))
    )
    (net (code "125") (name "Net-(U6A-BCK)") (class "Default")
      (node (ref "R63") (pin "2") (pinfunction "2_2") (pintype "passive"))
      (node (ref "U6") (pin "7") (pinfunction "BCK_7") (pintype "input"))
    )
    (net (code "126") (name "Net-(U6A-DATA1)") (class "Default")
      (node (ref "R64") (pin "2") (pinfunction "2_2") (pintype "passive"))
      (node (ref "U6") (pin "6") (pinfunction "DATA1_6") (pintype "input"))
    )
    (net (code "127") (name "Net-(U6A-DATA2)") (class "Default")
      (node (ref "R65") (pin "2") (pinfunction "2_2") (pintype "passive"))
      (node (ref "U6") (pin "11") (pinfunction "DATA2_11") (pintype "input"))
    )
    (net (code "128") (name "Net-(U6A-DATA3)") (class "Default")
      (node (ref "R68") (pin "2") (pinfunction "2_2") (pintype "passive"))
      (node (ref "U6") (pin "12") (pinfunction "DATA3_12") (pintype "input"))
    )
    (net (code "129") (name "Net-(U6A-DATA4)") (class "Default")
      (node (ref "R72") (pin "2") (pinfunction "2_2") (pintype "passive"))
      (node (ref "U6") (pin "13") (pinfunction "DATA4_13") (pintype "input"))
    )
    (net (code "130") (name "Net-(U6A-LRCK)") (class "Default")
      (node (ref "R66") (pin "2") (pinfunction "2_2") (pintype "passive"))
      (node (ref "U6") (pin "8") (pinfunction "LRCK_8") (pintype "input"))
    )
    (net (code "131") (name "Net-(U6A-MC{slash}SCL{slash}DEMP)") (class "Default")
      (node (ref "R70") (pin "2") (pinfunction "2_2") (pintype "passive"))
      (node (ref "U6") (pin "3") (pinfunction "MC/SCL/DEMP_3") (pintype "input"))
    )
    (net (code "132") (name "Net-(U6A-MD{slash}SDA{slash}MUTE)") (class "Default")
      (node (ref "R71") (pin "2") (pinfunction "2_2") (pintype "passive"))
      (node (ref "U6") (pin "4") (pinfunction "MD/SDA/MUTE_4") (pintype "bidirectional"))
    )
    (net (code "133") (name "Net-(U6A-SCK)") (class "Default")
      (node (ref "R67") (pin "2") (pinfunction "2_2") (pintype "passive"))
      (node (ref "U6") (pin "5") (pinfunction "SCK_5") (pintype "input"))
    )
    (net (code "134") (name "Net-(U6A-ZR1{slash}ZR1{slash}FMT0)") (class "Default")
      (node (ref "R73") (pin "1") (pinfunction "1_1") (pintype "passive"))
      (node (ref "U6") (pin "1") (pinfunction "ZR1/ZR1/FMT0_1") (pintype "bidirectional"))
    )
    (net (code "135") (name "Net-(U6A-ZR2)") (class "Default")
      (node (ref "R74") (pin "1") (pinfunction "1_1") (pintype "passive"))
      (node (ref "U6") (pin "28") (pinfunction "ZR2_28") (pintype "output"))
    )
    (net (code "136") (name "Net-(U6A-~{MS{slash}ADR{slash}FMT1})") (class "Default")
      (node (ref "R69") (pin "2") (pinfunction "2_2") (pintype "passive"))
      (node (ref "U6") (pin "2") (pinfunction "~{MS/ADR/FMT1}_2") (pintype "input"))
    )
    (net (code "137") (name "Net-(U6B-VCOM)") (class "Default")
      (node (ref "C82") (pin "+") (pinfunction "+_+") (pintype "passive"))
      (node (ref "U6") (pin "25") (pinfunction "VCOM_25") (pintype "power_in"))
    )
    (net (code "138") (name "Net-(U7A-BCK)") (class "Default")
      (node (ref "R75") (pin "2") (pinfunction "2_2") (pintype "passive"))
      (node (ref "U7") (pin "7") (pinfunction "BCK_7") (pintype "input"))
    )
    (net (code "139") (name "Net-(U7A-DATA1)") (class "Default")
      (node (ref "R76") (pin "2") (pinfunction "2_2") (pintype "passive"))
      (node (ref "U7") (pin "6") (pinfunction "DATA1_6") (pintype "input"))
    )
    (net (code "140") (name "Net-(U7A-DATA2)") (class "Default")
      (node (ref "R77") (pin "2") (pinfunction "2_2") (pintype "passive"))
      (node (ref "U7") (pin "11") (pinfunction "DATA2_11") (pintype "input"))
    )
    (net (code "141") (name "Net-(U7A-DATA3)") (class "Default")
      (node (ref "R83") (pin "2") (pinfunction "2_2") (pintype "passive"))
      (node (ref "U7") (pin "12") (pinfunction "DATA3_12") (pintype "input"))
    )
    (net (code "142") (name "Net-(U7A-DATA4)") (class "Default")
      (node (ref "R84") (pin "2") (pinfunction "2_2") (pintype "passive"))
      (node (ref "U7") (pin "13") (pinfunction "DATA4_13") (pintype "input"))
    )
    (net (code "143") (name "Net-(U7A-LRCK)") (class "Default")
      (node (ref "R78") (pin "2") (pinfunction "2_2") (pintype "passive"))
      (node (ref "U7") (pin "8") (pinfunction "LRCK_8") (pintype "input"))
    )
    (net (code "144") (name "Net-(U7A-MC{slash}SCL{slash}DEMP)") (class "Default")
      (node (ref "R81") (pin "2") (pinfunction "2_2") (pintype "passive"))
      (node (ref "U7") (pin "3") (pinfunction "MC/SCL/DEMP_3") (pintype "input"))
    )
    (net (code "145") (name "Net-(U7A-MD{slash}SDA{slash}MUTE)") (class "Default")
      (node (ref "R82") (pin "2") (pinfunction "2_2") (pintype "passive"))
      (node (ref "U7") (pin "4") (pinfunction "MD/SDA/MUTE_4") (pintype "bidirectional"))
    )
    (net (code "146") (name "Net-(U7A-SCK)") (class "Default")
      (node (ref "R79") (pin "2") (pinfunction "2_2") (pintype "passive"))
      (node (ref "U7") (pin "5") (pinfunction "SCK_5") (pintype "input"))
    )
    (net (code "147") (name "Net-(U7A-VOUT5)") (class "Default")
      (node (ref "R102") (pin "1") (pinfunction "1_1") (pintype "passive"))
      (node (ref "U7") (pin "20") (pinfunction "VOUT5_20") (pintype "output"))
    )
    (net (code "148") (name "Net-(U7A-VOUT6)") (class "Default")
      (node (ref "R103") (pin "1") (pinfunction "1_1") (pintype "passive"))
      (node (ref "U7") (pin "19") (pinfunction "VOUT6_19") (pintype "output"))
    )
    (net (code "149") (name "Net-(U7A-VOUT7)") (class "Default")
      (node (ref "R104") (pin "1") (pinfunction "1_1") (pintype "passive"))
      (node (ref "U7") (pin "16") (pinfunction "VOUT7_16") (pintype "output"))
    )
    (net (code "150") (name "Net-(U7A-VOUT8)") (class "Default")
      (node (ref "R105") (pin "1") (pinfunction "1_1") (pintype "passive"))
      (node (ref "U7") (pin "15") (pinfunction "VOUT8_15") (pintype "output"))
    )
    (net (code "151") (name "Net-(U7A-ZR1{slash}ZR1{slash}FMT0)") (class "Default")
      (node (ref "R85") (pin "1") (pinfunction "1_1") (pintype "passive"))
      (node (ref "U7") (pin "1") (pinfunction "ZR1/ZR1/FMT0_1") (pintype "bidirectional"))
    )
    (net (code "152") (name "Net-(U7A-ZR2)") (class "Default")
      (node (ref "R86") (pin "1") (pinfunction "1_1") (pintype "passive"))
      (node (ref "U7") (pin "28") (pinfunction "ZR2_28") (pintype "output"))
    )
    (net (code "153") (name "Net-(U7A-~{MS{slash}ADR{slash}FMT1})") (class "Default")
      (node (ref "R80") (pin "2") (pinfunction "2_2") (pintype "passive"))
      (node (ref "U7") (pin "2") (pinfunction "~{MS/ADR/FMT1}_2") (pintype "input"))
    )
    (net (code "154") (name "Net-(U7B-VCOM)") (class "Default")
      (node (ref "C88") (pin "+") (pinfunction "+_+") (pintype "passive"))
      (node (ref "U7") (pin "25") (pinfunction "VCOM_25") (pintype "power_in"))
    )
    (net (code "155") (name "Net-(USB_HSB-2)") (class "Default")
      (node (ref "R59") (pin "2") (pinfunction "2_2") (pintype "passive"))
      (node (ref "USB_HS") (pin "P$2") (pinfunction "2_P$2") (pintype "passive"))
    )
    (net (code "156") (name "Net-(USB_HSB-3)") (class "Default")
      (node (ref "R60") (pin "2") (pinfunction "2_2") (pintype "passive"))
      (node (ref "USB_HS") (pin "P$3") (pinfunction "3_P$3") (pintype "passive"))
    )
    (net (code "157") (name "OSC_IN") (class "Default")
      (node (ref "C73") (pin "1") (pinfunction "P$1_1") (pintype "passive"))
      (node (ref "U3") (pin "23") (pinfunction "PH0-OSC_IN_23") (pintype "bidirectional"))
      (node (ref "Y1") (pin "1") (pinfunction "1_1") (pintype "passive"))
    )
    (net (code "158") (name "OSC_OUT") (class "Default")
      (node (ref "C74") (pin "2") (pinfunction "P$2_2") (pintype "passive"))
      (node (ref "U3") (pin "24") (pinfunction "PH1-OSC_OUT_24") (pintype "bidirectional"))
      (node (ref "Y1") (pin "2") (pinfunction "2_2") (pintype "passive"))
    )
    (net (code "159") (name "PUSHBTN") (class "Default")
      (node (ref "C102") (pin "1") (pinfunction "P$1_1") (pintype "passive"))
      (node (ref "U$1") (pin "P$2") (pinfunction "IN1_P$2") (pintype "passive"))
      (node (ref "U$1") (pin "P$5") (pinfunction "IN2_P$5") (pintype "passive"))
      (node (ref "U3") (pin "46") (pinfunction "PB0_46") (pintype "bidirectional"))
    )
    (net (code "160") (name "SAI_BCK") (class "Default")
      (node (ref "R63") (pin "1") (pinfunction "1_1") (pintype "passive"))
      (node (ref "R67") (pin "1") (pinfunction "1_1") (pintype "passive"))
      (node (ref "R75") (pin "1") (pinfunction "1_1") (pintype "passive"))
      (node (ref "R79") (pin "1") (pinfunction "1_1") (pintype "passive"))
      (node (ref "R90") (pin "2") (pinfunction "2_2") (pintype "passive"))
      (node (ref "TP9") (pin "TP") (pinfunction "TP_TP") (pintype "input"))
    )
    (net (code "161") (name "SAI_DATA1") (class "Default")
      (node (ref "R64") (pin "1") (pinfunction "1_1") (pintype "passive"))
      (node (ref "R91") (pin "2") (pinfunction "2_2") (pintype "passive"))
      (node (ref "TP10") (pin "TP") (pinfunction "TP_TP") (pintype "input"))
    )
    (net (code "162") (name "SAI_DATA2") (class "Default")
      (node (ref "R76") (pin "1") (pinfunction "1_1") (pintype "passive"))
      (node (ref "R88") (pin "2") (pinfunction "2_2") (pintype "passive"))
      (node (ref "TP7") (pin "TP") (pinfunction "TP_TP") (pintype "input"))
    )
    (net (code "163") (name "SAI_LRCK") (class "Default")
      (node (ref "R66") (pin "1") (pinfunction "1_1") (pintype "passive"))
      (node (ref "R78") (pin "1") (pinfunction "1_1") (pintype "passive"))
      (node (ref "R89") (pin "2") (pinfunction "2_2") (pintype "passive"))
      (node (ref "TP8") (pin "TP") (pinfunction "TP_TP") (pintype "input"))
    )
    (net (code "164") (name "SPI_CLK") (class "Default")
      (node (ref "IC7") (pin "2") (pinfunction "SCK_2") (pintype "input"))
      (node (ref "U3") (pin "41") (pinfunction "PA5_41") (pintype "bidirectional"))
    )
    (net (code "165") (name "SPI_CS_FLASH") (class "Default")
      (node (ref "IC7") (pin "4") (pinfunction "~{CS}_4") (pintype "input"))
      (node (ref "U3") (pin "44") (pinfunction "PC4_44") (pintype "bidirectional"))
    )
    (net (code "166") (name "SPI_MISO") (class "Default")
      (node (ref "IC7") (pin "8") (pinfunction "SO_8") (pintype "output"))
      (node (ref "U3") (pin "42") (pinfunction "PA6_42") (pintype "bidirectional"))
    )
    (net (code "167") (name "SPI_MOSI") (class "Default")
      (node (ref "IC7") (pin "1") (pinfunction "SI_1") (pintype "input"))
      (node (ref "U3") (pin "43") (pinfunction "PA7_43") (pintype "bidirectional"))
    )
    (net (code "168") (name "SWCLK") (class "Default")
      (node (ref "TC1") (pin "4") (pinfunction "4_4") (pintype "passive"))
      (node (ref "U3") (pin "109") (pinfunction "PA14_109") (pintype "bidirectional"))
    )
    (net (code "169") (name "SWDIO") (class "Default")
      (node (ref "TC1") (pin "2") (pinfunction "2_2") (pintype "passive"))
      (node (ref "U3") (pin "105") (pinfunction "PA13_105") (pintype "bidirectional"))
    )
    (net (code "170") (name "SWO") (class "Default")
      (node (ref "TC1") (pin "6") (pinfunction "6_6") (pintype "passive"))
      (node (ref "U3") (pin "133") (pinfunction "PB3_133") (pintype "bidirectional"))
    )
    (net (code "171") (name "UART_RX") (class "Default")
      (node (ref "TC1") (pin "8") (pinfunction "8_8") (pintype "passive"))
      (node (ref "U3") (pin "122") (pinfunction "PD6_122") (pintype "bidirectional"))
    )
    (net (code "172") (name "UART_TX") (class "Default")
      (node (ref "TC1") (pin "7") (pinfunction "7_7") (pintype "passive"))
      (node (ref "U3") (pin "119") (pinfunction "PD5_119") (pintype "bidirectional"))
    )
    (net (code "173") (name "USB_FS_N") (class "Default")
      (node (ref "U3") (pin "103") (pinfunction "PA11_103") (pintype "bidirectional"))
      (node (ref "U4") (pin "3") (pinfunction "I/O2_2_3") (pintype "bidirectional"))
    )
    (net (code "174") (name "USB_FS_P") (class "Default")
      (node (ref "U3") (pin "104") (pinfunction "PA12_104") (pintype "bidirectional"))
      (node (ref "U4") (pin "1") (pinfunction "I/O1_2_1") (pintype "bidirectional"))
    )
    (net (code "175") (name "USB_HS_N") (class "Default")
      (node (ref "U3") (pin "77") (pinfunction "PB14_77") (pintype "bidirectional"))
      (node (ref "U5") (pin "3") (pinfunction "I/O2_2_3") (pintype "bidirectional"))
    )
    (net (code "176") (name "USB_HS_P") (class "Default")
      (node (ref "U3") (pin "78") (pinfunction "PB15_78") (pintype "bidirectional"))
      (node (ref "U5") (pin "1") (pinfunction "I/O1_2_1") (pintype "bidirectional"))
    )
    (net (code "177") (name "unconnected-(PL1-G-Pad7)") (class "Default")
      (node (ref "PL1") (pin "7") (pinfunction "G_7") (pintype "bidirectional"))
    )
    (net (code "178") (name "unconnected-(PL1-RNB-Pad4)") (class "Default")
      (node (ref "PL1") (pin "4") (pinfunction "RNB_4") (pintype "bidirectional"))
    )
    (net (code "179") (name "unconnected-(PL1-RNT-Pad3)") (class "Default")
      (node (ref "PL1") (pin "3") (pinfunction "RNT_3") (pintype "bidirectional"))
    )
    (net (code "180") (name "unconnected-(PL1-SNB-Pad6)") (class "Default")
      (node (ref "PL1") (pin "6") (pinfunction "SNB_6") (pintype "bidirectional"))
    )
    (net (code "181") (name "unconnected-(PL1-SNT-Pad5)") (class "Default")
      (node (ref "PL1") (pin "5") (pinfunction "SNT_5") (pintype "bidirectional"))
    )
    (net (code "182") (name "unconnected-(PL1-TNB-Pad2)") (class "Default")
      (node (ref "PL1") (pin "2") (pinfunction "TNB_2") (pintype "bidirectional"))
    )
    (net (code "183") (name "unconnected-(PL1-TNT-Pad1)") (class "Default")
      (node (ref "PL1") (pin "1") (pinfunction "TNT_1") (pintype "bidirectional"))
    )
    (net (code "184") (name "unconnected-(PL2-G-Pad7)") (class "Default")
      (node (ref "PL2") (pin "7") (pinfunction "G_7") (pintype "bidirectional"))
    )
    (net (code "185") (name "unconnected-(PL2-RNB-Pad4)") (class "Default")
      (node (ref "PL2") (pin "4") (pinfunction "RNB_4") (pintype "bidirectional"))
    )
    (net (code "186") (name "unconnected-(PL2-RNT-Pad3)") (class "Default")
      (node (ref "PL2") (pin "3") (pinfunction "RNT_3") (pintype "bidirectional"))
    )
    (net (code "187") (name "unconnected-(PL2-SNB-Pad6)") (class "Default")
      (node (ref "PL2") (pin "6") (pinfunction "SNB_6") (pintype "bidirectional"))
    )
    (net (code "188") (name "unconnected-(PL2-SNT-Pad5)") (class "Default")
      (node (ref "PL2") (pin "5") (pinfunction "SNT_5") (pintype "bidirectional"))
    )
    (net (code "189") (name "unconnected-(PL2-TNB-Pad2)") (class "Default")
      (node (ref "PL2") (pin "2") (pinfunction "TNB_2") (pintype "bidirectional"))
    )
    (net (code "190") (name "unconnected-(PL2-TNT-Pad1)") (class "Default")
      (node (ref "PL2") (pin "1") (pinfunction "TNT_1") (pintype "bidirectional"))
    )
    (net (code "191") (name "unconnected-(PL3-G-Pad7)") (class "Default")
      (node (ref "PL3") (pin "7") (pinfunction "G_7") (pintype "bidirectional"))
    )
    (net (code "192") (name "unconnected-(PL3-RNB-Pad4)") (class "Default")
      (node (ref "PL3") (pin "4") (pinfunction "RNB_4") (pintype "bidirectional"))
    )
    (net (code "193") (name "unconnected-(PL3-RNT-Pad3)") (class "Default")
      (node (ref "PL3") (pin "3") (pinfunction "RNT_3") (pintype "bidirectional"))
    )
    (net (code "194") (name "unconnected-(PL3-SNB-Pad6)") (class "Default")
      (node (ref "PL3") (pin "6") (pinfunction "SNB_6") (pintype "bidirectional"))
    )
    (net (code "195") (name "unconnected-(PL3-SNT-Pad5)") (class "Default")
      (node (ref "PL3") (pin "5") (pinfunction "SNT_5") (pintype "bidirectional"))
    )
    (net (code "196") (name "unconnected-(PL3-TNB-Pad2)") (class "Default")
      (node (ref "PL3") (pin "2") (pinfunction "TNB_2") (pintype "bidirectional"))
    )
    (net (code "197") (name "unconnected-(PL3-TNT-Pad1)") (class "Default")
      (node (ref "PL3") (pin "1") (pinfunction "TNT_1") (pintype "bidirectional"))
    )
    (net (code "198") (name "unconnected-(PL4-G-Pad7)") (class "Default")
      (node (ref "PL4") (pin "7") (pinfunction "G_7") (pintype "bidirectional"))
    )
    (net (code "199") (name "unconnected-(PL4-RNB-Pad4)") (class "Default")
      (node (ref "PL4") (pin "4") (pinfunction "RNB_4") (pintype "bidirectional"))
    )
    (net (code "200") (name "unconnected-(PL4-RNT-Pad3)") (class "Default")
      (node (ref "PL4") (pin "3") (pinfunction "RNT_3") (pintype "bidirectional"))
    )
    (net (code "201") (name "unconnected-(PL4-SNB-Pad6)") (class "Default")
      (node (ref "PL4") (pin "6") (pinfunction "SNB_6") (pintype "bidirectional"))
    )
    (net (code "202") (name "unconnected-(PL4-SNT-Pad5)") (class "Default")
      (node (ref "PL4") (pin "5") (pinfunction "SNT_5") (pintype "bidirectional"))
    )
    (net (code "203") (name "unconnected-(PL4-TNB-Pad2)") (class "Default")
      (node (ref "PL4") (pin "2") (pinfunction "TNB_2") (pintype "bidirectional"))
    )
    (net (code "204") (name "unconnected-(PL4-TNT-Pad1)") (class "Default")
      (node (ref "PL4") (pin "1") (pinfunction "TNT_1") (pintype "bidirectional"))
    )
    (net (code "205") (name "unconnected-(PL5-G-Pad7)") (class "Default")
      (node (ref "PL5") (pin "7") (pinfunction "G_7") (pintype "bidirectional"))
    )
    (net (code "206") (name "unconnected-(PL5-RNB-Pad4)") (class "Default")
      (node (ref "PL5") (pin "4") (pinfunction "RNB_4") (pintype "bidirectional"))
    )
    (net (code "207") (name "unconnected-(PL5-RNT-Pad3)") (class "Default")
      (node (ref "PL5") (pin "3") (pinfunction "RNT_3") (pintype "bidirectional"))
    )
    (net (code "208") (name "unconnected-(PL5-SNB-Pad6)") (class "Default")
      (node (ref "PL5") (pin "6") (pinfunction "SNB_6") (pintype "bidirectional"))
    )
    (net (code "209") (name "unconnected-(PL5-SNT-Pad5)") (class "Default")
      (node (ref "PL5") (pin "5") (pinfunction "SNT_5") (pintype "bidirectional"))
    )
    (net (code "210") (name "unconnected-(PL5-TNB-Pad2)") (class "Default")
      (node (ref "PL5") (pin "2") (pinfunction "TNB_2") (pintype "bidirectional"))
    )
    (net (code "211") (name "unconnected-(PL5-TNT-Pad1)") (class "Default")
      (node (ref "PL5") (pin "1") (pinfunction "TNT_1") (pintype "bidirectional"))
    )
    (net (code "212") (name "unconnected-(PL6-G-Pad7)") (class "Default")
      (node (ref "PL6") (pin "7") (pinfunction "G_7") (pintype "bidirectional"))
    )
    (net (code "213") (name "unconnected-(PL6-RNB-Pad4)") (class "Default")
      (node (ref "PL6") (pin "4") (pinfunction "RNB_4") (pintype "bidirectional"))
    )
    (net (code "214") (name "unconnected-(PL6-RNT-Pad3)") (class "Default")
      (node (ref "PL6") (pin "3") (pinfunction "RNT_3") (pintype "bidirectional"))
    )
    (net (code "215") (name "unconnected-(PL6-SNB-Pad6)") (class "Default")
      (node (ref "PL6") (pin "6") (pinfunction "SNB_6") (pintype "bidirectional"))
    )
    (net (code "216") (name "unconnected-(PL6-SNT-Pad5)") (class "Default")
      (node (ref "PL6") (pin "5") (pinfunction "SNT_5") (pintype "bidirectional"))
    )
    (net (code "217") (name "unconnected-(PL6-TNB-Pad2)") (class "Default")
      (node (ref "PL6") (pin "2") (pinfunction "TNB_2") (pintype "bidirectional"))
    )
    (net (code "218") (name "unconnected-(PL6-TNT-Pad1)") (class "Default")
      (node (ref "PL6") (pin "1") (pinfunction "TNT_1") (pintype "bidirectional"))
    )
    (net (code "219") (name "unconnected-(U$1-OUT1_NC-PadP$1)") (class "Default")
      (node (ref "U$1") (pin "P$1") (pinfunction "OUT1_NC_P$1") (pintype "passive"))
    )
    (net (code "220") (name "unconnected-(U$1-OUT2_NC-PadP$4)") (class "Default")
      (node (ref "U$1") (pin "P$4") (pinfunction "OUT2_NC_P$4") (pintype "passive"))
    )
    (net (code "221") (name "unconnected-(U3A-PA0-WKUP-Pad34)") (class "Default")
      (node (ref "U3") (pin "34") (pinfunction "PA0-WKUP_34") (pintype "bidirectional"))
    )
    (net (code "222") (name "unconnected-(U3A-PA1-Pad35)") (class "Default")
      (node (ref "U3") (pin "35") (pinfunction "PA1_35") (pintype "bidirectional"))
    )
    (net (code "223") (name "unconnected-(U3A-PA2-Pad36)") (class "Default")
      (node (ref "U3") (pin "36") (pinfunction "PA2_36") (pintype "bidirectional"))
    )
    (net (code "224") (name "unconnected-(U3A-PA3-Pad37)") (class "Default")
      (node (ref "U3") (pin "37") (pinfunction "PA3_37") (pintype "bidirectional"))
    )
    (net (code "225") (name "unconnected-(U3A-PA4-Pad40)") (class "Default")
      (node (ref "U3") (pin "40") (pinfunction "PA4_40") (pintype "bidirectional"))
    )
    (net (code "226") (name "unconnected-(U3A-PA8-Pad100)") (class "Default")
      (node (ref "U3") (pin "100") (pinfunction "PA8_100") (pintype "bidirectional"))
    )
    (net (code "227") (name "unconnected-(U3A-PA10-Pad102)") (class "Default")
      (node (ref "U3") (pin "102") (pinfunction "PA10_102") (pintype "bidirectional"))
    )
    (net (code "228") (name "unconnected-(U3A-PA15-Pad110)") (class "Default")
      (node (ref "U3") (pin "110") (pinfunction "PA15_110") (pintype "bidirectional"))
    )
    (net (code "229") (name "unconnected-(U3A-PB2-Pad48)") (class "Default")
      (node (ref "U3") (pin "48") (pinfunction "PB2_48") (pintype "bidirectional"))
    )
    (net (code "230") (name "unconnected-(U3A-PB4-Pad134)") (class "Default")
      (node (ref "U3") (pin "134") (pinfunction "PB4_134") (pintype "bidirectional"))
    )
    (net (code "231") (name "unconnected-(U3A-PB5-Pad135)") (class "Default")
      (node (ref "U3") (pin "135") (pinfunction "PB5_135") (pintype "bidirectional"))
    )
    (net (code "232") (name "unconnected-(U3A-PB6-Pad136)") (class "Default")
      (node (ref "U3") (pin "136") (pinfunction "PB6_136") (pintype "bidirectional"))
    )
    (net (code "233") (name "unconnected-(U3A-PB9-Pad140)") (class "Default")
      (node (ref "U3") (pin "140") (pinfunction "PB9_140") (pintype "bidirectional"))
    )
    (net (code "234") (name "unconnected-(U3A-PB10-Pad69)") (class "Default")
      (node (ref "U3") (pin "69") (pinfunction "PB10_69") (pintype "bidirectional"))
    )
    (net (code "235") (name "unconnected-(U3A-PB11-Pad70)") (class "Default")
      (node (ref "U3") (pin "70") (pinfunction "PB11_70") (pintype "bidirectional"))
    )
    (net (code "236") (name "unconnected-(U3A-PB12-Pad73)") (class "Default")
      (node (ref "U3") (pin "73") (pinfunction "PB12_73") (pintype "bidirectional"))
    )
    (net (code "237") (name "unconnected-(U3A-PC0-Pad26)") (class "Default")
      (node (ref "U3") (pin "26") (pinfunction "PC0_26") (pintype "bidirectional"))
    )
    (net (code "238") (name "unconnected-(U3A-PC1-Pad27)") (class "Default")
      (node (ref "U3") (pin "27") (pinfunction "PC1_27") (pintype "bidirectional"))
    )
    (net (code "239") (name "unconnected-(U3A-PC2-Pad28)") (class "Default")
      (node (ref "U3") (pin "28") (pinfunction "PC2_28") (pintype "bidirectional"))
    )
    (net (code "240") (name "unconnected-(U3A-PC3-Pad29)") (class "Default")
      (node (ref "U3") (pin "29") (pinfunction "PC3_29") (pintype "bidirectional"))
    )
    (net (code "241") (name "unconnected-(U3A-PC5-Pad45)") (class "Default")
      (node (ref "U3") (pin "45") (pinfunction "PC5_45") (pintype "bidirectional"))
    )
    (net (code "242") (name "unconnected-(U3A-PC6-Pad96)") (class "Default")
      (node (ref "U3") (pin "96") (pinfunction "PC6_96") (pintype "bidirectional"))
    )
    (net (code "243") (name "unconnected-(U3A-PC7-Pad97)") (class "Default")
      (node (ref "U3") (pin "97") (pinfunction "PC7_97") (pintype "bidirectional"))
    )
    (net (code "244") (name "unconnected-(U3A-PC8-Pad98)") (class "Default")
      (node (ref "U3") (pin "98") (pinfunction "PC8_98") (pintype "bidirectional"))
    )
    (net (code "245") (name "unconnected-(U3A-PC13-Pad7)") (class "Default")
      (node (ref "U3") (pin "7") (pinfunction "PC13_7") (pintype "bidirectional"))
    )
    (net (code "246") (name "unconnected-(U3A-PC14-OSC32_IN-Pad8)") (class "Default")
      (node (ref "U3") (pin "8") (pinfunction "PC14-OSC32_IN_8") (pintype "bidirectional"))
    )
    (net (code "247") (name "unconnected-(U3A-PC15-OSC32_OUT-Pad9)") (class "Default")
      (node (ref "U3") (pin "9") (pinfunction "PC15-OSC32_OUT_9") (pintype "bidirectional"))
    )
    (net (code "248") (name "unconnected-(U3A-PD0-Pad114)") (class "Default")
      (node (ref "U3") (pin "114") (pinfunction "PD0_114") (pintype "bidirectional"))
    )
    (net (code "249") (name "unconnected-(U3A-PD1-Pad115)") (class "Default")
      (node (ref "U3") (pin "115") (pinfunction "PD1_115") (pintype "bidirectional"))
    )
    (net (code "250") (name "unconnected-(U3A-PD2-Pad116)") (class "Default")
      (node (ref "U3") (pin "116") (pinfunction "PD2_116") (pintype "bidirectional"))
    )
    (net (code "251") (name "unconnected-(U3A-PD3-Pad117)") (class "Default")
      (node (ref "U3") (pin "117") (pinfunction "PD3_117") (pintype "bidirectional"))
    )
    (net (code "252") (name "unconnected-(U3A-PD4-Pad118)") (class "Default")
      (node (ref "U3") (pin "118") (pinfunction "PD4_118") (pintype "bidirectional"))
    )
    (net (code "253") (name "unconnected-(U3A-PD7-Pad123)") (class "Default")
      (node (ref "U3") (pin "123") (pinfunction "PD7_123") (pintype "bidirectional"))
    )
    (net (code "254") (name "unconnected-(U3A-PD8-Pad79)") (class "Default")
      (node (ref "U3") (pin "79") (pinfunction "PD8_79") (pintype "bidirectional"))
    )
    (net (code "255") (name "unconnected-(U3A-PD9-Pad80)") (class "Default")
      (node (ref "U3") (pin "80") (pinfunction "PD9_80") (pintype "bidirectional"))
    )
    (net (code "256") (name "unconnected-(U3A-PD10-Pad81)") (class "Default")
      (node (ref "U3") (pin "81") (pinfunction "PD10_81") (pintype "bidirectional"))
    )
    (net (code "257") (name "unconnected-(U3A-PD11-Pad82)") (class "Default")
      (node (ref "U3") (pin "82") (pinfunction "PD11_82") (pintype "bidirectional"))
    )
    (net (code "258") (name "unconnected-(U3A-PD12-Pad83)") (class "Default")
      (node (ref "U3") (pin "83") (pinfunction "PD12_83") (pintype "bidirectional"))
    )
    (net (code "259") (name "unconnected-(U3A-PD13-Pad84)") (class "Default")
      (node (ref "U3") (pin "84") (pinfunction "PD13_84") (pintype "bidirectional"))
    )
    (net (code "260") (name "unconnected-(U3A-PD14-Pad87)") (class "Default")
      (node (ref "U3") (pin "87") (pinfunction "PD14_87") (pintype "bidirectional"))
    )
    (net (code "261") (name "unconnected-(U3A-PD15-Pad88)") (class "Default")
      (node (ref "U3") (pin "88") (pinfunction "PD15_88") (pintype "bidirectional"))
    )
    (net (code "262") (name "unconnected-(U3B-PE0-Pad141)") (class "Default")
      (node (ref "U3") (pin "141") (pinfunction "PE0_141") (pintype "bidirectional"))
    )
    (net (code "263") (name "unconnected-(U3B-PE1-Pad142)") (class "Default")
      (node (ref "U3") (pin "142") (pinfunction "PE1_142") (pintype "bidirectional"))
    )
    (net (code "264") (name "unconnected-(U3B-PE2-Pad1)") (class "Default")
      (node (ref "U3") (pin "1") (pinfunction "PE2_1") (pintype "bidirectional"))
    )
    (net (code "265") (name "unconnected-(U3B-PE7-Pad58)") (class "Default")
      (node (ref "U3") (pin "58") (pinfunction "PE7_58") (pintype "bidirectional"))
    )
    (net (code "266") (name "unconnected-(U3B-PE8-Pad59)") (class "Default")
      (node (ref "U3") (pin "59") (pinfunction "PE8_59") (pintype "bidirectional"))
    )
    (net (code "267") (name "unconnected-(U3B-PE9-Pad60)") (class "Default")
      (node (ref "U3") (pin "60") (pinfunction "PE9_60") (pintype "bidirectional"))
    )
    (net (code "268") (name "unconnected-(U3B-PE10-Pad63)") (class "Default")
      (node (ref "U3") (pin "63") (pinfunction "PE10_63") (pintype "bidirectional"))
    )
    (net (code "269") (name "unconnected-(U3B-PE11-Pad64)") (class "Default")
      (node (ref "U3") (pin "64") (pinfunction "PE11_64") (pintype "bidirectional"))
    )
    (net (code "270") (name "unconnected-(U3B-PE12-Pad65)") (class "Default")
      (node (ref "U3") (pin "65") (pinfunction "PE12_65") (pintype "bidirectional"))
    )
    (net (code "271") (name "unconnected-(U3B-PE13-Pad66)") (class "Default")
      (node (ref "U3") (pin "66") (pinfunction "PE13_66") (pintype "bidirectional"))
    )
    (net (code "272") (name "unconnected-(U3B-PE14-Pad67)") (class "Default")
      (node (ref "U3") (pin "67") (pinfunction "PE14_67") (pintype "bidirectional"))
    )
    (net (code "273") (name "unconnected-(U3B-PE15-Pad68)") (class "Default")
      (node (ref "U3") (pin "68") (pinfunction "PE15_68") (pintype "bidirectional"))
    )
    (net (code "274") (name "unconnected-(U3B-PF0-Pad10)") (class "Default")
      (node (ref "U3") (pin "10") (pinfunction "PF0_10") (pintype "bidirectional"))
    )
    (net (code "275") (name "unconnected-(U3B-PF1-Pad11)") (class "Default")
      (node (ref "U3") (pin "11") (pinfunction "PF1_11") (pintype "bidirectional"))
    )
    (net (code "276") (name "unconnected-(U3B-PF2-Pad12)") (class "Default")
      (node (ref "U3") (pin "12") (pinfunction "PF2_12") (pintype "bidirectional"))
    )
    (net (code "277") (name "unconnected-(U3B-PF3-Pad13)") (class "Default")
      (node (ref "U3") (pin "13") (pinfunction "PF3_13") (pintype "bidirectional"))
    )
    (net (code "278") (name "unconnected-(U3B-PF4-Pad14)") (class "Default")
      (node (ref "U3") (pin "14") (pinfunction "PF4_14") (pintype "bidirectional"))
    )
    (net (code "279") (name "unconnected-(U3B-PF5-Pad15)") (class "Default")
      (node (ref "U3") (pin "15") (pinfunction "PF5_15") (pintype "bidirectional"))
    )
    (net (code "280") (name "unconnected-(U3B-PF6-Pad18)") (class "Default")
      (node (ref "U3") (pin "18") (pinfunction "PF6_18") (pintype "bidirectional"))
    )
    (net (code "281") (name "unconnected-(U3B-PF7-Pad19)") (class "Default")
      (node (ref "U3") (pin "19") (pinfunction "PF7_19") (pintype "bidirectional"))
    )
    (net (code "282") (name "unconnected-(U3B-PF8-Pad20)") (class "Default")
      (node (ref "U3") (pin "20") (pinfunction "PF8_20") (pintype "bidirectional"))
    )
    (net (code "283") (name "unconnected-(U3B-PF9-Pad21)") (class "Default")
      (node (ref "U3") (pin "21") (pinfunction "PF9_21") (pintype "bidirectional"))
    )
    (net (code "284") (name "unconnected-(U3B-PF10-Pad22)") (class "Default")
      (node (ref "U3") (pin "22") (pinfunction "PF10_22") (pintype "bidirectional"))
    )
    (net (code "285") (name "unconnected-(U3B-PF11-Pad49)") (class "Default")
      (node (ref "U3") (pin "49") (pinfunction "PF11_49") (pintype "bidirectional"))
    )
    (net (code "286") (name "unconnected-(U3B-PF12-Pad50)") (class "Default")
      (node (ref "U3") (pin "50") (pinfunction "PF12_50") (pintype "bidirectional"))
    )
    (net (code "287") (name "unconnected-(U3B-PF13-Pad53)") (class "Default")
      (node (ref "U3") (pin "53") (pinfunction "PF13_53") (pintype "bidirectional"))
    )
    (net (code "288") (name "unconnected-(U3B-PF14-Pad54)") (class "Default")
      (node (ref "U3") (pin "54") (pinfunction "PF14_54") (pintype "bidirectional"))
    )
    (net (code "289") (name "unconnected-(U3B-PF15-Pad55)") (class "Default")
      (node (ref "U3") (pin "55") (pinfunction "PF15_55") (pintype "bidirectional"))
    )
    (net (code "290") (name "unconnected-(U3B-PG0-Pad56)") (class "Default")
      (node (ref "U3") (pin "56") (pinfunction "PG0_56") (pintype "bidirectional"))
    )
    (net (code "291") (name "unconnected-(U3B-PG1-Pad57)") (class "Default")
      (node (ref "U3") (pin "57") (pinfunction "PG1_57") (pintype "bidirectional"))
    )
    (net (code "292") (name "unconnected-(U3B-PG2-Pad89)") (class "Default")
      (node (ref "U3") (pin "89") (pinfunction "PG2_89") (pintype "bidirectional"))
    )
    (net (code "293") (name "unconnected-(U3B-PG3-Pad90)") (class "Default")
      (node (ref "U3") (pin "90") (pinfunction "PG3_90") (pintype "bidirectional"))
    )
    (net (code "294") (name "unconnected-(U3B-PG4-Pad91)") (class "Default")
      (node (ref "U3") (pin "91") (pinfunction "PG4_91") (pintype "bidirectional"))
    )
    (net (code "295") (name "unconnected-(U3B-PG5-Pad92)") (class "Default")
      (node (ref "U3") (pin "92") (pinfunction "PG5_92") (pintype "bidirectional"))
    )
    (net (code "296") (name "unconnected-(U3B-PG8-Pad93)") (class "Default")
      (node (ref "U3") (pin "93") (pinfunction "PG8_93") (pintype "bidirectional"))
    )
    (net (code "297") (name "unconnected-(U3B-PG9-Pad124)") (class "Default")
      (node (ref "U3") (pin "124") (pinfunction "PG9_124") (pintype "bidirectional"))
    )
    (net (code "298") (name "unconnected-(U3B-PG10-Pad125)") (class "Default")
      (node (ref "U3") (pin "125") (pinfunction "PG10_125") (pintype "bidirectional"))
    )
    (net (code "299") (name "unconnected-(U3B-PG11-Pad126)") (class "Default")
      (node (ref "U3") (pin "126") (pinfunction "PG11_126") (pintype "bidirectional"))
    )
    (net (code "300") (name "unconnected-(U3B-PG12-Pad127)") (class "Default")
      (node (ref "U3") (pin "127") (pinfunction "PG12_127") (pintype "bidirectional"))
    )
    (net (code "301") (name "unconnected-(U3B-PG13-Pad128)") (class "Default")
      (node (ref "U3") (pin "128") (pinfunction "PG13_128") (pintype "bidirectional"))
    )
    (net (code "302") (name "unconnected-(U3B-PG14-Pad129)") (class "Default")
      (node (ref "U3") (pin "129") (pinfunction "PG14_129") (pintype "bidirectional"))
    )
    (net (code "303") (name "unconnected-(U3B-PG15-Pad132)") (class "Default")
      (node (ref "U3") (pin "132") (pinfunction "PG15_132") (pintype "bidirectional"))
    )
  )
)
